# keyboard_matrix_full.net
KiCad netlist of a schematic drawn in Altium Designer
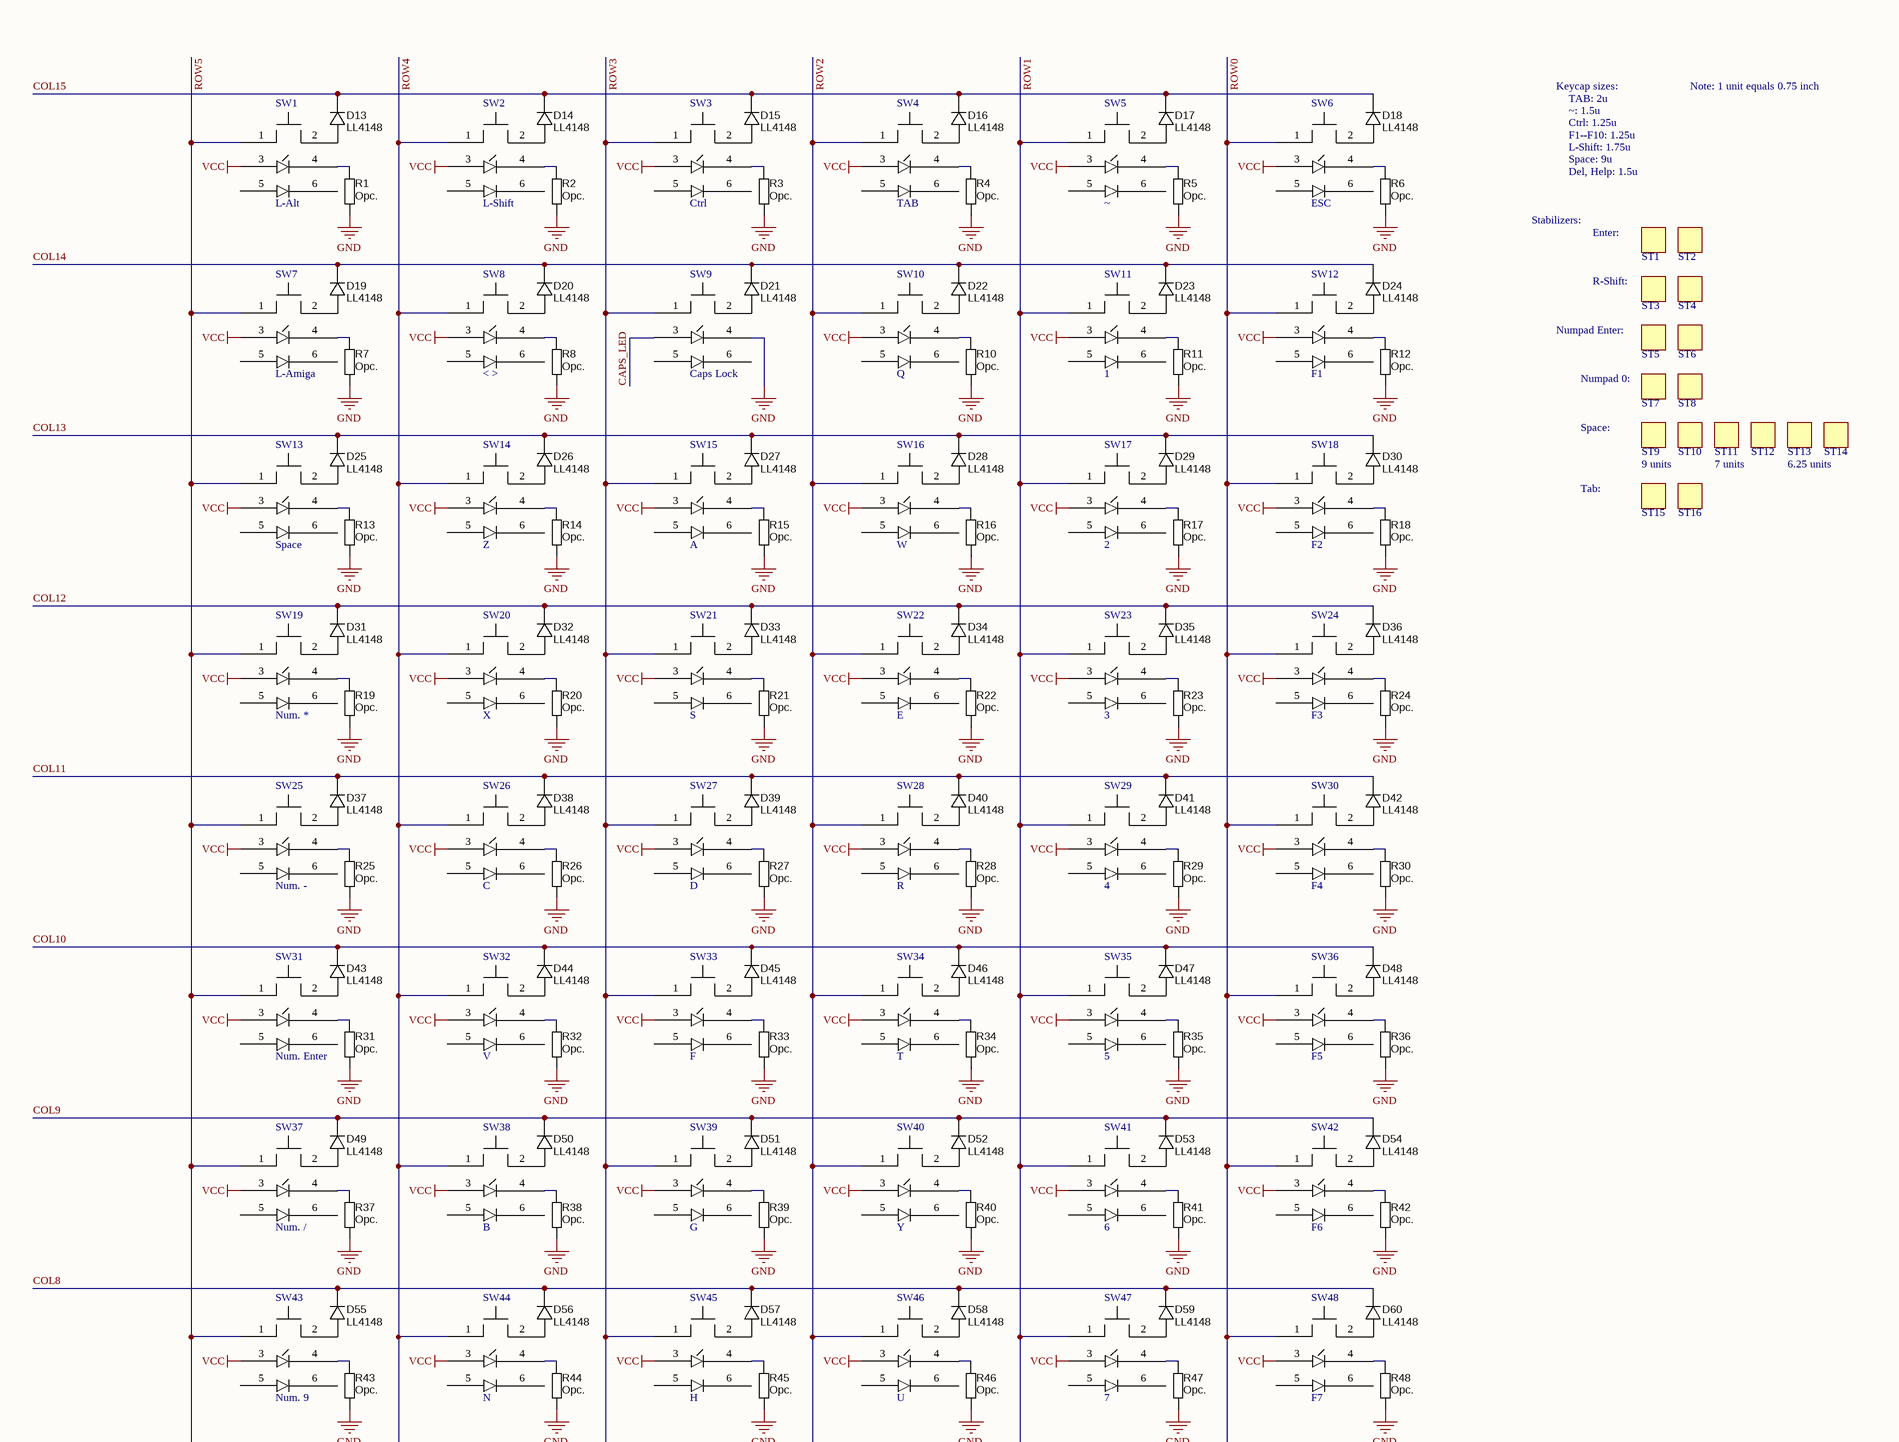
[diagram p0: keyboard_matrix_full.SchDoc, top]
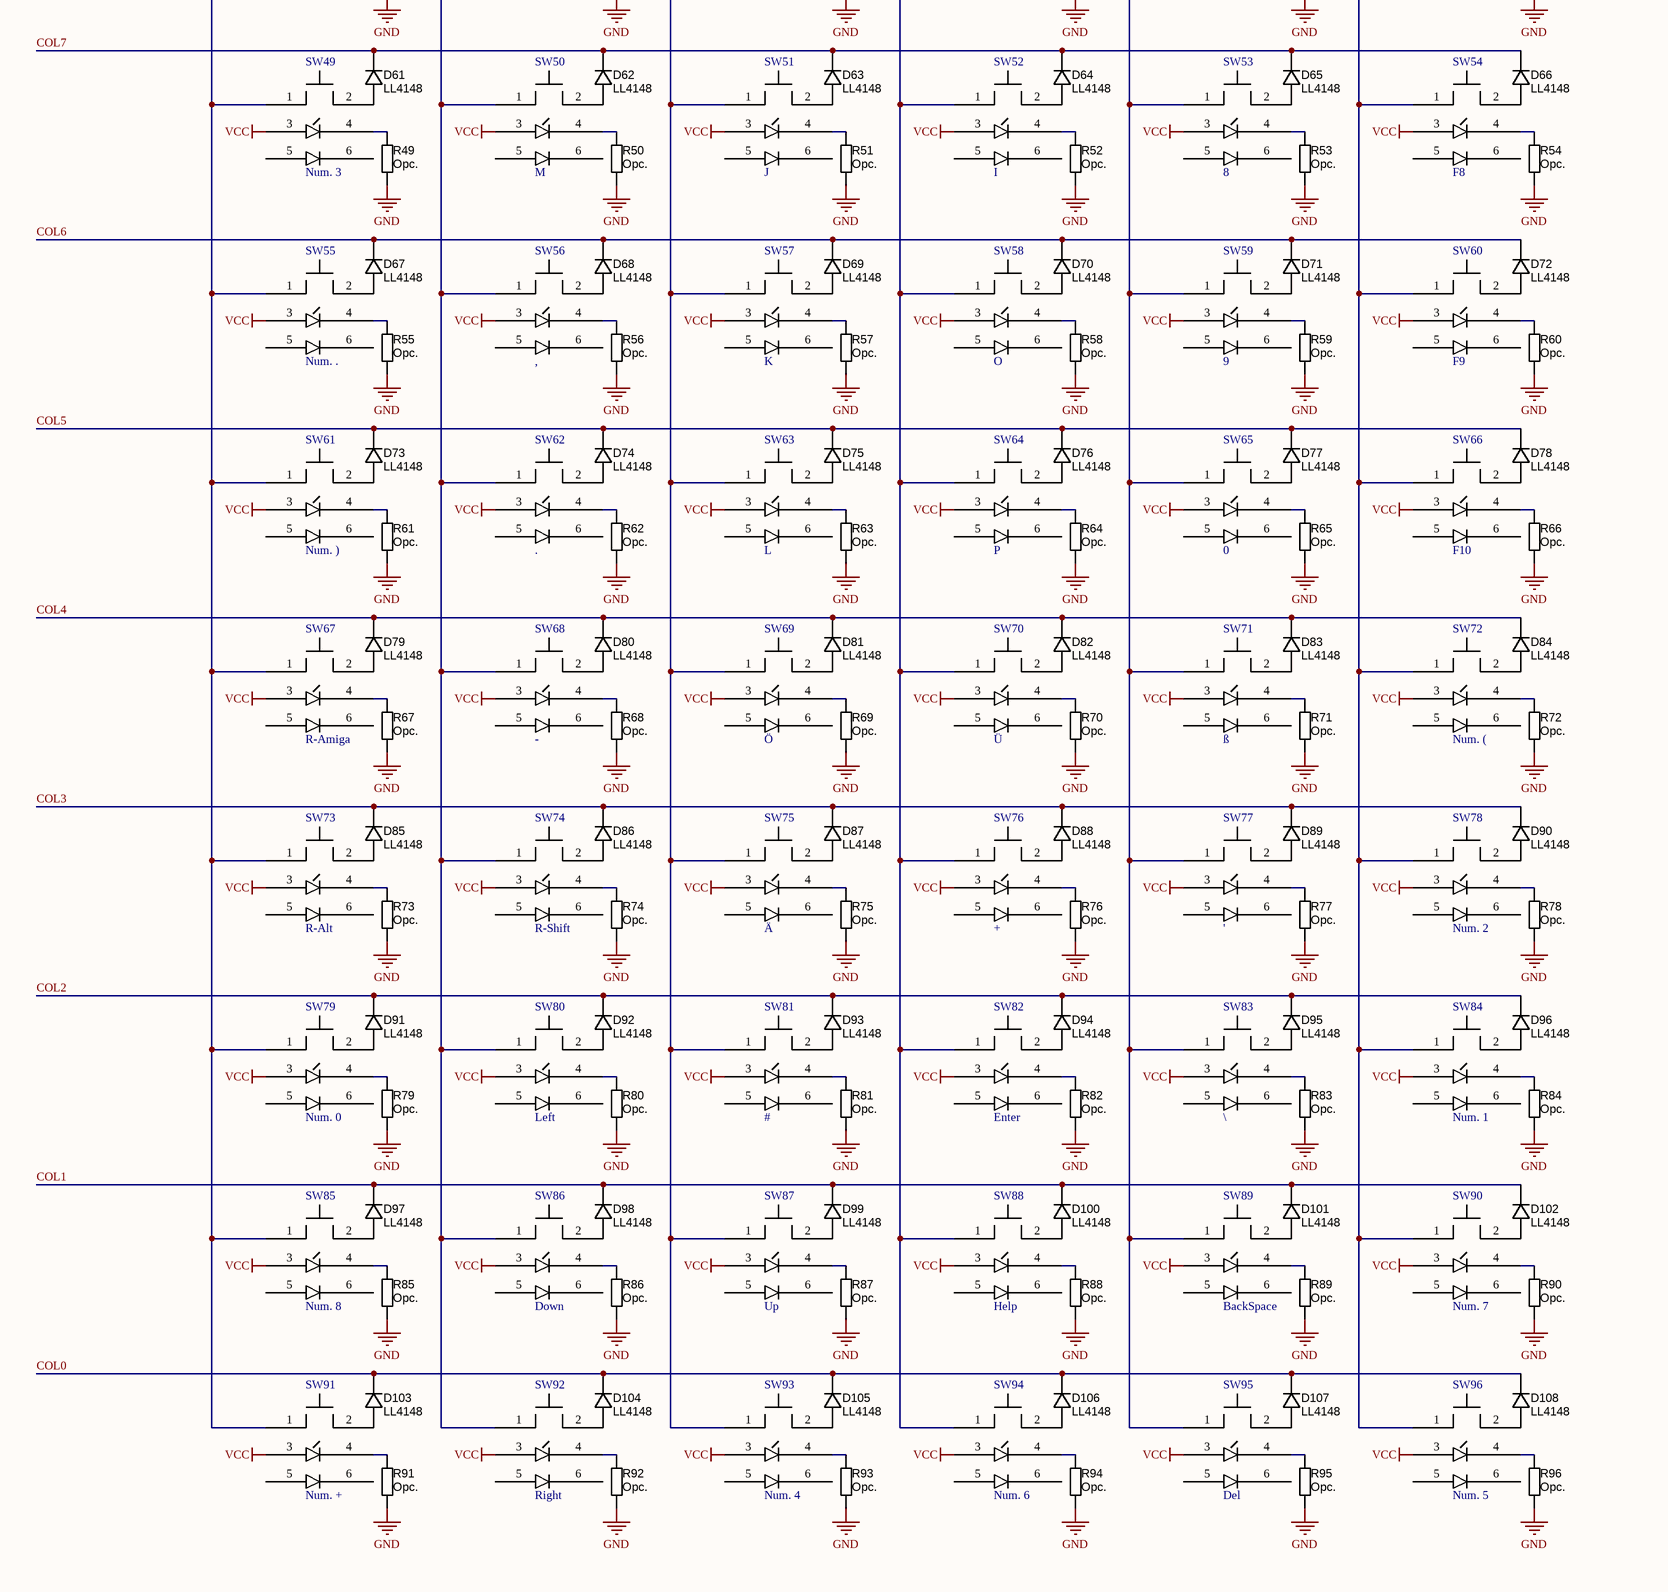
[diagram p1: keyboard_matrix_full.SchDoc, bottom]

(export (version "E")
  (design (tool "Eeschema 10.0.6"))
  (components
    (comp (ref "D13")
      (value "Mini MELF")
      (footprint "SOD80, LL-34")
      (description "Diode SMD 100V 150mA 500mW SOD80")
      (fields (field (name "MANUFACTURER PART NUMBER 1") "LL4148"))
      (libsource (lib "PBL - Diodes") (part "DIODE_100V_500mW_MELF"))
    )
    (comp (ref "D14")
      (value "Mini MELF")
      (footprint "SOD80, LL-34")
      (description "Diode SMD 100V 150mA 500mW SOD80")
      (fields (field (name "MANUFACTURER PART NUMBER 1") "LL4148"))
      (libsource (lib "PBL - Diodes") (part "DIODE_100V_500mW_MELF"))
    )
    (comp (ref "D15")
      (value "Mini MELF")
      (footprint "SOD80, LL-34")
      (description "Diode SMD 100V 150mA 500mW SOD80")
      (fields (field (name "MANUFACTURER PART NUMBER 1") "LL4148"))
      (libsource (lib "PBL - Diodes") (part "DIODE_100V_500mW_MELF"))
    )
    (comp (ref "D16")
      (value "Mini MELF")
      (footprint "SOD80, LL-34")
      (description "Diode SMD 100V 150mA 500mW SOD80")
      (fields (field (name "MANUFACTURER PART NUMBER 1") "LL4148"))
      (libsource (lib "PBL - Diodes") (part "DIODE_100V_500mW_MELF"))
    )
    (comp (ref "D17")
      (value "Mini MELF")
      (footprint "SOD80, LL-34")
      (description "Diode SMD 100V 150mA 500mW SOD80")
      (fields (field (name "MANUFACTURER PART NUMBER 1") "LL4148"))
      (libsource (lib "PBL - Diodes") (part "DIODE_100V_500mW_MELF"))
    )
    (comp (ref "D18")
      (value "Mini MELF")
      (footprint "SOD80, LL-34")
      (description "Diode SMD 100V 150mA 500mW SOD80")
      (fields (field (name "MANUFACTURER PART NUMBER 1") "LL4148"))
      (libsource (lib "PBL - Diodes") (part "DIODE_100V_500mW_MELF"))
    )
    (comp (ref "D19")
      (value "Mini MELF")
      (footprint "SOD80, LL-34")
      (description "Diode SMD 100V 150mA 500mW SOD80")
      (fields (field (name "MANUFACTURER PART NUMBER 1") "LL4148"))
      (libsource (lib "PBL - Diodes") (part "DIODE_100V_500mW_MELF"))
    )
    (comp (ref "D20")
      (value "Mini MELF")
      (footprint "SOD80, LL-34")
      (description "Diode SMD 100V 150mA 500mW SOD80")
      (fields (field (name "MANUFACTURER PART NUMBER 1") "LL4148"))
      (libsource (lib "PBL - Diodes") (part "DIODE_100V_500mW_MELF"))
    )
    (comp (ref "D21")
      (value "Mini MELF")
      (footprint "SOD80, LL-34")
      (description "Diode SMD 100V 150mA 500mW SOD80")
      (fields (field (name "MANUFACTURER PART NUMBER 1") "LL4148"))
      (libsource (lib "PBL - Diodes") (part "DIODE_100V_500mW_MELF"))
    )
    (comp (ref "D22")
      (value "Mini MELF")
      (footprint "SOD80, LL-34")
      (description "Diode SMD 100V 150mA 500mW SOD80")
      (fields (field (name "MANUFACTURER PART NUMBER 1") "LL4148"))
      (libsource (lib "PBL - Diodes") (part "DIODE_100V_500mW_MELF"))
    )
    (comp (ref "D23")
      (value "Mini MELF")
      (footprint "SOD80, LL-34")
      (description "Diode SMD 100V 150mA 500mW SOD80")
      (fields (field (name "MANUFACTURER PART NUMBER 1") "LL4148"))
      (libsource (lib "PBL - Diodes") (part "DIODE_100V_500mW_MELF"))
    )
    (comp (ref "D24")
      (value "Mini MELF")
      (footprint "SOD80, LL-34")
      (description "Diode SMD 100V 150mA 500mW SOD80")
      (fields (field (name "MANUFACTURER PART NUMBER 1") "LL4148"))
      (libsource (lib "PBL - Diodes") (part "DIODE_100V_500mW_MELF"))
    )
    (comp (ref "D25")
      (value "Mini MELF")
      (footprint "SOD80, LL-34")
      (description "Diode SMD 100V 150mA 500mW SOD80")
      (fields (field (name "MANUFACTURER PART NUMBER 1") "LL4148"))
      (libsource (lib "PBL - Diodes") (part "DIODE_100V_500mW_MELF"))
    )
    (comp (ref "D26")
      (value "Mini MELF")
      (footprint "SOD80, LL-34")
      (description "Diode SMD 100V 150mA 500mW SOD80")
      (fields (field (name "MANUFACTURER PART NUMBER 1") "LL4148"))
      (libsource (lib "PBL - Diodes") (part "DIODE_100V_500mW_MELF"))
    )
    (comp (ref "D27")
      (value "Mini MELF")
      (footprint "SOD80, LL-34")
      (description "Diode SMD 100V 150mA 500mW SOD80")
      (fields (field (name "MANUFACTURER PART NUMBER 1") "LL4148"))
      (libsource (lib "PBL - Diodes") (part "DIODE_100V_500mW_MELF"))
    )
    (comp (ref "D28")
      (value "Mini MELF")
      (footprint "SOD80, LL-34")
      (description "Diode SMD 100V 150mA 500mW SOD80")
      (fields (field (name "MANUFACTURER PART NUMBER 1") "LL4148"))
      (libsource (lib "PBL - Diodes") (part "DIODE_100V_500mW_MELF"))
    )
    (comp (ref "D29")
      (value "Mini MELF")
      (footprint "SOD80, LL-34")
      (description "Diode SMD 100V 150mA 500mW SOD80")
      (fields (field (name "MANUFACTURER PART NUMBER 1") "LL4148"))
      (libsource (lib "PBL - Diodes") (part "DIODE_100V_500mW_MELF"))
    )
    (comp (ref "D30")
      (value "Mini MELF")
      (footprint "SOD80, LL-34")
      (description "Diode SMD 100V 150mA 500mW SOD80")
      (fields (field (name "MANUFACTURER PART NUMBER 1") "LL4148"))
      (libsource (lib "PBL - Diodes") (part "DIODE_100V_500mW_MELF"))
    )
    (comp (ref "D31")
      (value "Mini MELF")
      (footprint "SOD80, LL-34")
      (description "Diode SMD 100V 150mA 500mW SOD80")
      (fields (field (name "MANUFACTURER PART NUMBER 1") "LL4148"))
      (libsource (lib "PBL - Diodes") (part "DIODE_100V_500mW_MELF"))
    )
    (comp (ref "D32")
      (value "Mini MELF")
      (footprint "SOD80, LL-34")
      (description "Diode SMD 100V 150mA 500mW SOD80")
      (fields (field (name "MANUFACTURER PART NUMBER 1") "LL4148"))
      (libsource (lib "PBL - Diodes") (part "DIODE_100V_500mW_MELF"))
    )
    (comp (ref "D33")
      (value "Mini MELF")
      (footprint "SOD80, LL-34")
      (description "Diode SMD 100V 150mA 500mW SOD80")
      (fields (field (name "MANUFACTURER PART NUMBER 1") "LL4148"))
      (libsource (lib "PBL - Diodes") (part "DIODE_100V_500mW_MELF"))
    )
    (comp (ref "D34")
      (value "Mini MELF")
      (footprint "SOD80, LL-34")
      (description "Diode SMD 100V 150mA 500mW SOD80")
      (fields (field (name "MANUFACTURER PART NUMBER 1") "LL4148"))
      (libsource (lib "PBL - Diodes") (part "DIODE_100V_500mW_MELF"))
    )
    (comp (ref "D35")
      (value "Mini MELF")
      (footprint "SOD80, LL-34")
      (description "Diode SMD 100V 150mA 500mW SOD80")
      (fields (field (name "MANUFACTURER PART NUMBER 1") "LL4148"))
      (libsource (lib "PBL - Diodes") (part "DIODE_100V_500mW_MELF"))
    )
    (comp (ref "D36")
      (value "Mini MELF")
      (footprint "SOD80, LL-34")
      (description "Diode SMD 100V 150mA 500mW SOD80")
      (fields (field (name "MANUFACTURER PART NUMBER 1") "LL4148"))
      (libsource (lib "PBL - Diodes") (part "DIODE_100V_500mW_MELF"))
    )
    (comp (ref "D37")
      (value "Mini MELF")
      (footprint "SOD80, LL-34")
      (description "Diode SMD 100V 150mA 500mW SOD80")
      (fields (field (name "MANUFACTURER PART NUMBER 1") "LL4148"))
      (libsource (lib "PBL - Diodes") (part "DIODE_100V_500mW_MELF"))
    )
    (comp (ref "D38")
      (value "Mini MELF")
      (footprint "SOD80, LL-34")
      (description "Diode SMD 100V 150mA 500mW SOD80")
      (fields (field (name "MANUFACTURER PART NUMBER 1") "LL4148"))
      (libsource (lib "PBL - Diodes") (part "DIODE_100V_500mW_MELF"))
    )
    (comp (ref "D39")
      (value "Mini MELF")
      (footprint "SOD80, LL-34")
      (description "Diode SMD 100V 150mA 500mW SOD80")
      (fields (field (name "MANUFACTURER PART NUMBER 1") "LL4148"))
      (libsource (lib "PBL - Diodes") (part "DIODE_100V_500mW_MELF"))
    )
    (comp (ref "D40")
      (value "Mini MELF")
      (footprint "SOD80, LL-34")
      (description "Diode SMD 100V 150mA 500mW SOD80")
      (fields (field (name "MANUFACTURER PART NUMBER 1") "LL4148"))
      (libsource (lib "PBL - Diodes") (part "DIODE_100V_500mW_MELF"))
    )
    (comp (ref "D41")
      (value "Mini MELF")
      (footprint "SOD80, LL-34")
      (description "Diode SMD 100V 150mA 500mW SOD80")
      (fields (field (name "MANUFACTURER PART NUMBER 1") "LL4148"))
      (libsource (lib "PBL - Diodes") (part "DIODE_100V_500mW_MELF"))
    )
    (comp (ref "D42")
      (value "Mini MELF")
      (footprint "SOD80, LL-34")
      (description "Diode SMD 100V 150mA 500mW SOD80")
      (fields (field (name "MANUFACTURER PART NUMBER 1") "LL4148"))
      (libsource (lib "PBL - Diodes") (part "DIODE_100V_500mW_MELF"))
    )
    (comp (ref "D43")
      (value "Mini MELF")
      (footprint "SOD80, LL-34")
      (description "Diode SMD 100V 150mA 500mW SOD80")
      (fields (field (name "MANUFACTURER PART NUMBER 1") "LL4148"))
      (libsource (lib "PBL - Diodes") (part "DIODE_100V_500mW_MELF"))
    )
    (comp (ref "D44")
      (value "Mini MELF")
      (footprint "SOD80, LL-34")
      (description "Diode SMD 100V 150mA 500mW SOD80")
      (fields (field (name "MANUFACTURER PART NUMBER 1") "LL4148"))
      (libsource (lib "PBL - Diodes") (part "DIODE_100V_500mW_MELF"))
    )
    (comp (ref "D45")
      (value "Mini MELF")
      (footprint "SOD80, LL-34")
      (description "Diode SMD 100V 150mA 500mW SOD80")
      (fields (field (name "MANUFACTURER PART NUMBER 1") "LL4148"))
      (libsource (lib "PBL - Diodes") (part "DIODE_100V_500mW_MELF"))
    )
    (comp (ref "D46")
      (value "Mini MELF")
      (footprint "SOD80, LL-34")
      (description "Diode SMD 100V 150mA 500mW SOD80")
      (fields (field (name "MANUFACTURER PART NUMBER 1") "LL4148"))
      (libsource (lib "PBL - Diodes") (part "DIODE_100V_500mW_MELF"))
    )
    (comp (ref "D47")
      (value "Mini MELF")
      (footprint "SOD80, LL-34")
      (description "Diode SMD 100V 150mA 500mW SOD80")
      (fields (field (name "MANUFACTURER PART NUMBER 1") "LL4148"))
      (libsource (lib "PBL - Diodes") (part "DIODE_100V_500mW_MELF"))
    )
    (comp (ref "D48")
      (value "Mini MELF")
      (footprint "SOD80, LL-34")
      (description "Diode SMD 100V 150mA 500mW SOD80")
      (fields (field (name "MANUFACTURER PART NUMBER 1") "LL4148"))
      (libsource (lib "PBL - Diodes") (part "DIODE_100V_500mW_MELF"))
    )
    (comp (ref "D49")
      (value "Mini MELF")
      (footprint "SOD80, LL-34")
      (description "Diode SMD 100V 150mA 500mW SOD80")
      (fields (field (name "MANUFACTURER PART NUMBER 1") "LL4148"))
      (libsource (lib "PBL - Diodes") (part "DIODE_100V_500mW_MELF"))
    )
    (comp (ref "D50")
      (value "Mini MELF")
      (footprint "SOD80, LL-34")
      (description "Diode SMD 100V 150mA 500mW SOD80")
      (fields (field (name "MANUFACTURER PART NUMBER 1") "LL4148"))
      (libsource (lib "PBL - Diodes") (part "DIODE_100V_500mW_MELF"))
    )
    (comp (ref "D51")
      (value "Mini MELF")
      (footprint "SOD80, LL-34")
      (description "Diode SMD 100V 150mA 500mW SOD80")
      (fields (field (name "MANUFACTURER PART NUMBER 1") "LL4148"))
      (libsource (lib "PBL - Diodes") (part "DIODE_100V_500mW_MELF"))
    )
    (comp (ref "D52")
      (value "Mini MELF")
      (footprint "SOD80, LL-34")
      (description "Diode SMD 100V 150mA 500mW SOD80")
      (fields (field (name "MANUFACTURER PART NUMBER 1") "LL4148"))
      (libsource (lib "PBL - Diodes") (part "DIODE_100V_500mW_MELF"))
    )
    (comp (ref "D53")
      (value "Mini MELF")
      (footprint "SOD80, LL-34")
      (description "Diode SMD 100V 150mA 500mW SOD80")
      (fields (field (name "MANUFACTURER PART NUMBER 1") "LL4148"))
      (libsource (lib "PBL - Diodes") (part "DIODE_100V_500mW_MELF"))
    )
    (comp (ref "D54")
      (value "Mini MELF")
      (footprint "SOD80, LL-34")
      (description "Diode SMD 100V 150mA 500mW SOD80")
      (fields (field (name "MANUFACTURER PART NUMBER 1") "LL4148"))
      (libsource (lib "PBL - Diodes") (part "DIODE_100V_500mW_MELF"))
    )
    (comp (ref "D55")
      (value "Mini MELF")
      (footprint "SOD80, LL-34")
      (description "Diode SMD 100V 150mA 500mW SOD80")
      (fields (field (name "MANUFACTURER PART NUMBER 1") "LL4148"))
      (libsource (lib "PBL - Diodes") (part "DIODE_100V_500mW_MELF"))
    )
    (comp (ref "D56")
      (value "Mini MELF")
      (footprint "SOD80, LL-34")
      (description "Diode SMD 100V 150mA 500mW SOD80")
      (fields (field (name "MANUFACTURER PART NUMBER 1") "LL4148"))
      (libsource (lib "PBL - Diodes") (part "DIODE_100V_500mW_MELF"))
    )
    (comp (ref "D57")
      (value "Mini MELF")
      (footprint "SOD80, LL-34")
      (description "Diode SMD 100V 150mA 500mW SOD80")
      (fields (field (name "MANUFACTURER PART NUMBER 1") "LL4148"))
      (libsource (lib "PBL - Diodes") (part "DIODE_100V_500mW_MELF"))
    )
    (comp (ref "D58")
      (value "Mini MELF")
      (footprint "SOD80, LL-34")
      (description "Diode SMD 100V 150mA 500mW SOD80")
      (fields (field (name "MANUFACTURER PART NUMBER 1") "LL4148"))
      (libsource (lib "PBL - Diodes") (part "DIODE_100V_500mW_MELF"))
    )
    (comp (ref "D59")
      (value "Mini MELF")
      (footprint "SOD80, LL-34")
      (description "Diode SMD 100V 150mA 500mW SOD80")
      (fields (field (name "MANUFACTURER PART NUMBER 1") "LL4148"))
      (libsource (lib "PBL - Diodes") (part "DIODE_100V_500mW_MELF"))
    )
    (comp (ref "D60")
      (value "Mini MELF")
      (footprint "SOD80, LL-34")
      (description "Diode SMD 100V 150mA 500mW SOD80")
      (fields (field (name "MANUFACTURER PART NUMBER 1") "LL4148"))
      (libsource (lib "PBL - Diodes") (part "DIODE_100V_500mW_MELF"))
    )
    (comp (ref "D61")
      (value "Mini MELF")
      (footprint "SOD80, LL-34")
      (description "Diode SMD 100V 150mA 500mW SOD80")
      (fields (field (name "MANUFACTURER PART NUMBER 1") "LL4148"))
      (libsource (lib "PBL - Diodes") (part "DIODE_100V_500mW_MELF"))
    )
    (comp (ref "D62")
      (value "Mini MELF")
      (footprint "SOD80, LL-34")
      (description "Diode SMD 100V 150mA 500mW SOD80")
      (fields (field (name "MANUFACTURER PART NUMBER 1") "LL4148"))
      (libsource (lib "PBL - Diodes") (part "DIODE_100V_500mW_MELF"))
    )
    (comp (ref "D63")
      (value "Mini MELF")
      (footprint "SOD80, LL-34")
      (description "Diode SMD 100V 150mA 500mW SOD80")
      (fields (field (name "MANUFACTURER PART NUMBER 1") "LL4148"))
      (libsource (lib "PBL - Diodes") (part "DIODE_100V_500mW_MELF"))
    )
    (comp (ref "D64")
      (value "Mini MELF")
      (footprint "SOD80, LL-34")
      (description "Diode SMD 100V 150mA 500mW SOD80")
      (fields (field (name "MANUFACTURER PART NUMBER 1") "LL4148"))
      (libsource (lib "PBL - Diodes") (part "DIODE_100V_500mW_MELF"))
    )
    (comp (ref "D65")
      (value "Mini MELF")
      (footprint "SOD80, LL-34")
      (description "Diode SMD 100V 150mA 500mW SOD80")
      (fields (field (name "MANUFACTURER PART NUMBER 1") "LL4148"))
      (libsource (lib "PBL - Diodes") (part "DIODE_100V_500mW_MELF"))
    )
    (comp (ref "D66")
      (value "Mini MELF")
      (footprint "SOD80, LL-34")
      (description "Diode SMD 100V 150mA 500mW SOD80")
      (fields (field (name "MANUFACTURER PART NUMBER 1") "LL4148"))
      (libsource (lib "PBL - Diodes") (part "DIODE_100V_500mW_MELF"))
    )
    (comp (ref "D67")
      (value "Mini MELF")
      (footprint "SOD80, LL-34")
      (description "Diode SMD 100V 150mA 500mW SOD80")
      (fields (field (name "MANUFACTURER PART NUMBER 1") "LL4148"))
      (libsource (lib "PBL - Diodes") (part "DIODE_100V_500mW_MELF"))
    )
    (comp (ref "D68")
      (value "Mini MELF")
      (footprint "SOD80, LL-34")
      (description "Diode SMD 100V 150mA 500mW SOD80")
      (fields (field (name "MANUFACTURER PART NUMBER 1") "LL4148"))
      (libsource (lib "PBL - Diodes") (part "DIODE_100V_500mW_MELF"))
    )
    (comp (ref "D69")
      (value "Mini MELF")
      (footprint "SOD80, LL-34")
      (description "Diode SMD 100V 150mA 500mW SOD80")
      (fields (field (name "MANUFACTURER PART NUMBER 1") "LL4148"))
      (libsource (lib "PBL - Diodes") (part "DIODE_100V_500mW_MELF"))
    )
    (comp (ref "D70")
      (value "Mini MELF")
      (footprint "SOD80, LL-34")
      (description "Diode SMD 100V 150mA 500mW SOD80")
      (fields (field (name "MANUFACTURER PART NUMBER 1") "LL4148"))
      (libsource (lib "PBL - Diodes") (part "DIODE_100V_500mW_MELF"))
    )
    (comp (ref "D71")
      (value "Mini MELF")
      (footprint "SOD80, LL-34")
      (description "Diode SMD 100V 150mA 500mW SOD80")
      (fields (field (name "MANUFACTURER PART NUMBER 1") "LL4148"))
      (libsource (lib "PBL - Diodes") (part "DIODE_100V_500mW_MELF"))
    )
    (comp (ref "D72")
      (value "Mini MELF")
      (footprint "SOD80, LL-34")
      (description "Diode SMD 100V 150mA 500mW SOD80")
      (fields (field (name "MANUFACTURER PART NUMBER 1") "LL4148"))
      (libsource (lib "PBL - Diodes") (part "DIODE_100V_500mW_MELF"))
    )
    (comp (ref "D73")
      (value "Mini MELF")
      (footprint "SOD80, LL-34")
      (description "Diode SMD 100V 150mA 500mW SOD80")
      (fields (field (name "MANUFACTURER PART NUMBER 1") "LL4148"))
      (libsource (lib "PBL - Diodes") (part "DIODE_100V_500mW_MELF"))
    )
    (comp (ref "D74")
      (value "Mini MELF")
      (footprint "SOD80, LL-34")
      (description "Diode SMD 100V 150mA 500mW SOD80")
      (fields (field (name "MANUFACTURER PART NUMBER 1") "LL4148"))
      (libsource (lib "PBL - Diodes") (part "DIODE_100V_500mW_MELF"))
    )
    (comp (ref "D75")
      (value "Mini MELF")
      (footprint "SOD80, LL-34")
      (description "Diode SMD 100V 150mA 500mW SOD80")
      (fields (field (name "MANUFACTURER PART NUMBER 1") "LL4148"))
      (libsource (lib "PBL - Diodes") (part "DIODE_100V_500mW_MELF"))
    )
    (comp (ref "D76")
      (value "Mini MELF")
      (footprint "SOD80, LL-34")
      (description "Diode SMD 100V 150mA 500mW SOD80")
      (fields (field (name "MANUFACTURER PART NUMBER 1") "LL4148"))
      (libsource (lib "PBL - Diodes") (part "DIODE_100V_500mW_MELF"))
    )
    (comp (ref "D77")
      (value "Mini MELF")
      (footprint "SOD80, LL-34")
      (description "Diode SMD 100V 150mA 500mW SOD80")
      (fields (field (name "MANUFACTURER PART NUMBER 1") "LL4148"))
      (libsource (lib "PBL - Diodes") (part "DIODE_100V_500mW_MELF"))
    )
    (comp (ref "D78")
      (value "Mini MELF")
      (footprint "SOD80, LL-34")
      (description "Diode SMD 100V 150mA 500mW SOD80")
      (fields (field (name "MANUFACTURER PART NUMBER 1") "LL4148"))
      (libsource (lib "PBL - Diodes") (part "DIODE_100V_500mW_MELF"))
    )
    (comp (ref "D79")
      (value "Mini MELF")
      (footprint "SOD80, LL-34")
      (description "Diode SMD 100V 150mA 500mW SOD80")
      (fields (field (name "MANUFACTURER PART NUMBER 1") "LL4148"))
      (libsource (lib "PBL - Diodes") (part "DIODE_100V_500mW_MELF"))
    )
    (comp (ref "D80")
      (value "Mini MELF")
      (footprint "SOD80, LL-34")
      (description "Diode SMD 100V 150mA 500mW SOD80")
      (fields (field (name "MANUFACTURER PART NUMBER 1") "LL4148"))
      (libsource (lib "PBL - Diodes") (part "DIODE_100V_500mW_MELF"))
    )
    (comp (ref "D81")
      (value "Mini MELF")
      (footprint "SOD80, LL-34")
      (description "Diode SMD 100V 150mA 500mW SOD80")
      (fields (field (name "MANUFACTURER PART NUMBER 1") "LL4148"))
      (libsource (lib "PBL - Diodes") (part "DIODE_100V_500mW_MELF"))
    )
    (comp (ref "D82")
      (value "Mini MELF")
      (footprint "SOD80, LL-34")
      (description "Diode SMD 100V 150mA 500mW SOD80")
      (fields (field (name "MANUFACTURER PART NUMBER 1") "LL4148"))
      (libsource (lib "PBL - Diodes") (part "DIODE_100V_500mW_MELF"))
    )
    (comp (ref "D83")
      (value "Mini MELF")
      (footprint "SOD80, LL-34")
      (description "Diode SMD 100V 150mA 500mW SOD80")
      (fields (field (name "MANUFACTURER PART NUMBER 1") "LL4148"))
      (libsource (lib "PBL - Diodes") (part "DIODE_100V_500mW_MELF"))
    )
    (comp (ref "D84")
      (value "Mini MELF")
      (footprint "SOD80, LL-34")
      (description "Diode SMD 100V 150mA 500mW SOD80")
      (fields (field (name "MANUFACTURER PART NUMBER 1") "LL4148"))
      (libsource (lib "PBL - Diodes") (part "DIODE_100V_500mW_MELF"))
    )
    (comp (ref "D85")
      (value "Mini MELF")
      (footprint "SOD80, LL-34")
      (description "Diode SMD 100V 150mA 500mW SOD80")
      (fields (field (name "MANUFACTURER PART NUMBER 1") "LL4148"))
      (libsource (lib "PBL - Diodes") (part "DIODE_100V_500mW_MELF"))
    )
    (comp (ref "D86")
      (value "Mini MELF")
      (footprint "SOD80, LL-34")
      (description "Diode SMD 100V 150mA 500mW SOD80")
      (fields (field (name "MANUFACTURER PART NUMBER 1") "LL4148"))
      (libsource (lib "PBL - Diodes") (part "DIODE_100V_500mW_MELF"))
    )
    (comp (ref "D87")
      (value "Mini MELF")
      (footprint "SOD80, LL-34")
      (description "Diode SMD 100V 150mA 500mW SOD80")
      (fields (field (name "MANUFACTURER PART NUMBER 1") "LL4148"))
      (libsource (lib "PBL - Diodes") (part "DIODE_100V_500mW_MELF"))
    )
    (comp (ref "D88")
      (value "Mini MELF")
      (footprint "SOD80, LL-34")
      (description "Diode SMD 100V 150mA 500mW SOD80")
      (fields (field (name "MANUFACTURER PART NUMBER 1") "LL4148"))
      (libsource (lib "PBL - Diodes") (part "DIODE_100V_500mW_MELF"))
    )
    (comp (ref "D89")
      (value "Mini MELF")
      (footprint "SOD80, LL-34")
      (description "Diode SMD 100V 150mA 500mW SOD80")
      (fields (field (name "MANUFACTURER PART NUMBER 1") "LL4148"))
      (libsource (lib "PBL - Diodes") (part "DIODE_100V_500mW_MELF"))
    )
    (comp (ref "D90")
      (value "Mini MELF")
      (footprint "SOD80, LL-34")
      (description "Diode SMD 100V 150mA 500mW SOD80")
      (fields (field (name "MANUFACTURER PART NUMBER 1") "LL4148"))
      (libsource (lib "PBL - Diodes") (part "DIODE_100V_500mW_MELF"))
    )
    (comp (ref "D91")
      (value "Mini MELF")
      (footprint "SOD80, LL-34")
      (description "Diode SMD 100V 150mA 500mW SOD80")
      (fields (field (name "MANUFACTURER PART NUMBER 1") "LL4148"))
      (libsource (lib "PBL - Diodes") (part "DIODE_100V_500mW_MELF"))
    )
    (comp (ref "D92")
      (value "Mini MELF")
      (footprint "SOD80, LL-34")
      (description "Diode SMD 100V 150mA 500mW SOD80")
      (fields (field (name "MANUFACTURER PART NUMBER 1") "LL4148"))
      (libsource (lib "PBL - Diodes") (part "DIODE_100V_500mW_MELF"))
    )
    (comp (ref "D93")
      (value "Mini MELF")
      (footprint "SOD80, LL-34")
      (description "Diode SMD 100V 150mA 500mW SOD80")
      (fields (field (name "MANUFACTURER PART NUMBER 1") "LL4148"))
      (libsource (lib "PBL - Diodes") (part "DIODE_100V_500mW_MELF"))
    )
    (comp (ref "D94")
      (value "Mini MELF")
      (footprint "SOD80, LL-34")
      (description "Diode SMD 100V 150mA 500mW SOD80")
      (fields (field (name "MANUFACTURER PART NUMBER 1") "LL4148"))
      (libsource (lib "PBL - Diodes") (part "DIODE_100V_500mW_MELF"))
    )
    (comp (ref "D95")
      (value "Mini MELF")
      (footprint "SOD80, LL-34")
      (description "Diode SMD 100V 150mA 500mW SOD80")
      (fields (field (name "MANUFACTURER PART NUMBER 1") "LL4148"))
      (libsource (lib "PBL - Diodes") (part "DIODE_100V_500mW_MELF"))
    )
    (comp (ref "D96")
      (value "Mini MELF")
      (footprint "SOD80, LL-34")
      (description "Diode SMD 100V 150mA 500mW SOD80")
      (fields (field (name "MANUFACTURER PART NUMBER 1") "LL4148"))
      (libsource (lib "PBL - Diodes") (part "DIODE_100V_500mW_MELF"))
    )
    (comp (ref "D97")
      (value "Mini MELF")
      (footprint "SOD80, LL-34")
      (description "Diode SMD 100V 150mA 500mW SOD80")
      (fields (field (name "MANUFACTURER PART NUMBER 1") "LL4148"))
      (libsource (lib "PBL - Diodes") (part "DIODE_100V_500mW_MELF"))
    )
    (comp (ref "D98")
      (value "Mini MELF")
      (footprint "SOD80, LL-34")
      (description "Diode SMD 100V 150mA 500mW SOD80")
      (fields (field (name "MANUFACTURER PART NUMBER 1") "LL4148"))
      (libsource (lib "PBL - Diodes") (part "DIODE_100V_500mW_MELF"))
    )
    (comp (ref "D99")
      (value "Mini MELF")
      (footprint "SOD80, LL-34")
      (description "Diode SMD 100V 150mA 500mW SOD80")
      (fields (field (name "MANUFACTURER PART NUMBER 1") "LL4148"))
      (libsource (lib "PBL - Diodes") (part "DIODE_100V_500mW_MELF"))
    )
    (comp (ref "D100")
      (value "Mini MELF")
      (footprint "SOD80, LL-34")
      (description "Diode SMD 100V 150mA 500mW SOD80")
      (fields (field (name "MANUFACTURER PART NUMBER 1") "LL4148"))
      (libsource (lib "PBL - Diodes") (part "DIODE_100V_500mW_MELF"))
    )
    (comp (ref "D101")
      (value "Mini MELF")
      (footprint "SOD80, LL-34")
      (description "Diode SMD 100V 150mA 500mW SOD80")
      (fields (field (name "MANUFACTURER PART NUMBER 1") "LL4148"))
      (libsource (lib "PBL - Diodes") (part "DIODE_100V_500mW_MELF"))
    )
    (comp (ref "D102")
      (value "Mini MELF")
      (footprint "SOD80, LL-34")
      (description "Diode SMD 100V 150mA 500mW SOD80")
      (fields (field (name "MANUFACTURER PART NUMBER 1") "LL4148"))
      (libsource (lib "PBL - Diodes") (part "DIODE_100V_500mW_MELF"))
    )
    (comp (ref "D103")
      (value "Mini MELF")
      (footprint "SOD80, LL-34")
      (description "Diode SMD 100V 150mA 500mW SOD80")
      (fields (field (name "MANUFACTURER PART NUMBER 1") "LL4148"))
      (libsource (lib "PBL - Diodes") (part "DIODE_100V_500mW_MELF"))
    )
    (comp (ref "D104")
      (value "Mini MELF")
      (footprint "SOD80, LL-34")
      (description "Diode SMD 100V 150mA 500mW SOD80")
      (fields (field (name "MANUFACTURER PART NUMBER 1") "LL4148"))
      (libsource (lib "PBL - Diodes") (part "DIODE_100V_500mW_MELF"))
    )
    (comp (ref "D105")
      (value "Mini MELF")
      (footprint "SOD80, LL-34")
      (description "Diode SMD 100V 150mA 500mW SOD80")
      (fields (field (name "MANUFACTURER PART NUMBER 1") "LL4148"))
      (libsource (lib "PBL - Diodes") (part "DIODE_100V_500mW_MELF"))
    )
    (comp (ref "D106")
      (value "Mini MELF")
      (footprint "SOD80, LL-34")
      (description "Diode SMD 100V 150mA 500mW SOD80")
      (fields (field (name "MANUFACTURER PART NUMBER 1") "LL4148"))
      (libsource (lib "PBL - Diodes") (part "DIODE_100V_500mW_MELF"))
    )
    (comp (ref "D107")
      (value "Mini MELF")
      (footprint "SOD80, LL-34")
      (description "Diode SMD 100V 150mA 500mW SOD80")
      (fields (field (name "MANUFACTURER PART NUMBER 1") "LL4148"))
      (libsource (lib "PBL - Diodes") (part "DIODE_100V_500mW_MELF"))
    )
    (comp (ref "D108")
      (value "Mini MELF")
      (footprint "SOD80, LL-34")
      (description "Diode SMD 100V 150mA 500mW SOD80")
      (fields (field (name "MANUFACTURER PART NUMBER 1") "LL4148"))
      (libsource (lib "PBL - Diodes") (part "DIODE_100V_500mW_MELF"))
    )
    (comp (ref "R1")
      (value "Opc.")
      (footprint "RESC2012N_ZERO")
      (description "Resistor SMD chip 0.0 Ohm 0.125W 0805")
      (fields (field (name "Comment") "0805"))
      (libsource (lib "ZX_Spectrum_library") (part "RES_0R_0805"))
    )
    (comp (ref "R2")
      (value "Opc.")
      (footprint "RESC2012N_ZERO")
      (description "Resistor SMD chip 0.0 Ohm 0.125W 0805")
      (fields (field (name "Comment") "0805"))
      (libsource (lib "ZX_Spectrum_library") (part "RES_0R_0805"))
    )
    (comp (ref "R3")
      (value "Opc.")
      (footprint "RESC2012N_ZERO")
      (description "Resistor SMD chip 0.0 Ohm 0.125W 0805")
      (fields (field (name "Comment") "0805"))
      (libsource (lib "ZX_Spectrum_library") (part "RES_0R_0805"))
    )
    (comp (ref "R4")
      (value "Opc.")
      (footprint "RESC2012N_ZERO")
      (description "Resistor SMD chip 0.0 Ohm 0.125W 0805")
      (fields (field (name "Comment") "0805"))
      (libsource (lib "ZX_Spectrum_library") (part "RES_0R_0805"))
    )
    (comp (ref "R5")
      (value "Opc.")
      (footprint "RESC2012N_ZERO")
      (description "Resistor SMD chip 0.0 Ohm 0.125W 0805")
      (fields (field (name "Comment") "0805"))
      (libsource (lib "ZX_Spectrum_library") (part "RES_0R_0805"))
    )
    (comp (ref "R6")
      (value "Opc.")
      (footprint "RESC2012N_ZERO")
      (description "Resistor SMD chip 0.0 Ohm 0.125W 0805")
      (fields (field (name "Comment") "0805"))
      (libsource (lib "ZX_Spectrum_library") (part "RES_0R_0805"))
    )
    (comp (ref "R7")
      (value "Opc.")
      (footprint "RESC2012N_ZERO")
      (description "Resistor SMD chip 0.0 Ohm 0.125W 0805")
      (fields (field (name "Comment") "0805"))
      (libsource (lib "ZX_Spectrum_library") (part "RES_0R_0805"))
    )
    (comp (ref "R8")
      (value "Opc.")
      (footprint "RESC2012N_ZERO")
      (description "Resistor SMD chip 0.0 Ohm 0.125W 0805")
      (fields (field (name "Comment") "0805"))
      (libsource (lib "ZX_Spectrum_library") (part "RES_0R_0805"))
    )
    (comp (ref "R10")
      (value "Opc.")
      (footprint "RESC2012N_ZERO")
      (description "Resistor SMD chip 0.0 Ohm 0.125W 0805")
      (fields (field (name "Comment") "0805"))
      (libsource (lib "ZX_Spectrum_library") (part "RES_0R_0805"))
    )
    (comp (ref "R11")
      (value "Opc.")
      (footprint "RESC2012N_ZERO")
      (description "Resistor SMD chip 0.0 Ohm 0.125W 0805")
      (fields (field (name "Comment") "0805"))
      (libsource (lib "ZX_Spectrum_library") (part "RES_0R_0805"))
    )
    (comp (ref "R12")
      (value "Opc.")
      (footprint "RESC2012N_ZERO")
      (description "Resistor SMD chip 0.0 Ohm 0.125W 0805")
      (fields (field (name "Comment") "0805"))
      (libsource (lib "ZX_Spectrum_library") (part "RES_0R_0805"))
    )
    (comp (ref "R13")
      (value "Opc.")
      (footprint "RESC2012N_ZERO")
      (description "Resistor SMD chip 0.0 Ohm 0.125W 0805")
      (fields (field (name "Comment") "0805"))
      (libsource (lib "ZX_Spectrum_library") (part "RES_0R_0805"))
    )
    (comp (ref "R14")
      (value "Opc.")
      (footprint "RESC2012N_ZERO")
      (description "Resistor SMD chip 0.0 Ohm 0.125W 0805")
      (fields (field (name "Comment") "0805"))
      (libsource (lib "ZX_Spectrum_library") (part "RES_0R_0805"))
    )
    (comp (ref "R15")
      (value "Opc.")
      (footprint "RESC2012N_ZERO")
      (description "Resistor SMD chip 0.0 Ohm 0.125W 0805")
      (fields (field (name "Comment") "0805"))
      (libsource (lib "ZX_Spectrum_library") (part "RES_0R_0805"))
    )
    (comp (ref "R16")
      (value "Opc.")
      (footprint "RESC2012N_ZERO")
      (description "Resistor SMD chip 0.0 Ohm 0.125W 0805")
      (fields (field (name "Comment") "0805"))
      (libsource (lib "ZX_Spectrum_library") (part "RES_0R_0805"))
    )
    (comp (ref "R17")
      (value "Opc.")
      (footprint "RESC2012N_ZERO")
      (description "Resistor SMD chip 0.0 Ohm 0.125W 0805")
      (fields (field (name "Comment") "0805"))
      (libsource (lib "ZX_Spectrum_library") (part "RES_0R_0805"))
    )
    (comp (ref "R18")
      (value "Opc.")
      (footprint "RESC2012N_ZERO")
      (description "Resistor SMD chip 0.0 Ohm 0.125W 0805")
      (fields (field (name "Comment") "0805"))
      (libsource (lib "ZX_Spectrum_library") (part "RES_0R_0805"))
    )
    (comp (ref "R19")
      (value "Opc.")
      (footprint "RESC2012N_ZERO")
      (description "Resistor SMD chip 0.0 Ohm 0.125W 0805")
      (fields (field (name "Comment") "0805"))
      (libsource (lib "ZX_Spectrum_library") (part "RES_0R_0805"))
    )
    (comp (ref "R20")
      (value "Opc.")
      (footprint "RESC2012N_ZERO")
      (description "Resistor SMD chip 0.0 Ohm 0.125W 0805")
      (fields (field (name "Comment") "0805"))
      (libsource (lib "ZX_Spectrum_library") (part "RES_0R_0805"))
    )
    (comp (ref "R21")
      (value "Opc.")
      (footprint "RESC2012N_ZERO")
      (description "Resistor SMD chip 0.0 Ohm 0.125W 0805")
      (fields (field (name "Comment") "0805"))
      (libsource (lib "ZX_Spectrum_library") (part "RES_0R_0805"))
    )
    (comp (ref "R22")
      (value "Opc.")
      (footprint "RESC2012N_ZERO")
      (description "Resistor SMD chip 0.0 Ohm 0.125W 0805")
      (fields (field (name "Comment") "0805"))
      (libsource (lib "ZX_Spectrum_library") (part "RES_0R_0805"))
    )
    (comp (ref "R23")
      (value "Opc.")
      (footprint "RESC2012N_ZERO")
      (description "Resistor SMD chip 0.0 Ohm 0.125W 0805")
      (fields (field (name "Comment") "0805"))
      (libsource (lib "ZX_Spectrum_library") (part "RES_0R_0805"))
    )
    (comp (ref "R24")
      (value "Opc.")
      (footprint "RESC2012N_ZERO")
      (description "Resistor SMD chip 0.0 Ohm 0.125W 0805")
      (fields (field (name "Comment") "0805"))
      (libsource (lib "ZX_Spectrum_library") (part "RES_0R_0805"))
    )
    (comp (ref "R25")
      (value "Opc.")
      (footprint "RESC2012N_ZERO")
      (description "Resistor SMD chip 0.0 Ohm 0.125W 0805")
      (fields (field (name "Comment") "0805"))
      (libsource (lib "ZX_Spectrum_library") (part "RES_0R_0805"))
    )
    (comp (ref "R26")
      (value "Opc.")
      (footprint "RESC2012N_ZERO")
      (description "Resistor SMD chip 0.0 Ohm 0.125W 0805")
      (fields (field (name "Comment") "0805"))
      (libsource (lib "ZX_Spectrum_library") (part "RES_0R_0805"))
    )
    (comp (ref "R27")
      (value "Opc.")
      (footprint "RESC2012N_ZERO")
      (description "Resistor SMD chip 0.0 Ohm 0.125W 0805")
      (fields (field (name "Comment") "0805"))
      (libsource (lib "ZX_Spectrum_library") (part "RES_0R_0805"))
    )
    (comp (ref "R28")
      (value "Opc.")
      (footprint "RESC2012N_ZERO")
      (description "Resistor SMD chip 0.0 Ohm 0.125W 0805")
      (fields (field (name "Comment") "0805"))
      (libsource (lib "ZX_Spectrum_library") (part "RES_0R_0805"))
    )
    (comp (ref "R29")
      (value "Opc.")
      (footprint "RESC2012N_ZERO")
      (description "Resistor SMD chip 0.0 Ohm 0.125W 0805")
      (fields (field (name "Comment") "0805"))
      (libsource (lib "ZX_Spectrum_library") (part "RES_0R_0805"))
    )
    (comp (ref "R30")
      (value "Opc.")
      (footprint "RESC2012N_ZERO")
      (description "Resistor SMD chip 0.0 Ohm 0.125W 0805")
      (fields (field (name "Comment") "0805"))
      (libsource (lib "ZX_Spectrum_library") (part "RES_0R_0805"))
    )
    (comp (ref "R31")
      (value "Opc.")
      (footprint "RESC2012N_ZERO")
      (description "Resistor SMD chip 0.0 Ohm 0.125W 0805")
      (fields (field (name "Comment") "0805"))
      (libsource (lib "ZX_Spectrum_library") (part "RES_0R_0805"))
    )
    (comp (ref "R32")
      (value "Opc.")
      (footprint "RESC2012N_ZERO")
      (description "Resistor SMD chip 0.0 Ohm 0.125W 0805")
      (fields (field (name "Comment") "0805"))
      (libsource (lib "ZX_Spectrum_library") (part "RES_0R_0805"))
    )
    (comp (ref "R33")
      (value "Opc.")
      (footprint "RESC2012N_ZERO")
      (description "Resistor SMD chip 0.0 Ohm 0.125W 0805")
      (fields (field (name "Comment") "0805"))
      (libsource (lib "ZX_Spectrum_library") (part "RES_0R_0805"))
    )
    (comp (ref "R34")
      (value "Opc.")
      (footprint "RESC2012N_ZERO")
      (description "Resistor SMD chip 0.0 Ohm 0.125W 0805")
      (fields (field (name "Comment") "0805"))
      (libsource (lib "ZX_Spectrum_library") (part "RES_0R_0805"))
    )
    (comp (ref "R35")
      (value "Opc.")
      (footprint "RESC2012N_ZERO")
      (description "Resistor SMD chip 0.0 Ohm 0.125W 0805")
      (fields (field (name "Comment") "0805"))
      (libsource (lib "ZX_Spectrum_library") (part "RES_0R_0805"))
    )
    (comp (ref "R36")
      (value "Opc.")
      (footprint "RESC2012N_ZERO")
      (description "Resistor SMD chip 0.0 Ohm 0.125W 0805")
      (fields (field (name "Comment") "0805"))
      (libsource (lib "ZX_Spectrum_library") (part "RES_0R_0805"))
    )
    (comp (ref "R37")
      (value "Opc.")
      (footprint "RESC2012N_ZERO")
      (description "Resistor SMD chip 0.0 Ohm 0.125W 0805")
      (fields (field (name "Comment") "0805"))
      (libsource (lib "ZX_Spectrum_library") (part "RES_0R_0805"))
    )
    (comp (ref "R38")
      (value "Opc.")
      (footprint "RESC2012N_ZERO")
      (description "Resistor SMD chip 0.0 Ohm 0.125W 0805")
      (fields (field (name "Comment") "0805"))
      (libsource (lib "ZX_Spectrum_library") (part "RES_0R_0805"))
    )
    (comp (ref "R39")
      (value "Opc.")
      (footprint "RESC2012N_ZERO")
      (description "Resistor SMD chip 0.0 Ohm 0.125W 0805")
      (fields (field (name "Comment") "0805"))
      (libsource (lib "ZX_Spectrum_library") (part "RES_0R_0805"))
    )
    (comp (ref "R40")
      (value "Opc.")
      (footprint "RESC2012N_ZERO")
      (description "Resistor SMD chip 0.0 Ohm 0.125W 0805")
      (fields (field (name "Comment") "0805"))
      (libsource (lib "ZX_Spectrum_library") (part "RES_0R_0805"))
    )
    (comp (ref "R41")
      (value "Opc.")
      (footprint "RESC2012N_ZERO")
      (description "Resistor SMD chip 0.0 Ohm 0.125W 0805")
      (fields (field (name "Comment") "0805"))
      (libsource (lib "ZX_Spectrum_library") (part "RES_0R_0805"))
    )
    (comp (ref "R42")
      (value "Opc.")
      (footprint "RESC2012N_ZERO")
      (description "Resistor SMD chip 0.0 Ohm 0.125W 0805")
      (fields (field (name "Comment") "0805"))
      (libsource (lib "ZX_Spectrum_library") (part "RES_0R_0805"))
    )
    (comp (ref "R43")
      (value "Opc.")
      (footprint "RESC2012N_ZERO")
      (description "Resistor SMD chip 0.0 Ohm 0.125W 0805")
      (fields (field (name "Comment") "0805"))
      (libsource (lib "ZX_Spectrum_library") (part "RES_0R_0805"))
    )
    (comp (ref "R44")
      (value "Opc.")
      (footprint "RESC2012N_ZERO")
      (description "Resistor SMD chip 0.0 Ohm 0.125W 0805")
      (fields (field (name "Comment") "0805"))
      (libsource (lib "ZX_Spectrum_library") (part "RES_0R_0805"))
    )
    (comp (ref "R45")
      (value "Opc.")
      (footprint "RESC2012N_ZERO")
      (description "Resistor SMD chip 0.0 Ohm 0.125W 0805")
      (fields (field (name "Comment") "0805"))
      (libsource (lib "ZX_Spectrum_library") (part "RES_0R_0805"))
    )
    (comp (ref "R46")
      (value "Opc.")
      (footprint "RESC2012N_ZERO")
      (description "Resistor SMD chip 0.0 Ohm 0.125W 0805")
      (fields (field (name "Comment") "0805"))
      (libsource (lib "ZX_Spectrum_library") (part "RES_0R_0805"))
    )
    (comp (ref "R47")
      (value "Opc.")
      (footprint "RESC2012N_ZERO")
      (description "Resistor SMD chip 0.0 Ohm 0.125W 0805")
      (fields (field (name "Comment") "0805"))
      (libsource (lib "ZX_Spectrum_library") (part "RES_0R_0805"))
    )
    (comp (ref "R48")
      (value "Opc.")
      (footprint "RESC2012N_ZERO")
      (description "Resistor SMD chip 0.0 Ohm 0.125W 0805")
      (fields (field (name "Comment") "0805"))
      (libsource (lib "ZX_Spectrum_library") (part "RES_0R_0805"))
    )
    (comp (ref "R49")
      (value "Opc.")
      (footprint "RESC2012N_ZERO")
      (description "Resistor SMD chip 0.0 Ohm 0.125W 0805")
      (fields (field (name "Comment") "0805"))
      (libsource (lib "ZX_Spectrum_library") (part "RES_0R_0805"))
    )
    (comp (ref "R50")
      (value "Opc.")
      (footprint "RESC2012N_ZERO")
      (description "Resistor SMD chip 0.0 Ohm 0.125W 0805")
      (fields (field (name "Comment") "0805"))
      (libsource (lib "ZX_Spectrum_library") (part "RES_0R_0805"))
    )
    (comp (ref "R51")
      (value "Opc.")
      (footprint "RESC2012N_ZERO")
      (description "Resistor SMD chip 0.0 Ohm 0.125W 0805")
      (fields (field (name "Comment") "0805"))
      (libsource (lib "ZX_Spectrum_library") (part "RES_0R_0805"))
    )
    (comp (ref "R52")
      (value "Opc.")
      (footprint "RESC2012N_ZERO")
      (description "Resistor SMD chip 0.0 Ohm 0.125W 0805")
      (fields (field (name "Comment") "0805"))
      (libsource (lib "ZX_Spectrum_library") (part "RES_0R_0805"))
    )
    (comp (ref "R53")
      (value "Opc.")
      (footprint "RESC2012N_ZERO")
      (description "Resistor SMD chip 0.0 Ohm 0.125W 0805")
      (fields (field (name "Comment") "0805"))
      (libsource (lib "ZX_Spectrum_library") (part "RES_0R_0805"))
    )
    (comp (ref "R54")
      (value "Opc.")
      (footprint "RESC2012N_ZERO")
      (description "Resistor SMD chip 0.0 Ohm 0.125W 0805")
      (fields (field (name "Comment") "0805"))
      (libsource (lib "ZX_Spectrum_library") (part "RES_0R_0805"))
    )
    (comp (ref "R55")
      (value "Opc.")
      (footprint "RESC2012N_ZERO")
      (description "Resistor SMD chip 0.0 Ohm 0.125W 0805")
      (fields (field (name "Comment") "0805"))
      (libsource (lib "ZX_Spectrum_library") (part "RES_0R_0805"))
    )
    (comp (ref "R56")
      (value "Opc.")
      (footprint "RESC2012N_ZERO")
      (description "Resistor SMD chip 0.0 Ohm 0.125W 0805")
      (fields (field (name "Comment") "0805"))
      (libsource (lib "ZX_Spectrum_library") (part "RES_0R_0805"))
    )
    (comp (ref "R57")
      (value "Opc.")
      (footprint "RESC2012N_ZERO")
      (description "Resistor SMD chip 0.0 Ohm 0.125W 0805")
      (fields (field (name "Comment") "0805"))
      (libsource (lib "ZX_Spectrum_library") (part "RES_0R_0805"))
    )
    (comp (ref "R58")
      (value "Opc.")
      (footprint "RESC2012N_ZERO")
      (description "Resistor SMD chip 0.0 Ohm 0.125W 0805")
      (fields (field (name "Comment") "0805"))
      (libsource (lib "ZX_Spectrum_library") (part "RES_0R_0805"))
    )
    (comp (ref "R59")
      (value "Opc.")
      (footprint "RESC2012N_ZERO")
      (description "Resistor SMD chip 0.0 Ohm 0.125W 0805")
      (fields (field (name "Comment") "0805"))
      (libsource (lib "ZX_Spectrum_library") (part "RES_0R_0805"))
    )
    (comp (ref "R60")
      (value "Opc.")
      (footprint "RESC2012N_ZERO")
      (description "Resistor SMD chip 0.0 Ohm 0.125W 0805")
      (fields (field (name "Comment") "0805"))
      (libsource (lib "ZX_Spectrum_library") (part "RES_0R_0805"))
    )
    (comp (ref "R61")
      (value "Opc.")
      (footprint "RESC2012N_ZERO")
      (description "Resistor SMD chip 0.0 Ohm 0.125W 0805")
      (fields (field (name "Comment") "0805"))
      (libsource (lib "ZX_Spectrum_library") (part "RES_0R_0805"))
    )
    (comp (ref "R62")
      (value "Opc.")
      (footprint "RESC2012N_ZERO")
      (description "Resistor SMD chip 0.0 Ohm 0.125W 0805")
      (fields (field (name "Comment") "0805"))
      (libsource (lib "ZX_Spectrum_library") (part "RES_0R_0805"))
    )
    (comp (ref "R63")
      (value "Opc.")
      (footprint "RESC2012N_ZERO")
      (description "Resistor SMD chip 0.0 Ohm 0.125W 0805")
      (fields (field (name "Comment") "0805"))
      (libsource (lib "ZX_Spectrum_library") (part "RES_0R_0805"))
    )
    (comp (ref "R64")
      (value "Opc.")
      (footprint "RESC2012N_ZERO")
      (description "Resistor SMD chip 0.0 Ohm 0.125W 0805")
      (fields (field (name "Comment") "0805"))
      (libsource (lib "ZX_Spectrum_library") (part "RES_0R_0805"))
    )
    (comp (ref "R65")
      (value "Opc.")
      (footprint "RESC2012N_ZERO")
      (description "Resistor SMD chip 0.0 Ohm 0.125W 0805")
      (fields (field (name "Comment") "0805"))
      (libsource (lib "ZX_Spectrum_library") (part "RES_0R_0805"))
    )
    (comp (ref "R66")
      (value "Opc.")
      (footprint "RESC2012N_ZERO")
      (description "Resistor SMD chip 0.0 Ohm 0.125W 0805")
      (fields (field (name "Comment") "0805"))
      (libsource (lib "ZX_Spectrum_library") (part "RES_0R_0805"))
    )
    (comp (ref "R67")
      (value "Opc.")
      (footprint "RESC2012N_ZERO")
      (description "Resistor SMD chip 0.0 Ohm 0.125W 0805")
      (fields (field (name "Comment") "0805"))
      (libsource (lib "ZX_Spectrum_library") (part "RES_0R_0805"))
    )
    (comp (ref "R68")
      (value "Opc.")
      (footprint "RESC2012N_ZERO")
      (description "Resistor SMD chip 0.0 Ohm 0.125W 0805")
      (fields (field (name "Comment") "0805"))
      (libsource (lib "ZX_Spectrum_library") (part "RES_0R_0805"))
    )
    (comp (ref "R69")
      (value "Opc.")
      (footprint "RESC2012N_ZERO")
      (description "Resistor SMD chip 0.0 Ohm 0.125W 0805")
      (fields (field (name "Comment") "0805"))
      (libsource (lib "ZX_Spectrum_library") (part "RES_0R_0805"))
    )
    (comp (ref "R70")
      (value "Opc.")
      (footprint "RESC2012N_ZERO")
      (description "Resistor SMD chip 0.0 Ohm 0.125W 0805")
      (fields (field (name "Comment") "0805"))
      (libsource (lib "ZX_Spectrum_library") (part "RES_0R_0805"))
    )
    (comp (ref "R71")
      (value "Opc.")
      (footprint "RESC2012N_ZERO")
      (description "Resistor SMD chip 0.0 Ohm 0.125W 0805")
      (fields (field (name "Comment") "0805"))
      (libsource (lib "ZX_Spectrum_library") (part "RES_0R_0805"))
    )
    (comp (ref "R72")
      (value "Opc.")
      (footprint "RESC2012N_ZERO")
      (description "Resistor SMD chip 0.0 Ohm 0.125W 0805")
      (fields (field (name "Comment") "0805"))
      (libsource (lib "ZX_Spectrum_library") (part "RES_0R_0805"))
    )
    (comp (ref "R73")
      (value "Opc.")
      (footprint "RESC2012N_ZERO")
      (description "Resistor SMD chip 0.0 Ohm 0.125W 0805")
      (fields (field (name "Comment") "0805"))
      (libsource (lib "ZX_Spectrum_library") (part "RES_0R_0805"))
    )
    (comp (ref "R74")
      (value "Opc.")
      (footprint "RESC2012N_ZERO")
      (description "Resistor SMD chip 0.0 Ohm 0.125W 0805")
      (fields (field (name "Comment") "0805"))
      (libsource (lib "ZX_Spectrum_library") (part "RES_0R_0805"))
    )
    (comp (ref "R75")
      (value "Opc.")
      (footprint "RESC2012N_ZERO")
      (description "Resistor SMD chip 0.0 Ohm 0.125W 0805")
      (fields (field (name "Comment") "0805"))
      (libsource (lib "ZX_Spectrum_library") (part "RES_0R_0805"))
    )
    (comp (ref "R76")
      (value "Opc.")
      (footprint "RESC2012N_ZERO")
      (description "Resistor SMD chip 0.0 Ohm 0.125W 0805")
      (fields (field (name "Comment") "0805"))
      (libsource (lib "ZX_Spectrum_library") (part "RES_0R_0805"))
    )
    (comp (ref "R77")
      (value "Opc.")
      (footprint "RESC2012N_ZERO")
      (description "Resistor SMD chip 0.0 Ohm 0.125W 0805")
      (fields (field (name "Comment") "0805"))
      (libsource (lib "ZX_Spectrum_library") (part "RES_0R_0805"))
    )
    (comp (ref "R78")
      (value "Opc.")
      (footprint "RESC2012N_ZERO")
      (description "Resistor SMD chip 0.0 Ohm 0.125W 0805")
      (fields (field (name "Comment") "0805"))
      (libsource (lib "ZX_Spectrum_library") (part "RES_0R_0805"))
    )
    (comp (ref "R79")
      (value "Opc.")
      (footprint "RESC2012N_ZERO")
      (description "Resistor SMD chip 0.0 Ohm 0.125W 0805")
      (fields (field (name "Comment") "0805"))
      (libsource (lib "ZX_Spectrum_library") (part "RES_0R_0805"))
    )
    (comp (ref "R80")
      (value "Opc.")
      (footprint "RESC2012N_ZERO")
      (description "Resistor SMD chip 0.0 Ohm 0.125W 0805")
      (fields (field (name "Comment") "0805"))
      (libsource (lib "ZX_Spectrum_library") (part "RES_0R_0805"))
    )
    (comp (ref "R81")
      (value "Opc.")
      (footprint "RESC2012N_ZERO")
      (description "Resistor SMD chip 0.0 Ohm 0.125W 0805")
      (fields (field (name "Comment") "0805"))
      (libsource (lib "ZX_Spectrum_library") (part "RES_0R_0805"))
    )
    (comp (ref "R82")
      (value "Opc.")
      (footprint "RESC2012N_ZERO")
      (description "Resistor SMD chip 0.0 Ohm 0.125W 0805")
      (fields (field (name "Comment") "0805"))
      (libsource (lib "ZX_Spectrum_library") (part "RES_0R_0805"))
    )
    (comp (ref "R83")
      (value "Opc.")
      (footprint "RESC2012N_ZERO")
      (description "Resistor SMD chip 0.0 Ohm 0.125W 0805")
      (fields (field (name "Comment") "0805"))
      (libsource (lib "ZX_Spectrum_library") (part "RES_0R_0805"))
    )
    (comp (ref "R84")
      (value "Opc.")
      (footprint "RESC2012N_ZERO")
      (description "Resistor SMD chip 0.0 Ohm 0.125W 0805")
      (fields (field (name "Comment") "0805"))
      (libsource (lib "ZX_Spectrum_library") (part "RES_0R_0805"))
    )
    (comp (ref "R85")
      (value "Opc.")
      (footprint "RESC2012N_ZERO")
      (description "Resistor SMD chip 0.0 Ohm 0.125W 0805")
      (fields (field (name "Comment") "0805"))
      (libsource (lib "ZX_Spectrum_library") (part "RES_0R_0805"))
    )
    (comp (ref "R86")
      (value "Opc.")
      (footprint "RESC2012N_ZERO")
      (description "Resistor SMD chip 0.0 Ohm 0.125W 0805")
      (fields (field (name "Comment") "0805"))
      (libsource (lib "ZX_Spectrum_library") (part "RES_0R_0805"))
    )
    (comp (ref "R87")
      (value "Opc.")
      (footprint "RESC2012N_ZERO")
      (description "Resistor SMD chip 0.0 Ohm 0.125W 0805")
      (fields (field (name "Comment") "0805"))
      (libsource (lib "ZX_Spectrum_library") (part "RES_0R_0805"))
    )
    (comp (ref "R88")
      (value "Opc.")
      (footprint "RESC2012N_ZERO")
      (description "Resistor SMD chip 0.0 Ohm 0.125W 0805")
      (fields (field (name "Comment") "0805"))
      (libsource (lib "ZX_Spectrum_library") (part "RES_0R_0805"))
    )
    (comp (ref "R89")
      (value "Opc.")
      (footprint "RESC2012N_ZERO")
      (description "Resistor SMD chip 0.0 Ohm 0.125W 0805")
      (fields (field (name "Comment") "0805"))
      (libsource (lib "ZX_Spectrum_library") (part "RES_0R_0805"))
    )
    (comp (ref "R90")
      (value "Opc.")
      (footprint "RESC2012N_ZERO")
      (description "Resistor SMD chip 0.0 Ohm 0.125W 0805")
      (fields (field (name "Comment") "0805"))
      (libsource (lib "ZX_Spectrum_library") (part "RES_0R_0805"))
    )
    (comp (ref "R91")
      (value "Opc.")
      (footprint "RESC2012N_ZERO")
      (description "Resistor SMD chip 0.0 Ohm 0.125W 0805")
      (fields (field (name "Comment") "0805"))
      (libsource (lib "ZX_Spectrum_library") (part "RES_0R_0805"))
    )
    (comp (ref "R92")
      (value "Opc.")
      (footprint "RESC2012N_ZERO")
      (description "Resistor SMD chip 0.0 Ohm 0.125W 0805")
      (fields (field (name "Comment") "0805"))
      (libsource (lib "ZX_Spectrum_library") (part "RES_0R_0805"))
    )
    (comp (ref "R93")
      (value "Opc.")
      (footprint "RESC2012N_ZERO")
      (description "Resistor SMD chip 0.0 Ohm 0.125W 0805")
      (fields (field (name "Comment") "0805"))
      (libsource (lib "ZX_Spectrum_library") (part "RES_0R_0805"))
    )
    (comp (ref "R94")
      (value "Opc.")
      (footprint "RESC2012N_ZERO")
      (description "Resistor SMD chip 0.0 Ohm 0.125W 0805")
      (fields (field (name "Comment") "0805"))
      (libsource (lib "ZX_Spectrum_library") (part "RES_0R_0805"))
    )
    (comp (ref "R95")
      (value "Opc.")
      (footprint "RESC2012N_ZERO")
      (description "Resistor SMD chip 0.0 Ohm 0.125W 0805")
      (fields (field (name "Comment") "0805"))
      (libsource (lib "ZX_Spectrum_library") (part "RES_0R_0805"))
    )
    (comp (ref "R96")
      (value "Opc.")
      (footprint "RESC2012N_ZERO")
      (description "Resistor SMD chip 0.0 Ohm 0.125W 0805")
      (fields (field (name "Comment") "0805"))
      (libsource (lib "ZX_Spectrum_library") (part "RES_0R_0805"))
    )
    (comp (ref "ST1")
      (value "Cherry MX Stabilizer")
      (footprint "CHERRYMX_STAB")
      (description "Stabilizer for Cherry MX compatible switches")
      (libsource (lib "ZX_Spectrum_library") (part "Cherry MX Stabilizer"))
    )
    (comp (ref "ST2")
      (value "Cherry MX Stabilizer")
      (footprint "CHERRYMX_STAB")
      (description "Stabilizer for Cherry MX compatible switches")
      (libsource (lib "ZX_Spectrum_library") (part "Cherry MX Stabilizer"))
    )
    (comp (ref "ST3")
      (value "Cherry MX Stabilizer")
      (footprint "CHERRYMX_STAB")
      (description "Stabilizer for Cherry MX compatible switches")
      (libsource (lib "ZX_Spectrum_library") (part "Cherry MX Stabilizer"))
    )
    (comp (ref "ST4")
      (value "Cherry MX Stabilizer")
      (footprint "CHERRYMX_STAB")
      (description "Stabilizer for Cherry MX compatible switches")
      (libsource (lib "ZX_Spectrum_library") (part "Cherry MX Stabilizer"))
    )
    (comp (ref "ST5")
      (value "Cherry MX Stabilizer")
      (footprint "CHERRYMX_STAB")
      (description "Stabilizer for Cherry MX compatible switches")
      (libsource (lib "ZX_Spectrum_library") (part "Cherry MX Stabilizer"))
    )
    (comp (ref "ST6")
      (value "Cherry MX Stabilizer")
      (footprint "CHERRYMX_STAB")
      (description "Stabilizer for Cherry MX compatible switches")
      (libsource (lib "ZX_Spectrum_library") (part "Cherry MX Stabilizer"))
    )
    (comp (ref "ST7")
      (value "Cherry MX Stabilizer")
      (footprint "CHERRYMX_STAB")
      (description "Stabilizer for Cherry MX compatible switches")
      (libsource (lib "ZX_Spectrum_library") (part "Cherry MX Stabilizer"))
    )
    (comp (ref "ST8")
      (value "Cherry MX Stabilizer")
      (footprint "CHERRYMX_STAB")
      (description "Stabilizer for Cherry MX compatible switches")
      (libsource (lib "ZX_Spectrum_library") (part "Cherry MX Stabilizer"))
    )
    (comp (ref "ST9")
      (value "Cherry MX Stabilizer")
      (footprint "CHERRYMX_STAB")
      (description "Stabilizer for Cherry MX compatible switches")
      (libsource (lib "ZX_Spectrum_library") (part "Cherry MX Stabilizer"))
    )
    (comp (ref "ST10")
      (value "Cherry MX Stabilizer")
      (footprint "CHERRYMX_STAB")
      (description "Stabilizer for Cherry MX compatible switches")
      (libsource (lib "ZX_Spectrum_library") (part "Cherry MX Stabilizer"))
    )
    (comp (ref "ST11")
      (value "Cherry MX Stabilizer")
      (footprint "CHERRYMX_STAB")
      (description "Stabilizer for Cherry MX compatible switches")
      (libsource (lib "ZX_Spectrum_library") (part "Cherry MX Stabilizer"))
    )
    (comp (ref "ST12")
      (value "Cherry MX Stabilizer")
      (footprint "CHERRYMX_STAB")
      (description "Stabilizer for Cherry MX compatible switches")
      (libsource (lib "ZX_Spectrum_library") (part "Cherry MX Stabilizer"))
    )
    (comp (ref "ST13")
      (value "Cherry MX Stabilizer")
      (footprint "CHERRYMX_STAB")
      (description "Stabilizer for Cherry MX compatible switches")
      (libsource (lib "ZX_Spectrum_library") (part "Cherry MX Stabilizer"))
    )
    (comp (ref "ST14")
      (value "Cherry MX Stabilizer")
      (footprint "CHERRYMX_STAB")
      (description "Stabilizer for Cherry MX compatible switches")
      (libsource (lib "ZX_Spectrum_library") (part "Cherry MX Stabilizer"))
    )
    (comp (ref "ST15")
      (value "Cherry MX Stabilizer")
      (footprint "CHERRYMX_STAB")
      (description "Stabilizer for Cherry MX compatible switches")
      (libsource (lib "ZX_Spectrum_library") (part "Cherry MX Stabilizer"))
    )
    (comp (ref "ST16")
      (value "Cherry MX Stabilizer")
      (footprint "CHERRYMX_STAB")
      (description "Stabilizer for Cherry MX compatible switches")
      (libsource (lib "ZX_Spectrum_library") (part "Cherry MX Stabilizer"))
    )
    (comp (ref "SW1")
      (value "L-Alt")
      (footprint "CHERRYMX_5PIN")
      (description "Cherry MX keyboard switch")
      (libsource (lib "ZX_Spectrum_library") (part "Cherry MX"))
    )
    (comp (ref "SW2")
      (value "L-Shift")
      (footprint "CHERRYMX_5PIN")
      (description "Cherry MX keyboard switch")
      (libsource (lib "ZX_Spectrum_library") (part "Cherry MX"))
    )
    (comp (ref "SW3")
      (value "Ctrl")
      (footprint "CHERRYMX_5PIN")
      (description "Cherry MX keyboard switch")
      (libsource (lib "ZX_Spectrum_library") (part "Cherry MX"))
    )
    (comp (ref "SW4")
      (value "TAB")
      (footprint "CHERRYMX_5PIN")
      (description "Cherry MX keyboard switch")
      (libsource (lib "ZX_Spectrum_library") (part "Cherry MX"))
    )
    (comp (ref "SW5")
      (value "~")
      (footprint "CHERRYMX_5PIN")
      (description "Cherry MX keyboard switch")
      (libsource (lib "ZX_Spectrum_library") (part "Cherry MX"))
    )
    (comp (ref "SW6")
      (value "ESC")
      (footprint "CHERRYMX_5PIN")
      (description "Cherry MX keyboard switch")
      (libsource (lib "ZX_Spectrum_library") (part "Cherry MX"))
    )
    (comp (ref "SW7")
      (value "L-Amiga")
      (footprint "CHERRYMX_5PIN")
      (description "Cherry MX keyboard switch")
      (libsource (lib "ZX_Spectrum_library") (part "Cherry MX"))
    )
    (comp (ref "SW8")
      (value "< >")
      (footprint "CHERRYMX_5PIN")
      (description "Cherry MX keyboard switch")
      (libsource (lib "ZX_Spectrum_library") (part "Cherry MX"))
    )
    (comp (ref "SW9")
      (value "Caps Lock")
      (footprint "CHERRYMX_5PIN")
      (description "Cherry MX keyboard switch")
      (libsource (lib "ZX_Spectrum_library") (part "Cherry MX"))
    )
    (comp (ref "SW10")
      (value "Q")
      (footprint "CHERRYMX_5PIN")
      (description "Cherry MX keyboard switch")
      (libsource (lib "ZX_Spectrum_library") (part "Cherry MX"))
    )
    (comp (ref "SW11")
      (value "1")
      (footprint "CHERRYMX_5PIN")
      (description "Cherry MX keyboard switch")
      (libsource (lib "ZX_Spectrum_library") (part "Cherry MX"))
    )
    (comp (ref "SW12")
      (value "F1")
      (footprint "CHERRYMX_5PIN")
      (description "Cherry MX keyboard switch")
      (libsource (lib "ZX_Spectrum_library") (part "Cherry MX"))
    )
    (comp (ref "SW13")
      (value "Space")
      (footprint "CHERRYMX_5PIN")
      (description "Cherry MX keyboard switch")
      (libsource (lib "ZX_Spectrum_library") (part "Cherry MX"))
    )
    (comp (ref "SW14")
      (value "Z")
      (footprint "CHERRYMX_5PIN")
      (description "Cherry MX keyboard switch")
      (libsource (lib "ZX_Spectrum_library") (part "Cherry MX"))
    )
    (comp (ref "SW15")
      (value "A")
      (footprint "CHERRYMX_5PIN")
      (description "Cherry MX keyboard switch")
      (libsource (lib "ZX_Spectrum_library") (part "Cherry MX"))
    )
    (comp (ref "SW16")
      (value "W")
      (footprint "CHERRYMX_5PIN")
      (description "Cherry MX keyboard switch")
      (libsource (lib "ZX_Spectrum_library") (part "Cherry MX"))
    )
    (comp (ref "SW17")
      (value "2")
      (footprint "CHERRYMX_5PIN")
      (description "Cherry MX keyboard switch")
      (libsource (lib "ZX_Spectrum_library") (part "Cherry MX"))
    )
    (comp (ref "SW18")
      (value "F2")
      (footprint "CHERRYMX_5PIN")
      (description "Cherry MX keyboard switch")
      (libsource (lib "ZX_Spectrum_library") (part "Cherry MX"))
    )
    (comp (ref "SW19")
      (value "Num. *")
      (footprint "CHERRYMX_5PIN")
      (description "Cherry MX keyboard switch")
      (libsource (lib "ZX_Spectrum_library") (part "Cherry MX"))
    )
    (comp (ref "SW20")
      (value "X")
      (footprint "CHERRYMX_5PIN")
      (description "Cherry MX keyboard switch")
      (libsource (lib "ZX_Spectrum_library") (part "Cherry MX"))
    )
    (comp (ref "SW21")
      (value "S")
      (footprint "CHERRYMX_5PIN")
      (description "Cherry MX keyboard switch")
      (libsource (lib "ZX_Spectrum_library") (part "Cherry MX"))
    )
    (comp (ref "SW22")
      (value "E")
      (footprint "CHERRYMX_5PIN")
      (description "Cherry MX keyboard switch")
      (libsource (lib "ZX_Spectrum_library") (part "Cherry MX"))
    )
    (comp (ref "SW23")
      (value "3")
      (footprint "CHERRYMX_5PIN")
      (description "Cherry MX keyboard switch")
      (libsource (lib "ZX_Spectrum_library") (part "Cherry MX"))
    )
    (comp (ref "SW24")
      (value "F3")
      (footprint "CHERRYMX_5PIN")
      (description "Cherry MX keyboard switch")
      (libsource (lib "ZX_Spectrum_library") (part "Cherry MX"))
    )
    (comp (ref "SW25")
      (value "Num. -")
      (footprint "CHERRYMX_5PIN")
      (description "Cherry MX keyboard switch")
      (libsource (lib "ZX_Spectrum_library") (part "Cherry MX"))
    )
    (comp (ref "SW26")
      (value "C")
      (footprint "CHERRYMX_5PIN")
      (description "Cherry MX keyboard switch")
      (libsource (lib "ZX_Spectrum_library") (part "Cherry MX"))
    )
    (comp (ref "SW27")
      (value "D")
      (footprint "CHERRYMX_5PIN")
      (description "Cherry MX keyboard switch")
      (libsource (lib "ZX_Spectrum_library") (part "Cherry MX"))
    )
    (comp (ref "SW28")
      (value "R")
      (footprint "CHERRYMX_5PIN")
      (description "Cherry MX keyboard switch")
      (libsource (lib "ZX_Spectrum_library") (part "Cherry MX"))
    )
    (comp (ref "SW29")
      (value "4")
      (footprint "CHERRYMX_5PIN")
      (description "Cherry MX keyboard switch")
      (libsource (lib "ZX_Spectrum_library") (part "Cherry MX"))
    )
    (comp (ref "SW30")
      (value "F4")
      (footprint "CHERRYMX_5PIN")
      (description "Cherry MX keyboard switch")
      (libsource (lib "ZX_Spectrum_library") (part "Cherry MX"))
    )
    (comp (ref "SW31")
      (value "Num. Enter")
      (footprint "CHERRYMX_5PIN")
      (description "Cherry MX keyboard switch")
      (libsource (lib "ZX_Spectrum_library") (part "Cherry MX"))
    )
    (comp (ref "SW32")
      (value "V")
      (footprint "CHERRYMX_5PIN")
      (description "Cherry MX keyboard switch")
      (libsource (lib "ZX_Spectrum_library") (part "Cherry MX"))
    )
    (comp (ref "SW33")
      (value "F")
      (footprint "CHERRYMX_5PIN")
      (description "Cherry MX keyboard switch")
      (libsource (lib "ZX_Spectrum_library") (part "Cherry MX"))
    )
    (comp (ref "SW34")
      (value "T")
      (footprint "CHERRYMX_5PIN")
      (description "Cherry MX keyboard switch")
      (libsource (lib "ZX_Spectrum_library") (part "Cherry MX"))
    )
    (comp (ref "SW35")
      (value "5")
      (footprint "CHERRYMX_5PIN")
      (description "Cherry MX keyboard switch")
      (libsource (lib "ZX_Spectrum_library") (part "Cherry MX"))
    )
    (comp (ref "SW36")
      (value "F5")
      (footprint "CHERRYMX_5PIN")
      (description "Cherry MX keyboard switch")
      (libsource (lib "ZX_Spectrum_library") (part "Cherry MX"))
    )
    (comp (ref "SW37")
      (value "Num. /")
      (footprint "CHERRYMX_5PIN")
      (description "Cherry MX keyboard switch")
      (libsource (lib "ZX_Spectrum_library") (part "Cherry MX"))
    )
    (comp (ref "SW38")
      (value "B")
      (footprint "CHERRYMX_5PIN")
      (description "Cherry MX keyboard switch")
      (libsource (lib "ZX_Spectrum_library") (part "Cherry MX"))
    )
    (comp (ref "SW39")
      (value "G")
      (footprint "CHERRYMX_5PIN")
      (description "Cherry MX keyboard switch")
      (libsource (lib "ZX_Spectrum_library") (part "Cherry MX"))
    )
    (comp (ref "SW40")
      (value "Y")
      (footprint "CHERRYMX_5PIN")
      (description "Cherry MX keyboard switch")
      (libsource (lib "ZX_Spectrum_library") (part "Cherry MX"))
    )
    (comp (ref "SW41")
      (value "6")
      (footprint "CHERRYMX_5PIN")
      (description "Cherry MX keyboard switch")
      (libsource (lib "ZX_Spectrum_library") (part "Cherry MX"))
    )
    (comp (ref "SW42")
      (value "F6")
      (footprint "CHERRYMX_5PIN")
      (description "Cherry MX keyboard switch")
      (libsource (lib "ZX_Spectrum_library") (part "Cherry MX"))
    )
    (comp (ref "SW43")
      (value "Num. 9")
      (footprint "CHERRYMX_5PIN")
      (description "Cherry MX keyboard switch")
      (libsource (lib "ZX_Spectrum_library") (part "Cherry MX"))
    )
    (comp (ref "SW44")
      (value "N")
      (footprint "CHERRYMX_5PIN")
      (description "Cherry MX keyboard switch")
      (libsource (lib "ZX_Spectrum_library") (part "Cherry MX"))
    )
    (comp (ref "SW45")
      (value "H")
      (footprint "CHERRYMX_5PIN")
      (description "Cherry MX keyboard switch")
      (libsource (lib "ZX_Spectrum_library") (part "Cherry MX"))
    )
    (comp (ref "SW46")
      (value "U")
      (footprint "CHERRYMX_5PIN")
      (description "Cherry MX keyboard switch")
      (libsource (lib "ZX_Spectrum_library") (part "Cherry MX"))
    )
    (comp (ref "SW47")
      (value "7")
      (footprint "CHERRYMX_5PIN")
      (description "Cherry MX keyboard switch")
      (libsource (lib "ZX_Spectrum_library") (part "Cherry MX"))
    )
    (comp (ref "SW48")
      (value "F7")
      (footprint "CHERRYMX_5PIN")
      (description "Cherry MX keyboard switch")
      (libsource (lib "ZX_Spectrum_library") (part "Cherry MX"))
    )
    (comp (ref "SW49")
      (value "Num. 3")
      (footprint "CHERRYMX_5PIN")
      (description "Cherry MX keyboard switch")
      (libsource (lib "ZX_Spectrum_library") (part "Cherry MX"))
    )
    (comp (ref "SW50")
      (value "M")
      (footprint "CHERRYMX_5PIN")
      (description "Cherry MX keyboard switch")
      (libsource (lib "ZX_Spectrum_library") (part "Cherry MX"))
    )
    (comp (ref "SW51")
      (value "J")
      (footprint "CHERRYMX_5PIN")
      (description "Cherry MX keyboard switch")
      (libsource (lib "ZX_Spectrum_library") (part "Cherry MX"))
    )
    (comp (ref "SW52")
      (value "I")
      (footprint "CHERRYMX_5PIN")
      (description "Cherry MX keyboard switch")
      (libsource (lib "ZX_Spectrum_library") (part "Cherry MX"))
    )
    (comp (ref "SW53")
      (value "8")
      (footprint "CHERRYMX_5PIN")
      (description "Cherry MX keyboard switch")
      (libsource (lib "ZX_Spectrum_library") (part "Cherry MX"))
    )
    (comp (ref "SW54")
      (value "F8")
      (footprint "CHERRYMX_5PIN")
      (description "Cherry MX keyboard switch")
      (libsource (lib "ZX_Spectrum_library") (part "Cherry MX"))
    )
    (comp (ref "SW55")
      (value "Num. .")
      (footprint "CHERRYMX_5PIN")
      (description "Cherry MX keyboard switch")
      (libsource (lib "ZX_Spectrum_library") (part "Cherry MX"))
    )
    (comp (ref "SW56")
      (value ",")
      (footprint "CHERRYMX_5PIN")
      (description "Cherry MX keyboard switch")
      (libsource (lib "ZX_Spectrum_library") (part "Cherry MX"))
    )
    (comp (ref "SW57")
      (value "K")
      (footprint "CHERRYMX_5PIN")
      (description "Cherry MX keyboard switch")
      (libsource (lib "ZX_Spectrum_library") (part "Cherry MX"))
    )
    (comp (ref "SW58")
      (value "O")
      (footprint "CHERRYMX_5PIN")
      (description "Cherry MX keyboard switch")
      (libsource (lib "ZX_Spectrum_library") (part "Cherry MX"))
    )
    (comp (ref "SW59")
      (value "9")
      (footprint "CHERRYMX_5PIN")
      (description "Cherry MX keyboard switch")
      (libsource (lib "ZX_Spectrum_library") (part "Cherry MX"))
    )
    (comp (ref "SW60")
      (value "F9")
      (footprint "CHERRYMX_5PIN")
      (description "Cherry MX keyboard switch")
      (libsource (lib "ZX_Spectrum_library") (part "Cherry MX"))
    )
    (comp (ref "SW61")
      (value "Num. )")
      (footprint "CHERRYMX_5PIN")
      (description "Cherry MX keyboard switch")
      (libsource (lib "ZX_Spectrum_library") (part "Cherry MX"))
    )
    (comp (ref "SW62")
      (value ".")
      (footprint "CHERRYMX_5PIN")
      (description "Cherry MX keyboard switch")
      (libsource (lib "ZX_Spectrum_library") (part "Cherry MX"))
    )
    (comp (ref "SW63")
      (value "L")
      (footprint "CHERRYMX_5PIN")
      (description "Cherry MX keyboard switch")
      (libsource (lib "ZX_Spectrum_library") (part "Cherry MX"))
    )
    (comp (ref "SW64")
      (value "P")
      (footprint "CHERRYMX_5PIN")
      (description "Cherry MX keyboard switch")
      (libsource (lib "ZX_Spectrum_library") (part "Cherry MX"))
    )
    (comp (ref "SW65")
      (value "0")
      (footprint "CHERRYMX_5PIN")
      (description "Cherry MX keyboard switch")
      (libsource (lib "ZX_Spectrum_library") (part "Cherry MX"))
    )
    (comp (ref "SW66")
      (value "F10")
      (footprint "CHERRYMX_5PIN")
      (description "Cherry MX keyboard switch")
      (libsource (lib "ZX_Spectrum_library") (part "Cherry MX"))
    )
    (comp (ref "SW67")
      (value "R-Amiga")
      (footprint "CHERRYMX_5PIN")
      (description "Cherry MX keyboard switch")
      (libsource (lib "ZX_Spectrum_library") (part "Cherry MX"))
    )
    (comp (ref "SW68")
      (value "-")
      (footprint "CHERRYMX_5PIN")
      (description "Cherry MX keyboard switch")
      (libsource (lib "ZX_Spectrum_library") (part "Cherry MX"))
    )
    (comp (ref "SW69")
      (value "Ö")
      (footprint "CHERRYMX_5PIN")
      (description "Cherry MX keyboard switch")
      (libsource (lib "ZX_Spectrum_library") (part "Cherry MX"))
    )
    (comp (ref "SW70")
      (value "Ü")
      (footprint "CHERRYMX_5PIN")
      (description "Cherry MX keyboard switch")
      (libsource (lib "ZX_Spectrum_library") (part "Cherry MX"))
    )
    (comp (ref "SW71")
      (value "ß")
      (footprint "CHERRYMX_5PIN")
      (description "Cherry MX keyboard switch")
      (libsource (lib "ZX_Spectrum_library") (part "Cherry MX"))
    )
    (comp (ref "SW72")
      (value "Num. (")
      (footprint "CHERRYMX_5PIN")
      (description "Cherry MX keyboard switch")
      (libsource (lib "ZX_Spectrum_library") (part "Cherry MX"))
    )
    (comp (ref "SW73")
      (value "R-Alt")
      (footprint "CHERRYMX_5PIN")
      (description "Cherry MX keyboard switch")
      (libsource (lib "ZX_Spectrum_library") (part "Cherry MX"))
    )
    (comp (ref "SW74")
      (value "R-Shift")
      (footprint "CHERRYMX_5PIN")
      (description "Cherry MX keyboard switch")
      (libsource (lib "ZX_Spectrum_library") (part "Cherry MX"))
    )
    (comp (ref "SW75")
      (value "Ä")
      (footprint "CHERRYMX_5PIN")
      (description "Cherry MX keyboard switch")
      (libsource (lib "ZX_Spectrum_library") (part "Cherry MX"))
    )
    (comp (ref "SW76")
      (value "+")
      (footprint "CHERRYMX_5PIN")
      (description "Cherry MX keyboard switch")
      (libsource (lib "ZX_Spectrum_library") (part "Cherry MX"))
    )
    (comp (ref "SW77")
      (value "'")
      (footprint "CHERRYMX_5PIN")
      (description "Cherry MX keyboard switch")
      (libsource (lib "ZX_Spectrum_library") (part "Cherry MX"))
    )
    (comp (ref "SW78")
      (value "Num. 2")
      (footprint "CHERRYMX_5PIN")
      (description "Cherry MX keyboard switch")
      (libsource (lib "ZX_Spectrum_library") (part "Cherry MX"))
    )
    (comp (ref "SW79")
      (value "Num. 0")
      (footprint "CHERRYMX_5PIN")
      (description "Cherry MX keyboard switch")
      (libsource (lib "ZX_Spectrum_library") (part "Cherry MX"))
    )
    (comp (ref "SW80")
      (value "Left")
      (footprint "CHERRYMX_5PIN")
      (description "Cherry MX keyboard switch")
      (libsource (lib "ZX_Spectrum_library") (part "Cherry MX"))
    )
    (comp (ref "SW81")
      (value "#")
      (footprint "CHERRYMX_5PIN")
      (description "Cherry MX keyboard switch")
      (libsource (lib "ZX_Spectrum_library") (part "Cherry MX"))
    )
    (comp (ref "SW82")
      (value "Enter")
      (footprint "CHERRYMX_5PIN")
      (description "Cherry MX keyboard switch")
      (libsource (lib "ZX_Spectrum_library") (part "Cherry MX"))
    )
    (comp (ref "SW83")
      (value "\\")
      (footprint "CHERRYMX_5PIN")
      (description "Cherry MX keyboard switch")
      (libsource (lib "ZX_Spectrum_library") (part "Cherry MX"))
    )
    (comp (ref "SW84")
      (value "Num. 1")
      (footprint "CHERRYMX_5PIN")
      (description "Cherry MX keyboard switch")
      (libsource (lib "ZX_Spectrum_library") (part "Cherry MX"))
    )
    (comp (ref "SW85")
      (value "Num. 8")
      (footprint "CHERRYMX_5PIN")
      (description "Cherry MX keyboard switch")
      (libsource (lib "ZX_Spectrum_library") (part "Cherry MX"))
    )
    (comp (ref "SW86")
      (value "Down")
      (footprint "CHERRYMX_5PIN")
      (description "Cherry MX keyboard switch")
      (libsource (lib "ZX_Spectrum_library") (part "Cherry MX"))
    )
    (comp (ref "SW87")
      (value "Up")
      (footprint "CHERRYMX_5PIN")
      (description "Cherry MX keyboard switch")
      (libsource (lib "ZX_Spectrum_library") (part "Cherry MX"))
    )
    (comp (ref "SW88")
      (value "Help")
      (footprint "CHERRYMX_5PIN")
      (description "Cherry MX keyboard switch")
      (libsource (lib "ZX_Spectrum_library") (part "Cherry MX"))
    )
    (comp (ref "SW89")
      (value "BackSpace")
      (footprint "CHERRYMX_5PIN")
      (description "Cherry MX keyboard switch")
      (libsource (lib "ZX_Spectrum_library") (part "Cherry MX"))
    )
    (comp (ref "SW90")
      (value "Num. 7")
      (footprint "CHERRYMX_5PIN")
      (description "Cherry MX keyboard switch")
      (libsource (lib "ZX_Spectrum_library") (part "Cherry MX"))
    )
    (comp (ref "SW91")
      (value "Num. +")
      (footprint "CHERRYMX_5PIN")
      (description "Cherry MX keyboard switch")
      (libsource (lib "ZX_Spectrum_library") (part "Cherry MX"))
    )
    (comp (ref "SW92")
      (value "Right")
      (footprint "CHERRYMX_5PIN")
      (description "Cherry MX keyboard switch")
      (libsource (lib "ZX_Spectrum_library") (part "Cherry MX"))
    )
    (comp (ref "SW93")
      (value "Num. 4")
      (footprint "CHERRYMX_5PIN")
      (description "Cherry MX keyboard switch")
      (libsource (lib "ZX_Spectrum_library") (part "Cherry MX"))
    )
    (comp (ref "SW94")
      (value "Num. 6")
      (footprint "CHERRYMX_5PIN")
      (description "Cherry MX keyboard switch")
      (libsource (lib "ZX_Spectrum_library") (part "Cherry MX"))
    )
    (comp (ref "SW95")
      (value "Del")
      (footprint "CHERRYMX_5PIN")
      (description "Cherry MX keyboard switch")
      (libsource (lib "ZX_Spectrum_library") (part "Cherry MX"))
    )
    (comp (ref "SW96")
      (value "Num. 5")
      (footprint "CHERRYMX_5PIN")
      (description "Cherry MX keyboard switch")
      (libsource (lib "ZX_Spectrum_library") (part "Cherry MX"))
    )
  )
  (nets
    (net (code "1") (name "/CAPS_LED") (class "Default") (node (ref "SW9") (pin "3") (pintype "passive")))
    (net (code "2") (name "/COL0") (class "Default")
      (node (ref "D103") (pin "K") (pinfunction "K_K") (pintype "passive"))
      (node (ref "D104") (pin "K") (pinfunction "K_K") (pintype "passive"))
      (node (ref "D105") (pin "K") (pinfunction "K_K") (pintype "passive"))
      (node (ref "D106") (pin "K") (pinfunction "K_K") (pintype "passive"))
      (node (ref "D107") (pin "K") (pinfunction "K_K") (pintype "passive"))
      (node (ref "D108") (pin "K") (pinfunction "K_K") (pintype "passive"))
    )
    (net (code "3") (name "/COL1") (class "Default")
      (node (ref "D100") (pin "K") (pinfunction "K_K") (pintype "passive"))
      (node (ref "D101") (pin "K") (pinfunction "K_K") (pintype "passive"))
      (node (ref "D102") (pin "K") (pinfunction "K_K") (pintype "passive"))
      (node (ref "D97") (pin "K") (pinfunction "K_K") (pintype "passive"))
      (node (ref "D98") (pin "K") (pinfunction "K_K") (pintype "passive"))
      (node (ref "D99") (pin "K") (pinfunction "K_K") (pintype "passive"))
    )
    (net (code "4") (name "/COL2") (class "Default")
      (node (ref "D91") (pin "K") (pinfunction "K_K") (pintype "passive"))
      (node (ref "D92") (pin "K") (pinfunction "K_K") (pintype "passive"))
      (node (ref "D93") (pin "K") (pinfunction "K_K") (pintype "passive"))
      (node (ref "D94") (pin "K") (pinfunction "K_K") (pintype "passive"))
      (node (ref "D95") (pin "K") (pinfunction "K_K") (pintype "passive"))
      (node (ref "D96") (pin "K") (pinfunction "K_K") (pintype "passive"))
    )
    (net (code "5") (name "/COL3") (class "Default")
      (node (ref "D85") (pin "K") (pinfunction "K_K") (pintype "passive"))
      (node (ref "D86") (pin "K") (pinfunction "K_K") (pintype "passive"))
      (node (ref "D87") (pin "K") (pinfunction "K_K") (pintype "passive"))
      (node (ref "D88") (pin "K") (pinfunction "K_K") (pintype "passive"))
      (node (ref "D89") (pin "K") (pinfunction "K_K") (pintype "passive"))
      (node (ref "D90") (pin "K") (pinfunction "K_K") (pintype "passive"))
    )
    (net (code "6") (name "/COL4") (class "Default")
      (node (ref "D79") (pin "K") (pinfunction "K_K") (pintype "passive"))
      (node (ref "D80") (pin "K") (pinfunction "K_K") (pintype "passive"))
      (node (ref "D81") (pin "K") (pinfunction "K_K") (pintype "passive"))
      (node (ref "D82") (pin "K") (pinfunction "K_K") (pintype "passive"))
      (node (ref "D83") (pin "K") (pinfunction "K_K") (pintype "passive"))
      (node (ref "D84") (pin "K") (pinfunction "K_K") (pintype "passive"))
    )
    (net (code "7") (name "/COL5") (class "Default")
      (node (ref "D73") (pin "K") (pinfunction "K_K") (pintype "passive"))
      (node (ref "D74") (pin "K") (pinfunction "K_K") (pintype "passive"))
      (node (ref "D75") (pin "K") (pinfunction "K_K") (pintype "passive"))
      (node (ref "D76") (pin "K") (pinfunction "K_K") (pintype "passive"))
      (node (ref "D77") (pin "K") (pinfunction "K_K") (pintype "passive"))
      (node (ref "D78") (pin "K") (pinfunction "K_K") (pintype "passive"))
    )
    (net (code "8") (name "/COL6") (class "Default")
      (node (ref "D67") (pin "K") (pinfunction "K_K") (pintype "passive"))
      (node (ref "D68") (pin "K") (pinfunction "K_K") (pintype "passive"))
      (node (ref "D69") (pin "K") (pinfunction "K_K") (pintype "passive"))
      (node (ref "D70") (pin "K") (pinfunction "K_K") (pintype "passive"))
      (node (ref "D71") (pin "K") (pinfunction "K_K") (pintype "passive"))
      (node (ref "D72") (pin "K") (pinfunction "K_K") (pintype "passive"))
    )
    (net (code "9") (name "/COL7") (class "Default")
      (node (ref "D61") (pin "K") (pinfunction "K_K") (pintype "passive"))
      (node (ref "D62") (pin "K") (pinfunction "K_K") (pintype "passive"))
      (node (ref "D63") (pin "K") (pinfunction "K_K") (pintype "passive"))
      (node (ref "D64") (pin "K") (pinfunction "K_K") (pintype "passive"))
      (node (ref "D65") (pin "K") (pinfunction "K_K") (pintype "passive"))
      (node (ref "D66") (pin "K") (pinfunction "K_K") (pintype "passive"))
    )
    (net (code "10") (name "/COL8") (class "Default")
      (node (ref "D55") (pin "K") (pinfunction "K_K") (pintype "passive"))
      (node (ref "D56") (pin "K") (pinfunction "K_K") (pintype "passive"))
      (node (ref "D57") (pin "K") (pinfunction "K_K") (pintype "passive"))
      (node (ref "D58") (pin "K") (pinfunction "K_K") (pintype "passive"))
      (node (ref "D59") (pin "K") (pinfunction "K_K") (pintype "passive"))
      (node (ref "D60") (pin "K") (pinfunction "K_K") (pintype "passive"))
    )
    (net (code "11") (name "/COL9") (class "Default")
      (node (ref "D49") (pin "K") (pinfunction "K_K") (pintype "passive"))
      (node (ref "D50") (pin "K") (pinfunction "K_K") (pintype "passive"))
      (node (ref "D51") (pin "K") (pinfunction "K_K") (pintype "passive"))
      (node (ref "D52") (pin "K") (pinfunction "K_K") (pintype "passive"))
      (node (ref "D53") (pin "K") (pinfunction "K_K") (pintype "passive"))
      (node (ref "D54") (pin "K") (pinfunction "K_K") (pintype "passive"))
    )
    (net (code "12") (name "/COL10") (class "Default")
      (node (ref "D43") (pin "K") (pinfunction "K_K") (pintype "passive"))
      (node (ref "D44") (pin "K") (pinfunction "K_K") (pintype "passive"))
      (node (ref "D45") (pin "K") (pinfunction "K_K") (pintype "passive"))
      (node (ref "D46") (pin "K") (pinfunction "K_K") (pintype "passive"))
      (node (ref "D47") (pin "K") (pinfunction "K_K") (pintype "passive"))
      (node (ref "D48") (pin "K") (pinfunction "K_K") (pintype "passive"))
    )
    (net (code "13") (name "/COL11") (class "Default")
      (node (ref "D37") (pin "K") (pinfunction "K_K") (pintype "passive"))
      (node (ref "D38") (pin "K") (pinfunction "K_K") (pintype "passive"))
      (node (ref "D39") (pin "K") (pinfunction "K_K") (pintype "passive"))
      (node (ref "D40") (pin "K") (pinfunction "K_K") (pintype "passive"))
      (node (ref "D41") (pin "K") (pinfunction "K_K") (pintype "passive"))
      (node (ref "D42") (pin "K") (pinfunction "K_K") (pintype "passive"))
    )
    (net (code "14") (name "/COL12") (class "Default")
      (node (ref "D31") (pin "K") (pinfunction "K_K") (pintype "passive"))
      (node (ref "D32") (pin "K") (pinfunction "K_K") (pintype "passive"))
      (node (ref "D33") (pin "K") (pinfunction "K_K") (pintype "passive"))
      (node (ref "D34") (pin "K") (pinfunction "K_K") (pintype "passive"))
      (node (ref "D35") (pin "K") (pinfunction "K_K") (pintype "passive"))
      (node (ref "D36") (pin "K") (pinfunction "K_K") (pintype "passive"))
    )
    (net (code "15") (name "/COL13") (class "Default")
      (node (ref "D25") (pin "K") (pinfunction "K_K") (pintype "passive"))
      (node (ref "D26") (pin "K") (pinfunction "K_K") (pintype "passive"))
      (node (ref "D27") (pin "K") (pinfunction "K_K") (pintype "passive"))
      (node (ref "D28") (pin "K") (pinfunction "K_K") (pintype "passive"))
      (node (ref "D29") (pin "K") (pinfunction "K_K") (pintype "passive"))
      (node (ref "D30") (pin "K") (pinfunction "K_K") (pintype "passive"))
    )
    (net (code "16") (name "/COL14") (class "Default")
      (node (ref "D19") (pin "K") (pinfunction "K_K") (pintype "passive"))
      (node (ref "D20") (pin "K") (pinfunction "K_K") (pintype "passive"))
      (node (ref "D21") (pin "K") (pinfunction "K_K") (pintype "passive"))
      (node (ref "D22") (pin "K") (pinfunction "K_K") (pintype "passive"))
      (node (ref "D23") (pin "K") (pinfunction "K_K") (pintype "passive"))
      (node (ref "D24") (pin "K") (pinfunction "K_K") (pintype "passive"))
    )
    (net (code "17") (name "/COL15") (class "Default")
      (node (ref "D13") (pin "K") (pinfunction "K_K") (pintype "passive"))
      (node (ref "D14") (pin "K") (pinfunction "K_K") (pintype "passive"))
      (node (ref "D15") (pin "K") (pinfunction "K_K") (pintype "passive"))
      (node (ref "D16") (pin "K") (pinfunction "K_K") (pintype "passive"))
      (node (ref "D17") (pin "K") (pinfunction "K_K") (pintype "passive"))
      (node (ref "D18") (pin "K") (pinfunction "K_K") (pintype "passive"))
    )
    (net (code "18") (name "/ROW0") (class "Default")
      (node (ref "SW12") (pin "1") (pintype "passive"))
      (node (ref "SW18") (pin "1") (pintype "passive"))
      (node (ref "SW24") (pin "1") (pintype "passive"))
      (node (ref "SW30") (pin "1") (pintype "passive"))
      (node (ref "SW36") (pin "1") (pintype "passive"))
      (node (ref "SW42") (pin "1") (pintype "passive"))
      (node (ref "SW48") (pin "1") (pintype "passive"))
      (node (ref "SW54") (pin "1") (pintype "passive"))
      (node (ref "SW6") (pin "1") (pintype "passive"))
      (node (ref "SW60") (pin "1") (pintype "passive"))
      (node (ref "SW66") (pin "1") (pintype "passive"))
      (node (ref "SW72") (pin "1") (pintype "passive"))
      (node (ref "SW78") (pin "1") (pintype "passive"))
      (node (ref "SW84") (pin "1") (pintype "passive"))
      (node (ref "SW90") (pin "1") (pintype "passive"))
      (node (ref "SW96") (pin "1") (pintype "passive"))
    )
    (net (code "19") (name "/ROW1") (class "Default")
      (node (ref "SW11") (pin "1") (pintype "passive"))
      (node (ref "SW17") (pin "1") (pintype "passive"))
      (node (ref "SW23") (pin "1") (pintype "passive"))
      (node (ref "SW29") (pin "1") (pintype "passive"))
      (node (ref "SW35") (pin "1") (pintype "passive"))
      (node (ref "SW41") (pin "1") (pintype "passive"))
      (node (ref "SW47") (pin "1") (pintype "passive"))
      (node (ref "SW5") (pin "1") (pintype "passive"))
      (node (ref "SW53") (pin "1") (pintype "passive"))
      (node (ref "SW59") (pin "1") (pintype "passive"))
      (node (ref "SW65") (pin "1") (pintype "passive"))
      (node (ref "SW71") (pin "1") (pintype "passive"))
      (node (ref "SW77") (pin "1") (pintype "passive"))
      (node (ref "SW83") (pin "1") (pintype "passive"))
      (node (ref "SW89") (pin "1") (pintype "passive"))
      (node (ref "SW95") (pin "1") (pintype "passive"))
    )
    (net (code "20") (name "/ROW2") (class "Default")
      (node (ref "SW10") (pin "1") (pintype "passive"))
      (node (ref "SW16") (pin "1") (pintype "passive"))
      (node (ref "SW22") (pin "1") (pintype "passive"))
      (node (ref "SW28") (pin "1") (pintype "passive"))
      (node (ref "SW34") (pin "1") (pintype "passive"))
      (node (ref "SW4") (pin "1") (pintype "passive"))
      (node (ref "SW40") (pin "1") (pintype "passive"))
      (node (ref "SW46") (pin "1") (pintype "passive"))
      (node (ref "SW52") (pin "1") (pintype "passive"))
      (node (ref "SW58") (pin "1") (pintype "passive"))
      (node (ref "SW64") (pin "1") (pintype "passive"))
      (node (ref "SW70") (pin "1") (pintype "passive"))
      (node (ref "SW76") (pin "1") (pintype "passive"))
      (node (ref "SW82") (pin "1") (pintype "passive"))
      (node (ref "SW88") (pin "1") (pintype "passive"))
      (node (ref "SW94") (pin "1") (pintype "passive"))
    )
    (net (code "21") (name "/ROW3") (class "Default")
      (node (ref "SW15") (pin "1") (pintype "passive"))
      (node (ref "SW21") (pin "1") (pintype "passive"))
      (node (ref "SW27") (pin "1") (pintype "passive"))
      (node (ref "SW3") (pin "1") (pintype "passive"))
      (node (ref "SW33") (pin "1") (pintype "passive"))
      (node (ref "SW39") (pin "1") (pintype "passive"))
      (node (ref "SW45") (pin "1") (pintype "passive"))
      (node (ref "SW51") (pin "1") (pintype "passive"))
      (node (ref "SW57") (pin "1") (pintype "passive"))
      (node (ref "SW63") (pin "1") (pintype "passive"))
      (node (ref "SW69") (pin "1") (pintype "passive"))
      (node (ref "SW75") (pin "1") (pintype "passive"))
      (node (ref "SW81") (pin "1") (pintype "passive"))
      (node (ref "SW87") (pin "1") (pintype "passive"))
      (node (ref "SW9") (pin "1") (pintype "passive"))
      (node (ref "SW93") (pin "1") (pintype "passive"))
    )
    (net (code "22") (name "/ROW4") (class "Default")
      (node (ref "SW14") (pin "1") (pintype "passive"))
      (node (ref "SW2") (pin "1") (pintype "passive"))
      (node (ref "SW20") (pin "1") (pintype "passive"))
      (node (ref "SW26") (pin "1") (pintype "passive"))
      (node (ref "SW32") (pin "1") (pintype "passive"))
      (node (ref "SW38") (pin "1") (pintype "passive"))
      (node (ref "SW44") (pin "1") (pintype "passive"))
      (node (ref "SW50") (pin "1") (pintype "passive"))
      (node (ref "SW56") (pin "1") (pintype "passive"))
      (node (ref "SW62") (pin "1") (pintype "passive"))
      (node (ref "SW68") (pin "1") (pintype "passive"))
      (node (ref "SW74") (pin "1") (pintype "passive"))
      (node (ref "SW8") (pin "1") (pintype "passive"))
      (node (ref "SW80") (pin "1") (pintype "passive"))
      (node (ref "SW86") (pin "1") (pintype "passive"))
      (node (ref "SW92") (pin "1") (pintype "passive"))
    )
    (net (code "23") (name "/ROW5") (class "Default")
      (node (ref "SW1") (pin "1") (pintype "passive"))
      (node (ref "SW13") (pin "1") (pintype "passive"))
      (node (ref "SW19") (pin "1") (pintype "passive"))
      (node (ref "SW25") (pin "1") (pintype "passive"))
      (node (ref "SW31") (pin "1") (pintype "passive"))
      (node (ref "SW37") (pin "1") (pintype "passive"))
      (node (ref "SW43") (pin "1") (pintype "passive"))
      (node (ref "SW49") (pin "1") (pintype "passive"))
      (node (ref "SW55") (pin "1") (pintype "passive"))
      (node (ref "SW61") (pin "1") (pintype "passive"))
      (node (ref "SW67") (pin "1") (pintype "passive"))
      (node (ref "SW7") (pin "1") (pintype "passive"))
      (node (ref "SW73") (pin "1") (pintype "passive"))
      (node (ref "SW79") (pin "1") (pintype "passive"))
      (node (ref "SW85") (pin "1") (pintype "passive"))
      (node (ref "SW91") (pin "1") (pintype "passive"))
    )
    (net (code "24") (name "GND") (class "Default")
      (node (ref "R1") (pin "2") (pinfunction "2_2") (pintype "passive"))
      (node (ref "R10") (pin "2") (pinfunction "2_2") (pintype "passive"))
      (node (ref "R11") (pin "2") (pinfunction "2_2") (pintype "passive"))
      (node (ref "R12") (pin "2") (pinfunction "2_2") (pintype "passive"))
      (node (ref "R13") (pin "2") (pinfunction "2_2") (pintype "passive"))
      (node (ref "R14") (pin "2") (pinfunction "2_2") (pintype "passive"))
      (node (ref "R15") (pin "2") (pinfunction "2_2") (pintype "passive"))
      (node (ref "R16") (pin "2") (pinfunction "2_2") (pintype "passive"))
      (node (ref "R17") (pin "2") (pinfunction "2_2") (pintype "passive"))
      (node (ref "R18") (pin "2") (pinfunction "2_2") (pintype "passive"))
      (node (ref "R19") (pin "2") (pinfunction "2_2") (pintype "passive"))
      (node (ref "R2") (pin "2") (pinfunction "2_2") (pintype "passive"))
      (node (ref "R20") (pin "2") (pinfunction "2_2") (pintype "passive"))
      (node (ref "R21") (pin "2") (pinfunction "2_2") (pintype "passive"))
      (node (ref "R22") (pin "2") (pinfunction "2_2") (pintype "passive"))
      (node (ref "R23") (pin "2") (pinfunction "2_2") (pintype "passive"))
      (node (ref "R24") (pin "2") (pinfunction "2_2") (pintype "passive"))
      (node (ref "R25") (pin "2") (pinfunction "2_2") (pintype "passive"))
      (node (ref "R26") (pin "2") (pinfunction "2_2") (pintype "passive"))
      (node (ref "R27") (pin "2") (pinfunction "2_2") (pintype "passive"))
      (node (ref "R28") (pin "2") (pinfunction "2_2") (pintype "passive"))
      (node (ref "R29") (pin "2") (pinfunction "2_2") (pintype "passive"))
      (node (ref "R3") (pin "2") (pinfunction "2_2") (pintype "passive"))
      (node (ref "R30") (pin "2") (pinfunction "2_2") (pintype "passive"))
      (node (ref "R31") (pin "2") (pinfunction "2_2") (pintype "passive"))
      (node (ref "R32") (pin "2") (pinfunction "2_2") (pintype "passive"))
      (node (ref "R33") (pin "2") (pinfunction "2_2") (pintype "passive"))
      (node (ref "R34") (pin "2") (pinfunction "2_2") (pintype "passive"))
      (node (ref "R35") (pin "2") (pinfunction "2_2") (pintype "passive"))
      (node (ref "R36") (pin "2") (pinfunction "2_2") (pintype "passive"))
      (node (ref "R37") (pin "2") (pinfunction "2_2") (pintype "passive"))
      (node (ref "R38") (pin "2") (pinfunction "2_2") (pintype "passive"))
      (node (ref "R39") (pin "2") (pinfunction "2_2") (pintype "passive"))
      (node (ref "R4") (pin "2") (pinfunction "2_2") (pintype "passive"))
      (node (ref "R40") (pin "2") (pinfunction "2_2") (pintype "passive"))
      (node (ref "R41") (pin "2") (pinfunction "2_2") (pintype "passive"))
      (node (ref "R42") (pin "2") (pinfunction "2_2") (pintype "passive"))
      (node (ref "R43") (pin "2") (pinfunction "2_2") (pintype "passive"))
      (node (ref "R44") (pin "2") (pinfunction "2_2") (pintype "passive"))
      (node (ref "R45") (pin "2") (pinfunction "2_2") (pintype "passive"))
      (node (ref "R46") (pin "2") (pinfunction "2_2") (pintype "passive"))
      (node (ref "R47") (pin "2") (pinfunction "2_2") (pintype "passive"))
      (node (ref "R48") (pin "2") (pinfunction "2_2") (pintype "passive"))
      (node (ref "R49") (pin "2") (pinfunction "2_2") (pintype "passive"))
      (node (ref "R5") (pin "2") (pinfunction "2_2") (pintype "passive"))
      (node (ref "R50") (pin "2") (pinfunction "2_2") (pintype "passive"))
      (node (ref "R51") (pin "2") (pinfunction "2_2") (pintype "passive"))
      (node (ref "R52") (pin "2") (pinfunction "2_2") (pintype "passive"))
      (node (ref "R53") (pin "2") (pinfunction "2_2") (pintype "passive"))
      (node (ref "R54") (pin "2") (pinfunction "2_2") (pintype "passive"))
      (node (ref "R55") (pin "2") (pinfunction "2_2") (pintype "passive"))
      (node (ref "R56") (pin "2") (pinfunction "2_2") (pintype "passive"))
      (node (ref "R57") (pin "2") (pinfunction "2_2") (pintype "passive"))
      (node (ref "R58") (pin "2") (pinfunction "2_2") (pintype "passive"))
      (node (ref "R59") (pin "2") (pinfunction "2_2") (pintype "passive"))
      (node (ref "R6") (pin "2") (pinfunction "2_2") (pintype "passive"))
      (node (ref "R60") (pin "2") (pinfunction "2_2") (pintype "passive"))
      (node (ref "R61") (pin "2") (pinfunction "2_2") (pintype "passive"))
      (node (ref "R62") (pin "2") (pinfunction "2_2") (pintype "passive"))
      (node (ref "R63") (pin "2") (pinfunction "2_2") (pintype "passive"))
      (node (ref "R64") (pin "2") (pinfunction "2_2") (pintype "passive"))
      (node (ref "R65") (pin "2") (pinfunction "2_2") (pintype "passive"))
      (node (ref "R66") (pin "2") (pinfunction "2_2") (pintype "passive"))
      (node (ref "R67") (pin "2") (pinfunction "2_2") (pintype "passive"))
      (node (ref "R68") (pin "2") (pinfunction "2_2") (pintype "passive"))
      (node (ref "R69") (pin "2") (pinfunction "2_2") (pintype "passive"))
      (node (ref "R7") (pin "2") (pinfunction "2_2") (pintype "passive"))
      (node (ref "R70") (pin "2") (pinfunction "2_2") (pintype "passive"))
      (node (ref "R71") (pin "2") (pinfunction "2_2") (pintype "passive"))
      (node (ref "R72") (pin "2") (pinfunction "2_2") (pintype "passive"))
      (node (ref "R73") (pin "2") (pinfunction "2_2") (pintype "passive"))
      (node (ref "R74") (pin "2") (pinfunction "2_2") (pintype "passive"))
      (node (ref "R75") (pin "2") (pinfunction "2_2") (pintype "passive"))
      (node (ref "R76") (pin "2") (pinfunction "2_2") (pintype "passive"))
      (node (ref "R77") (pin "2") (pinfunction "2_2") (pintype "passive"))
      (node (ref "R78") (pin "2") (pinfunction "2_2") (pintype "passive"))
      (node (ref "R79") (pin "2") (pinfunction "2_2") (pintype "passive"))
      (node (ref "R8") (pin "2") (pinfunction "2_2") (pintype "passive"))
      (node (ref "R80") (pin "2") (pinfunction "2_2") (pintype "passive"))
      (node (ref "R81") (pin "2") (pinfunction "2_2") (pintype "passive"))
      (node (ref "R82") (pin "2") (pinfunction "2_2") (pintype "passive"))
      (node (ref "R83") (pin "2") (pinfunction "2_2") (pintype "passive"))
      (node (ref "R84") (pin "2") (pinfunction "2_2") (pintype "passive"))
      (node (ref "R85") (pin "2") (pinfunction "2_2") (pintype "passive"))
      (node (ref "R86") (pin "2") (pinfunction "2_2") (pintype "passive"))
      (node (ref "R87") (pin "2") (pinfunction "2_2") (pintype "passive"))
      (node (ref "R88") (pin "2") (pinfunction "2_2") (pintype "passive"))
      (node (ref "R89") (pin "2") (pinfunction "2_2") (pintype "passive"))
      (node (ref "R90") (pin "2") (pinfunction "2_2") (pintype "passive"))
      (node (ref "R91") (pin "2") (pinfunction "2_2") (pintype "passive"))
      (node (ref "R92") (pin "2") (pinfunction "2_2") (pintype "passive"))
      (node (ref "R93") (pin "2") (pinfunction "2_2") (pintype "passive"))
      (node (ref "R94") (pin "2") (pinfunction "2_2") (pintype "passive"))
      (node (ref "R95") (pin "2") (pinfunction "2_2") (pintype "passive"))
      (node (ref "R96") (pin "2") (pinfunction "2_2") (pintype "passive"))
      (node (ref "SW9") (pin "4") (pintype "passive"))
    )
    (net (code "25") (name "Net-(D13-PadA)") (class "Default")
      (node (ref "D13") (pin "A") (pinfunction "A_A") (pintype "passive"))
      (node (ref "SW1") (pin "2") (pintype "passive"))
    )
    (net (code "26") (name "Net-(D14-PadA)") (class "Default")
      (node (ref "D14") (pin "A") (pinfunction "A_A") (pintype "passive"))
      (node (ref "SW2") (pin "2") (pintype "passive"))
    )
    (net (code "27") (name "Net-(D15-PadA)") (class "Default")
      (node (ref "D15") (pin "A") (pinfunction "A_A") (pintype "passive"))
      (node (ref "SW3") (pin "2") (pintype "passive"))
    )
    (net (code "28") (name "Net-(D16-PadA)") (class "Default")
      (node (ref "D16") (pin "A") (pinfunction "A_A") (pintype "passive"))
      (node (ref "SW4") (pin "2") (pintype "passive"))
    )
    (net (code "29") (name "Net-(D17-PadA)") (class "Default")
      (node (ref "D17") (pin "A") (pinfunction "A_A") (pintype "passive"))
      (node (ref "SW5") (pin "2") (pintype "passive"))
    )
    (net (code "30") (name "Net-(D18-PadA)") (class "Default")
      (node (ref "D18") (pin "A") (pinfunction "A_A") (pintype "passive"))
      (node (ref "SW6") (pin "2") (pintype "passive"))
    )
    (net (code "31") (name "Net-(D19-PadA)") (class "Default")
      (node (ref "D19") (pin "A") (pinfunction "A_A") (pintype "passive"))
      (node (ref "SW7") (pin "2") (pintype "passive"))
    )
    (net (code "32") (name "Net-(D20-PadA)") (class "Default")
      (node (ref "D20") (pin "A") (pinfunction "A_A") (pintype "passive"))
      (node (ref "SW8") (pin "2") (pintype "passive"))
    )
    (net (code "33") (name "Net-(D21-PadA)") (class "Default")
      (node (ref "D21") (pin "A") (pinfunction "A_A") (pintype "passive"))
      (node (ref "SW9") (pin "2") (pintype "passive"))
    )
    (net (code "34") (name "Net-(D22-PadA)") (class "Default")
      (node (ref "D22") (pin "A") (pinfunction "A_A") (pintype "passive"))
      (node (ref "SW10") (pin "2") (pintype "passive"))
    )
    (net (code "35") (name "Net-(D23-PadA)") (class "Default")
      (node (ref "D23") (pin "A") (pinfunction "A_A") (pintype "passive"))
      (node (ref "SW11") (pin "2") (pintype "passive"))
    )
    (net (code "36") (name "Net-(D24-PadA)") (class "Default")
      (node (ref "D24") (pin "A") (pinfunction "A_A") (pintype "passive"))
      (node (ref "SW12") (pin "2") (pintype "passive"))
    )
    (net (code "37") (name "Net-(D25-PadA)") (class "Default")
      (node (ref "D25") (pin "A") (pinfunction "A_A") (pintype "passive"))
      (node (ref "SW13") (pin "2") (pintype "passive"))
    )
    (net (code "38") (name "Net-(D26-PadA)") (class "Default")
      (node (ref "D26") (pin "A") (pinfunction "A_A") (pintype "passive"))
      (node (ref "SW14") (pin "2") (pintype "passive"))
    )
    (net (code "39") (name "Net-(D27-PadA)") (class "Default")
      (node (ref "D27") (pin "A") (pinfunction "A_A") (pintype "passive"))
      (node (ref "SW15") (pin "2") (pintype "passive"))
    )
    (net (code "40") (name "Net-(D28-PadA)") (class "Default")
      (node (ref "D28") (pin "A") (pinfunction "A_A") (pintype "passive"))
      (node (ref "SW16") (pin "2") (pintype "passive"))
    )
    (net (code "41") (name "Net-(D29-PadA)") (class "Default")
      (node (ref "D29") (pin "A") (pinfunction "A_A") (pintype "passive"))
      (node (ref "SW17") (pin "2") (pintype "passive"))
    )
    (net (code "42") (name "Net-(D30-PadA)") (class "Default")
      (node (ref "D30") (pin "A") (pinfunction "A_A") (pintype "passive"))
      (node (ref "SW18") (pin "2") (pintype "passive"))
    )
    (net (code "43") (name "Net-(D31-PadA)") (class "Default")
      (node (ref "D31") (pin "A") (pinfunction "A_A") (pintype "passive"))
      (node (ref "SW19") (pin "2") (pintype "passive"))
    )
    (net (code "44") (name "Net-(D32-PadA)") (class "Default")
      (node (ref "D32") (pin "A") (pinfunction "A_A") (pintype "passive"))
      (node (ref "SW20") (pin "2") (pintype "passive"))
    )
    (net (code "45") (name "Net-(D33-PadA)") (class "Default")
      (node (ref "D33") (pin "A") (pinfunction "A_A") (pintype "passive"))
      (node (ref "SW21") (pin "2") (pintype "passive"))
    )
    (net (code "46") (name "Net-(D34-PadA)") (class "Default")
      (node (ref "D34") (pin "A") (pinfunction "A_A") (pintype "passive"))
      (node (ref "SW22") (pin "2") (pintype "passive"))
    )
    (net (code "47") (name "Net-(D35-PadA)") (class "Default")
      (node (ref "D35") (pin "A") (pinfunction "A_A") (pintype "passive"))
      (node (ref "SW23") (pin "2") (pintype "passive"))
    )
    (net (code "48") (name "Net-(D36-PadA)") (class "Default")
      (node (ref "D36") (pin "A") (pinfunction "A_A") (pintype "passive"))
      (node (ref "SW24") (pin "2") (pintype "passive"))
    )
    (net (code "49") (name "Net-(D37-PadA)") (class "Default")
      (node (ref "D37") (pin "A") (pinfunction "A_A") (pintype "passive"))
      (node (ref "SW25") (pin "2") (pintype "passive"))
    )
    (net (code "50") (name "Net-(D38-PadA)") (class "Default")
      (node (ref "D38") (pin "A") (pinfunction "A_A") (pintype "passive"))
      (node (ref "SW26") (pin "2") (pintype "passive"))
    )
    (net (code "51") (name "Net-(D39-PadA)") (class "Default")
      (node (ref "D39") (pin "A") (pinfunction "A_A") (pintype "passive"))
      (node (ref "SW27") (pin "2") (pintype "passive"))
    )
    (net (code "52") (name "Net-(D40-PadA)") (class "Default")
      (node (ref "D40") (pin "A") (pinfunction "A_A") (pintype "passive"))
      (node (ref "SW28") (pin "2") (pintype "passive"))
    )
    (net (code "53") (name "Net-(D41-PadA)") (class "Default")
      (node (ref "D41") (pin "A") (pinfunction "A_A") (pintype "passive"))
      (node (ref "SW29") (pin "2") (pintype "passive"))
    )
    (net (code "54") (name "Net-(D42-PadA)") (class "Default")
      (node (ref "D42") (pin "A") (pinfunction "A_A") (pintype "passive"))
      (node (ref "SW30") (pin "2") (pintype "passive"))
    )
    (net (code "55") (name "Net-(D43-PadA)") (class "Default")
      (node (ref "D43") (pin "A") (pinfunction "A_A") (pintype "passive"))
      (node (ref "SW31") (pin "2") (pintype "passive"))
    )
    (net (code "56") (name "Net-(D44-PadA)") (class "Default")
      (node (ref "D44") (pin "A") (pinfunction "A_A") (pintype "passive"))
      (node (ref "SW32") (pin "2") (pintype "passive"))
    )
    (net (code "57") (name "Net-(D45-PadA)") (class "Default")
      (node (ref "D45") (pin "A") (pinfunction "A_A") (pintype "passive"))
      (node (ref "SW33") (pin "2") (pintype "passive"))
    )
    (net (code "58") (name "Net-(D46-PadA)") (class "Default")
      (node (ref "D46") (pin "A") (pinfunction "A_A") (pintype "passive"))
      (node (ref "SW34") (pin "2") (pintype "passive"))
    )
    (net (code "59") (name "Net-(D47-PadA)") (class "Default")
      (node (ref "D47") (pin "A") (pinfunction "A_A") (pintype "passive"))
      (node (ref "SW35") (pin "2") (pintype "passive"))
    )
    (net (code "60") (name "Net-(D48-PadA)") (class "Default")
      (node (ref "D48") (pin "A") (pinfunction "A_A") (pintype "passive"))
      (node (ref "SW36") (pin "2") (pintype "passive"))
    )
    (net (code "61") (name "Net-(D49-PadA)") (class "Default")
      (node (ref "D49") (pin "A") (pinfunction "A_A") (pintype "passive"))
      (node (ref "SW37") (pin "2") (pintype "passive"))
    )
    (net (code "62") (name "Net-(D50-PadA)") (class "Default")
      (node (ref "D50") (pin "A") (pinfunction "A_A") (pintype "passive"))
      (node (ref "SW38") (pin "2") (pintype "passive"))
    )
    (net (code "63") (name "Net-(D51-PadA)") (class "Default")
      (node (ref "D51") (pin "A") (pinfunction "A_A") (pintype "passive"))
      (node (ref "SW39") (pin "2") (pintype "passive"))
    )
    (net (code "64") (name "Net-(D52-PadA)") (class "Default")
      (node (ref "D52") (pin "A") (pinfunction "A_A") (pintype "passive"))
      (node (ref "SW40") (pin "2") (pintype "passive"))
    )
    (net (code "65") (name "Net-(D53-PadA)") (class "Default")
      (node (ref "D53") (pin "A") (pinfunction "A_A") (pintype "passive"))
      (node (ref "SW41") (pin "2") (pintype "passive"))
    )
    (net (code "66") (name "Net-(D54-PadA)") (class "Default")
      (node (ref "D54") (pin "A") (pinfunction "A_A") (pintype "passive"))
      (node (ref "SW42") (pin "2") (pintype "passive"))
    )
    (net (code "67") (name "Net-(D55-PadA)") (class "Default")
      (node (ref "D55") (pin "A") (pinfunction "A_A") (pintype "passive"))
      (node (ref "SW43") (pin "2") (pintype "passive"))
    )
    (net (code "68") (name "Net-(D56-PadA)") (class "Default")
      (node (ref "D56") (pin "A") (pinfunction "A_A") (pintype "passive"))
      (node (ref "SW44") (pin "2") (pintype "passive"))
    )
    (net (code "69") (name "Net-(D57-PadA)") (class "Default")
      (node (ref "D57") (pin "A") (pinfunction "A_A") (pintype "passive"))
      (node (ref "SW45") (pin "2") (pintype "passive"))
    )
    (net (code "70") (name "Net-(D58-PadA)") (class "Default")
      (node (ref "D58") (pin "A") (pinfunction "A_A") (pintype "passive"))
      (node (ref "SW46") (pin "2") (pintype "passive"))
    )
    (net (code "71") (name "Net-(D59-PadA)") (class "Default")
      (node (ref "D59") (pin "A") (pinfunction "A_A") (pintype "passive"))
      (node (ref "SW47") (pin "2") (pintype "passive"))
    )
    (net (code "72") (name "Net-(D60-PadA)") (class "Default")
      (node (ref "D60") (pin "A") (pinfunction "A_A") (pintype "passive"))
      (node (ref "SW48") (pin "2") (pintype "passive"))
    )
    (net (code "73") (name "Net-(D61-PadA)") (class "Default")
      (node (ref "D61") (pin "A") (pinfunction "A_A") (pintype "passive"))
      (node (ref "SW49") (pin "2") (pintype "passive"))
    )
    (net (code "74") (name "Net-(D62-PadA)") (class "Default")
      (node (ref "D62") (pin "A") (pinfunction "A_A") (pintype "passive"))
      (node (ref "SW50") (pin "2") (pintype "passive"))
    )
    (net (code "75") (name "Net-(D63-PadA)") (class "Default")
      (node (ref "D63") (pin "A") (pinfunction "A_A") (pintype "passive"))
      (node (ref "SW51") (pin "2") (pintype "passive"))
    )
    (net (code "76") (name "Net-(D64-PadA)") (class "Default")
      (node (ref "D64") (pin "A") (pinfunction "A_A") (pintype "passive"))
      (node (ref "SW52") (pin "2") (pintype "passive"))
    )
    (net (code "77") (name "Net-(D65-PadA)") (class "Default")
      (node (ref "D65") (pin "A") (pinfunction "A_A") (pintype "passive"))
      (node (ref "SW53") (pin "2") (pintype "passive"))
    )
    (net (code "78") (name "Net-(D66-PadA)") (class "Default")
      (node (ref "D66") (pin "A") (pinfunction "A_A") (pintype "passive"))
      (node (ref "SW54") (pin "2") (pintype "passive"))
    )
    (net (code "79") (name "Net-(D67-PadA)") (class "Default")
      (node (ref "D67") (pin "A") (pinfunction "A_A") (pintype "passive"))
      (node (ref "SW55") (pin "2") (pintype "passive"))
    )
    (net (code "80") (name "Net-(D68-PadA)") (class "Default")
      (node (ref "D68") (pin "A") (pinfunction "A_A") (pintype "passive"))
      (node (ref "SW56") (pin "2") (pintype "passive"))
    )
    (net (code "81") (name "Net-(D69-PadA)") (class "Default")
      (node (ref "D69") (pin "A") (pinfunction "A_A") (pintype "passive"))
      (node (ref "SW57") (pin "2") (pintype "passive"))
    )
    (net (code "82") (name "Net-(D70-PadA)") (class "Default")
      (node (ref "D70") (pin "A") (pinfunction "A_A") (pintype "passive"))
      (node (ref "SW58") (pin "2") (pintype "passive"))
    )
    (net (code "83") (name "Net-(D71-PadA)") (class "Default")
      (node (ref "D71") (pin "A") (pinfunction "A_A") (pintype "passive"))
      (node (ref "SW59") (pin "2") (pintype "passive"))
    )
    (net (code "84") (name "Net-(D72-PadA)") (class "Default")
      (node (ref "D72") (pin "A") (pinfunction "A_A") (pintype "passive"))
      (node (ref "SW60") (pin "2") (pintype "passive"))
    )
    (net (code "85") (name "Net-(D73-PadA)") (class "Default")
      (node (ref "D73") (pin "A") (pinfunction "A_A") (pintype "passive"))
      (node (ref "SW61") (pin "2") (pintype "passive"))
    )
    (net (code "86") (name "Net-(D74-PadA)") (class "Default")
      (node (ref "D74") (pin "A") (pinfunction "A_A") (pintype "passive"))
      (node (ref "SW62") (pin "2") (pintype "passive"))
    )
    (net (code "87") (name "Net-(D75-PadA)") (class "Default")
      (node (ref "D75") (pin "A") (pinfunction "A_A") (pintype "passive"))
      (node (ref "SW63") (pin "2") (pintype "passive"))
    )
    (net (code "88") (name "Net-(D76-PadA)") (class "Default")
      (node (ref "D76") (pin "A") (pinfunction "A_A") (pintype "passive"))
      (node (ref "SW64") (pin "2") (pintype "passive"))
    )
    (net (code "89") (name "Net-(D77-PadA)") (class "Default")
      (node (ref "D77") (pin "A") (pinfunction "A_A") (pintype "passive"))
      (node (ref "SW65") (pin "2") (pintype "passive"))
    )
    (net (code "90") (name "Net-(D78-PadA)") (class "Default")
      (node (ref "D78") (pin "A") (pinfunction "A_A") (pintype "passive"))
      (node (ref "SW66") (pin "2") (pintype "passive"))
    )
    (net (code "91") (name "Net-(D79-PadA)") (class "Default")
      (node (ref "D79") (pin "A") (pinfunction "A_A") (pintype "passive"))
      (node (ref "SW67") (pin "2") (pintype "passive"))
    )
    (net (code "92") (name "Net-(D80-PadA)") (class "Default")
      (node (ref "D80") (pin "A") (pinfunction "A_A") (pintype "passive"))
      (node (ref "SW68") (pin "2") (pintype "passive"))
    )
    (net (code "93") (name "Net-(D81-PadA)") (class "Default")
      (node (ref "D81") (pin "A") (pinfunction "A_A") (pintype "passive"))
      (node (ref "SW69") (pin "2") (pintype "passive"))
    )
    (net (code "94") (name "Net-(D82-PadA)") (class "Default")
      (node (ref "D82") (pin "A") (pinfunction "A_A") (pintype "passive"))
      (node (ref "SW70") (pin "2") (pintype "passive"))
    )
    (net (code "95") (name "Net-(D83-PadA)") (class "Default")
      (node (ref "D83") (pin "A") (pinfunction "A_A") (pintype "passive"))
      (node (ref "SW71") (pin "2") (pintype "passive"))
    )
    (net (code "96") (name "Net-(D84-PadA)") (class "Default")
      (node (ref "D84") (pin "A") (pinfunction "A_A") (pintype "passive"))
      (node (ref "SW72") (pin "2") (pintype "passive"))
    )
    (net (code "97") (name "Net-(D85-PadA)") (class "Default")
      (node (ref "D85") (pin "A") (pinfunction "A_A") (pintype "passive"))
      (node (ref "SW73") (pin "2") (pintype "passive"))
    )
    (net (code "98") (name "Net-(D86-PadA)") (class "Default")
      (node (ref "D86") (pin "A") (pinfunction "A_A") (pintype "passive"))
      (node (ref "SW74") (pin "2") (pintype "passive"))
    )
    (net (code "99") (name "Net-(D87-PadA)") (class "Default")
      (node (ref "D87") (pin "A") (pinfunction "A_A") (pintype "passive"))
      (node (ref "SW75") (pin "2") (pintype "passive"))
    )
    (net (code "100") (name "Net-(D88-PadA)") (class "Default")
      (node (ref "D88") (pin "A") (pinfunction "A_A") (pintype "passive"))
      (node (ref "SW76") (pin "2") (pintype "passive"))
    )
    (net (code "101") (name "Net-(D89-PadA)") (class "Default")
      (node (ref "D89") (pin "A") (pinfunction "A_A") (pintype "passive"))
      (node (ref "SW77") (pin "2") (pintype "passive"))
    )
    (net (code "102") (name "Net-(D90-PadA)") (class "Default")
      (node (ref "D90") (pin "A") (pinfunction "A_A") (pintype "passive"))
      (node (ref "SW78") (pin "2") (pintype "passive"))
    )
    (net (code "103") (name "Net-(D91-PadA)") (class "Default")
      (node (ref "D91") (pin "A") (pinfunction "A_A") (pintype "passive"))
      (node (ref "SW79") (pin "2") (pintype "passive"))
    )
    (net (code "104") (name "Net-(D92-PadA)") (class "Default")
      (node (ref "D92") (pin "A") (pinfunction "A_A") (pintype "passive"))
      (node (ref "SW80") (pin "2") (pintype "passive"))
    )
    (net (code "105") (name "Net-(D93-PadA)") (class "Default")
      (node (ref "D93") (pin "A") (pinfunction "A_A") (pintype "passive"))
      (node (ref "SW81") (pin "2") (pintype "passive"))
    )
    (net (code "106") (name "Net-(D94-PadA)") (class "Default")
      (node (ref "D94") (pin "A") (pinfunction "A_A") (pintype "passive"))
      (node (ref "SW82") (pin "2") (pintype "passive"))
    )
    (net (code "107") (name "Net-(D95-PadA)") (class "Default")
      (node (ref "D95") (pin "A") (pinfunction "A_A") (pintype "passive"))
      (node (ref "SW83") (pin "2") (pintype "passive"))
    )
    (net (code "108") (name "Net-(D96-PadA)") (class "Default")
      (node (ref "D96") (pin "A") (pinfunction "A_A") (pintype "passive"))
      (node (ref "SW84") (pin "2") (pintype "passive"))
    )
    (net (code "109") (name "Net-(D97-PadA)") (class "Default")
      (node (ref "D97") (pin "A") (pinfunction "A_A") (pintype "passive"))
      (node (ref "SW85") (pin "2") (pintype "passive"))
    )
    (net (code "110") (name "Net-(D98-PadA)") (class "Default")
      (node (ref "D98") (pin "A") (pinfunction "A_A") (pintype "passive"))
      (node (ref "SW86") (pin "2") (pintype "passive"))
    )
    (net (code "111") (name "Net-(D99-PadA)") (class "Default")
      (node (ref "D99") (pin "A") (pinfunction "A_A") (pintype "passive"))
      (node (ref "SW87") (pin "2") (pintype "passive"))
    )
    (net (code "112") (name "Net-(D100-PadA)") (class "Default")
      (node (ref "D100") (pin "A") (pinfunction "A_A") (pintype "passive"))
      (node (ref "SW88") (pin "2") (pintype "passive"))
    )
    (net (code "113") (name "Net-(D101-PadA)") (class "Default")
      (node (ref "D101") (pin "A") (pinfunction "A_A") (pintype "passive"))
      (node (ref "SW89") (pin "2") (pintype "passive"))
    )
    (net (code "114") (name "Net-(D102-PadA)") (class "Default")
      (node (ref "D102") (pin "A") (pinfunction "A_A") (pintype "passive"))
      (node (ref "SW90") (pin "2") (pintype "passive"))
    )
    (net (code "115") (name "Net-(D103-PadA)") (class "Default")
      (node (ref "D103") (pin "A") (pinfunction "A_A") (pintype "passive"))
      (node (ref "SW91") (pin "2") (pintype "passive"))
    )
    (net (code "116") (name "Net-(D104-PadA)") (class "Default")
      (node (ref "D104") (pin "A") (pinfunction "A_A") (pintype "passive"))
      (node (ref "SW92") (pin "2") (pintype "passive"))
    )
    (net (code "117") (name "Net-(D105-PadA)") (class "Default")
      (node (ref "D105") (pin "A") (pinfunction "A_A") (pintype "passive"))
      (node (ref "SW93") (pin "2") (pintype "passive"))
    )
    (net (code "118") (name "Net-(D106-PadA)") (class "Default")
      (node (ref "D106") (pin "A") (pinfunction "A_A") (pintype "passive"))
      (node (ref "SW94") (pin "2") (pintype "passive"))
    )
    (net (code "119") (name "Net-(D107-PadA)") (class "Default")
      (node (ref "D107") (pin "A") (pinfunction "A_A") (pintype "passive"))
      (node (ref "SW95") (pin "2") (pintype "passive"))
    )
    (net (code "120") (name "Net-(D108-PadA)") (class "Default")
      (node (ref "D108") (pin "A") (pinfunction "A_A") (pintype "passive"))
      (node (ref "SW96") (pin "2") (pintype "passive"))
    )
    (net (code "121") (name "Net-(R1-Pad1)") (class "Default")
      (node (ref "R1") (pin "1") (pinfunction "1_1") (pintype "passive"))
      (node (ref "SW1") (pin "4") (pintype "passive"))
    )
    (net (code "122") (name "Net-(R2-Pad1)") (class "Default")
      (node (ref "R2") (pin "1") (pinfunction "1_1") (pintype "passive"))
      (node (ref "SW2") (pin "4") (pintype "passive"))
    )
    (net (code "123") (name "Net-(R3-Pad1)") (class "Default")
      (node (ref "R3") (pin "1") (pinfunction "1_1") (pintype "passive"))
      (node (ref "SW3") (pin "4") (pintype "passive"))
    )
    (net (code "124") (name "Net-(R4-Pad1)") (class "Default")
      (node (ref "R4") (pin "1") (pinfunction "1_1") (pintype "passive"))
      (node (ref "SW4") (pin "4") (pintype "passive"))
    )
    (net (code "125") (name "Net-(R5-Pad1)") (class "Default")
      (node (ref "R5") (pin "1") (pinfunction "1_1") (pintype "passive"))
      (node (ref "SW5") (pin "4") (pintype "passive"))
    )
    (net (code "126") (name "Net-(R6-Pad1)") (class "Default")
      (node (ref "R6") (pin "1") (pinfunction "1_1") (pintype "passive"))
      (node (ref "SW6") (pin "4") (pintype "passive"))
    )
    (net (code "127") (name "Net-(R7-Pad1)") (class "Default")
      (node (ref "R7") (pin "1") (pinfunction "1_1") (pintype "passive"))
      (node (ref "SW7") (pin "4") (pintype "passive"))
    )
    (net (code "128") (name "Net-(R8-Pad1)") (class "Default")
      (node (ref "R8") (pin "1") (pinfunction "1_1") (pintype "passive"))
      (node (ref "SW8") (pin "4") (pintype "passive"))
    )
    (net (code "129") (name "Net-(R10-Pad1)") (class "Default")
      (node (ref "R10") (pin "1") (pinfunction "1_1") (pintype "passive"))
      (node (ref "SW10") (pin "4") (pintype "passive"))
    )
    (net (code "130") (name "Net-(R11-Pad1)") (class "Default")
      (node (ref "R11") (pin "1") (pinfunction "1_1") (pintype "passive"))
      (node (ref "SW11") (pin "4") (pintype "passive"))
    )
    (net (code "131") (name "Net-(R12-Pad1)") (class "Default")
      (node (ref "R12") (pin "1") (pinfunction "1_1") (pintype "passive"))
      (node (ref "SW12") (pin "4") (pintype "passive"))
    )
    (net (code "132") (name "Net-(R13-Pad1)") (class "Default")
      (node (ref "R13") (pin "1") (pinfunction "1_1") (pintype "passive"))
      (node (ref "SW13") (pin "4") (pintype "passive"))
    )
    (net (code "133") (name "Net-(R14-Pad1)") (class "Default")
      (node (ref "R14") (pin "1") (pinfunction "1_1") (pintype "passive"))
      (node (ref "SW14") (pin "4") (pintype "passive"))
    )
    (net (code "134") (name "Net-(R15-Pad1)") (class "Default")
      (node (ref "R15") (pin "1") (pinfunction "1_1") (pintype "passive"))
      (node (ref "SW15") (pin "4") (pintype "passive"))
    )
    (net (code "135") (name "Net-(R16-Pad1)") (class "Default")
      (node (ref "R16") (pin "1") (pinfunction "1_1") (pintype "passive"))
      (node (ref "SW16") (pin "4") (pintype "passive"))
    )
    (net (code "136") (name "Net-(R17-Pad1)") (class "Default")
      (node (ref "R17") (pin "1") (pinfunction "1_1") (pintype "passive"))
      (node (ref "SW17") (pin "4") (pintype "passive"))
    )
    (net (code "137") (name "Net-(R18-Pad1)") (class "Default")
      (node (ref "R18") (pin "1") (pinfunction "1_1") (pintype "passive"))
      (node (ref "SW18") (pin "4") (pintype "passive"))
    )
    (net (code "138") (name "Net-(R19-Pad1)") (class "Default")
      (node (ref "R19") (pin "1") (pinfunction "1_1") (pintype "passive"))
      (node (ref "SW19") (pin "4") (pintype "passive"))
    )
    (net (code "139") (name "Net-(R20-Pad1)") (class "Default")
      (node (ref "R20") (pin "1") (pinfunction "1_1") (pintype "passive"))
      (node (ref "SW20") (pin "4") (pintype "passive"))
    )
    (net (code "140") (name "Net-(R21-Pad1)") (class "Default")
      (node (ref "R21") (pin "1") (pinfunction "1_1") (pintype "passive"))
      (node (ref "SW21") (pin "4") (pintype "passive"))
    )
    (net (code "141") (name "Net-(R22-Pad1)") (class "Default")
      (node (ref "R22") (pin "1") (pinfunction "1_1") (pintype "passive"))
      (node (ref "SW22") (pin "4") (pintype "passive"))
    )
    (net (code "142") (name "Net-(R23-Pad1)") (class "Default")
      (node (ref "R23") (pin "1") (pinfunction "1_1") (pintype "passive"))
      (node (ref "SW23") (pin "4") (pintype "passive"))
    )
    (net (code "143") (name "Net-(R24-Pad1)") (class "Default")
      (node (ref "R24") (pin "1") (pinfunction "1_1") (pintype "passive"))
      (node (ref "SW24") (pin "4") (pintype "passive"))
    )
    (net (code "144") (name "Net-(R25-Pad1)") (class "Default")
      (node (ref "R25") (pin "1") (pinfunction "1_1") (pintype "passive"))
      (node (ref "SW25") (pin "4") (pintype "passive"))
    )
    (net (code "145") (name "Net-(R26-Pad1)") (class "Default")
      (node (ref "R26") (pin "1") (pinfunction "1_1") (pintype "passive"))
      (node (ref "SW26") (pin "4") (pintype "passive"))
    )
    (net (code "146") (name "Net-(R27-Pad1)") (class "Default")
      (node (ref "R27") (pin "1") (pinfunction "1_1") (pintype "passive"))
      (node (ref "SW27") (pin "4") (pintype "passive"))
    )
    (net (code "147") (name "Net-(R28-Pad1)") (class "Default")
      (node (ref "R28") (pin "1") (pinfunction "1_1") (pintype "passive"))
      (node (ref "SW28") (pin "4") (pintype "passive"))
    )
    (net (code "148") (name "Net-(R29-Pad1)") (class "Default")
      (node (ref "R29") (pin "1") (pinfunction "1_1") (pintype "passive"))
      (node (ref "SW29") (pin "4") (pintype "passive"))
    )
    (net (code "149") (name "Net-(R30-Pad1)") (class "Default")
      (node (ref "R30") (pin "1") (pinfunction "1_1") (pintype "passive"))
      (node (ref "SW30") (pin "4") (pintype "passive"))
    )
    (net (code "150") (name "Net-(R31-Pad1)") (class "Default")
      (node (ref "R31") (pin "1") (pinfunction "1_1") (pintype "passive"))
      (node (ref "SW31") (pin "4") (pintype "passive"))
    )
    (net (code "151") (name "Net-(R32-Pad1)") (class "Default")
      (node (ref "R32") (pin "1") (pinfunction "1_1") (pintype "passive"))
      (node (ref "SW32") (pin "4") (pintype "passive"))
    )
    (net (code "152") (name "Net-(R33-Pad1)") (class "Default")
      (node (ref "R33") (pin "1") (pinfunction "1_1") (pintype "passive"))
      (node (ref "SW33") (pin "4") (pintype "passive"))
    )
    (net (code "153") (name "Net-(R34-Pad1)") (class "Default")
      (node (ref "R34") (pin "1") (pinfunction "1_1") (pintype "passive"))
      (node (ref "SW34") (pin "4") (pintype "passive"))
    )
    (net (code "154") (name "Net-(R35-Pad1)") (class "Default")
      (node (ref "R35") (pin "1") (pinfunction "1_1") (pintype "passive"))
      (node (ref "SW35") (pin "4") (pintype "passive"))
    )
    (net (code "155") (name "Net-(R36-Pad1)") (class "Default")
      (node (ref "R36") (pin "1") (pinfunction "1_1") (pintype "passive"))
      (node (ref "SW36") (pin "4") (pintype "passive"))
    )
    (net (code "156") (name "Net-(R37-Pad1)") (class "Default")
      (node (ref "R37") (pin "1") (pinfunction "1_1") (pintype "passive"))
      (node (ref "SW37") (pin "4") (pintype "passive"))
    )
    (net (code "157") (name "Net-(R38-Pad1)") (class "Default")
      (node (ref "R38") (pin "1") (pinfunction "1_1") (pintype "passive"))
      (node (ref "SW38") (pin "4") (pintype "passive"))
    )
    (net (code "158") (name "Net-(R39-Pad1)") (class "Default")
      (node (ref "R39") (pin "1") (pinfunction "1_1") (pintype "passive"))
      (node (ref "SW39") (pin "4") (pintype "passive"))
    )
    (net (code "159") (name "Net-(R40-Pad1)") (class "Default")
      (node (ref "R40") (pin "1") (pinfunction "1_1") (pintype "passive"))
      (node (ref "SW40") (pin "4") (pintype "passive"))
    )
    (net (code "160") (name "Net-(R41-Pad1)") (class "Default")
      (node (ref "R41") (pin "1") (pinfunction "1_1") (pintype "passive"))
      (node (ref "SW41") (pin "4") (pintype "passive"))
    )
    (net (code "161") (name "Net-(R42-Pad1)") (class "Default")
      (node (ref "R42") (pin "1") (pinfunction "1_1") (pintype "passive"))
      (node (ref "SW42") (pin "4") (pintype "passive"))
    )
    (net (code "162") (name "Net-(R43-Pad1)") (class "Default")
      (node (ref "R43") (pin "1") (pinfunction "1_1") (pintype "passive"))
      (node (ref "SW43") (pin "4") (pintype "passive"))
    )
    (net (code "163") (name "Net-(R44-Pad1)") (class "Default")
      (node (ref "R44") (pin "1") (pinfunction "1_1") (pintype "passive"))
      (node (ref "SW44") (pin "4") (pintype "passive"))
    )
    (net (code "164") (name "Net-(R45-Pad1)") (class "Default")
      (node (ref "R45") (pin "1") (pinfunction "1_1") (pintype "passive"))
      (node (ref "SW45") (pin "4") (pintype "passive"))
    )
    (net (code "165") (name "Net-(R46-Pad1)") (class "Default")
      (node (ref "R46") (pin "1") (pinfunction "1_1") (pintype "passive"))
      (node (ref "SW46") (pin "4") (pintype "passive"))
    )
    (net (code "166") (name "Net-(R47-Pad1)") (class "Default")
      (node (ref "R47") (pin "1") (pinfunction "1_1") (pintype "passive"))
      (node (ref "SW47") (pin "4") (pintype "passive"))
    )
    (net (code "167") (name "Net-(R48-Pad1)") (class "Default")
      (node (ref "R48") (pin "1") (pinfunction "1_1") (pintype "passive"))
      (node (ref "SW48") (pin "4") (pintype "passive"))
    )
    (net (code "168") (name "Net-(R49-Pad1)") (class "Default")
      (node (ref "R49") (pin "1") (pinfunction "1_1") (pintype "passive"))
      (node (ref "SW49") (pin "4") (pintype "passive"))
    )
    (net (code "169") (name "Net-(R50-Pad1)") (class "Default")
      (node (ref "R50") (pin "1") (pinfunction "1_1") (pintype "passive"))
      (node (ref "SW50") (pin "4") (pintype "passive"))
    )
    (net (code "170") (name "Net-(R51-Pad1)") (class "Default")
      (node (ref "R51") (pin "1") (pinfunction "1_1") (pintype "passive"))
      (node (ref "SW51") (pin "4") (pintype "passive"))
    )
    (net (code "171") (name "Net-(R52-Pad1)") (class "Default")
      (node (ref "R52") (pin "1") (pinfunction "1_1") (pintype "passive"))
      (node (ref "SW52") (pin "4") (pintype "passive"))
    )
    (net (code "172") (name "Net-(R53-Pad1)") (class "Default")
      (node (ref "R53") (pin "1") (pinfunction "1_1") (pintype "passive"))
      (node (ref "SW53") (pin "4") (pintype "passive"))
    )
    (net (code "173") (name "Net-(R54-Pad1)") (class "Default")
      (node (ref "R54") (pin "1") (pinfunction "1_1") (pintype "passive"))
      (node (ref "SW54") (pin "4") (pintype "passive"))
    )
    (net (code "174") (name "Net-(R55-Pad1)") (class "Default")
      (node (ref "R55") (pin "1") (pinfunction "1_1") (pintype "passive"))
      (node (ref "SW55") (pin "4") (pintype "passive"))
    )
    (net (code "175") (name "Net-(R56-Pad1)") (class "Default")
      (node (ref "R56") (pin "1") (pinfunction "1_1") (pintype "passive"))
      (node (ref "SW56") (pin "4") (pintype "passive"))
    )
    (net (code "176") (name "Net-(R57-Pad1)") (class "Default")
      (node (ref "R57") (pin "1") (pinfunction "1_1") (pintype "passive"))
      (node (ref "SW57") (pin "4") (pintype "passive"))
    )
    (net (code "177") (name "Net-(R58-Pad1)") (class "Default")
      (node (ref "R58") (pin "1") (pinfunction "1_1") (pintype "passive"))
      (node (ref "SW58") (pin "4") (pintype "passive"))
    )
    (net (code "178") (name "Net-(R59-Pad1)") (class "Default")
      (node (ref "R59") (pin "1") (pinfunction "1_1") (pintype "passive"))
      (node (ref "SW59") (pin "4") (pintype "passive"))
    )
    (net (code "179") (name "Net-(R60-Pad1)") (class "Default")
      (node (ref "R60") (pin "1") (pinfunction "1_1") (pintype "passive"))
      (node (ref "SW60") (pin "4") (pintype "passive"))
    )
    (net (code "180") (name "Net-(R61-Pad1)") (class "Default")
      (node (ref "R61") (pin "1") (pinfunction "1_1") (pintype "passive"))
      (node (ref "SW61") (pin "4") (pintype "passive"))
    )
    (net (code "181") (name "Net-(R62-Pad1)") (class "Default")
      (node (ref "R62") (pin "1") (pinfunction "1_1") (pintype "passive"))
      (node (ref "SW62") (pin "4") (pintype "passive"))
    )
    (net (code "182") (name "Net-(R63-Pad1)") (class "Default")
      (node (ref "R63") (pin "1") (pinfunction "1_1") (pintype "passive"))
      (node (ref "SW63") (pin "4") (pintype "passive"))
    )
    (net (code "183") (name "Net-(R64-Pad1)") (class "Default")
      (node (ref "R64") (pin "1") (pinfunction "1_1") (pintype "passive"))
      (node (ref "SW64") (pin "4") (pintype "passive"))
    )
    (net (code "184") (name "Net-(R65-Pad1)") (class "Default")
      (node (ref "R65") (pin "1") (pinfunction "1_1") (pintype "passive"))
      (node (ref "SW65") (pin "4") (pintype "passive"))
    )
    (net (code "185") (name "Net-(R66-Pad1)") (class "Default")
      (node (ref "R66") (pin "1") (pinfunction "1_1") (pintype "passive"))
      (node (ref "SW66") (pin "4") (pintype "passive"))
    )
    (net (code "186") (name "Net-(R67-Pad1)") (class "Default")
      (node (ref "R67") (pin "1") (pinfunction "1_1") (pintype "passive"))
      (node (ref "SW67") (pin "4") (pintype "passive"))
    )
    (net (code "187") (name "Net-(R68-Pad1)") (class "Default")
      (node (ref "R68") (pin "1") (pinfunction "1_1") (pintype "passive"))
      (node (ref "SW68") (pin "4") (pintype "passive"))
    )
    (net (code "188") (name "Net-(R69-Pad1)") (class "Default")
      (node (ref "R69") (pin "1") (pinfunction "1_1") (pintype "passive"))
      (node (ref "SW69") (pin "4") (pintype "passive"))
    )
    (net (code "189") (name "Net-(R70-Pad1)") (class "Default")
      (node (ref "R70") (pin "1") (pinfunction "1_1") (pintype "passive"))
      (node (ref "SW70") (pin "4") (pintype "passive"))
    )
    (net (code "190") (name "Net-(R71-Pad1)") (class "Default")
      (node (ref "R71") (pin "1") (pinfunction "1_1") (pintype "passive"))
      (node (ref "SW71") (pin "4") (pintype "passive"))
    )
    (net (code "191") (name "Net-(R72-Pad1)") (class "Default")
      (node (ref "R72") (pin "1") (pinfunction "1_1") (pintype "passive"))
      (node (ref "SW72") (pin "4") (pintype "passive"))
    )
    (net (code "192") (name "Net-(R73-Pad1)") (class "Default")
      (node (ref "R73") (pin "1") (pinfunction "1_1") (pintype "passive"))
      (node (ref "SW73") (pin "4") (pintype "passive"))
    )
    (net (code "193") (name "Net-(R74-Pad1)") (class "Default")
      (node (ref "R74") (pin "1") (pinfunction "1_1") (pintype "passive"))
      (node (ref "SW74") (pin "4") (pintype "passive"))
    )
    (net (code "194") (name "Net-(R75-Pad1)") (class "Default")
      (node (ref "R75") (pin "1") (pinfunction "1_1") (pintype "passive"))
      (node (ref "SW75") (pin "4") (pintype "passive"))
    )
    (net (code "195") (name "Net-(R76-Pad1)") (class "Default")
      (node (ref "R76") (pin "1") (pinfunction "1_1") (pintype "passive"))
      (node (ref "SW76") (pin "4") (pintype "passive"))
    )
    (net (code "196") (name "Net-(R77-Pad1)") (class "Default")
      (node (ref "R77") (pin "1") (pinfunction "1_1") (pintype "passive"))
      (node (ref "SW77") (pin "4") (pintype "passive"))
    )
    (net (code "197") (name "Net-(R78-Pad1)") (class "Default")
      (node (ref "R78") (pin "1") (pinfunction "1_1") (pintype "passive"))
      (node (ref "SW78") (pin "4") (pintype "passive"))
    )
    (net (code "198") (name "Net-(R79-Pad1)") (class "Default")
      (node (ref "R79") (pin "1") (pinfunction "1_1") (pintype "passive"))
      (node (ref "SW79") (pin "4") (pintype "passive"))
    )
    (net (code "199") (name "Net-(R80-Pad1)") (class "Default")
      (node (ref "R80") (pin "1") (pinfunction "1_1") (pintype "passive"))
      (node (ref "SW80") (pin "4") (pintype "passive"))
    )
    (net (code "200") (name "Net-(R81-Pad1)") (class "Default")
      (node (ref "R81") (pin "1") (pinfunction "1_1") (pintype "passive"))
      (node (ref "SW81") (pin "4") (pintype "passive"))
    )
    (net (code "201") (name "Net-(R82-Pad1)") (class "Default")
      (node (ref "R82") (pin "1") (pinfunction "1_1") (pintype "passive"))
      (node (ref "SW82") (pin "4") (pintype "passive"))
    )
    (net (code "202") (name "Net-(R83-Pad1)") (class "Default")
      (node (ref "R83") (pin "1") (pinfunction "1_1") (pintype "passive"))
      (node (ref "SW83") (pin "4") (pintype "passive"))
    )
    (net (code "203") (name "Net-(R84-Pad1)") (class "Default")
      (node (ref "R84") (pin "1") (pinfunction "1_1") (pintype "passive"))
      (node (ref "SW84") (pin "4") (pintype "passive"))
    )
    (net (code "204") (name "Net-(R85-Pad1)") (class "Default")
      (node (ref "R85") (pin "1") (pinfunction "1_1") (pintype "passive"))
      (node (ref "SW85") (pin "4") (pintype "passive"))
    )
    (net (code "205") (name "Net-(R86-Pad1)") (class "Default")
      (node (ref "R86") (pin "1") (pinfunction "1_1") (pintype "passive"))
      (node (ref "SW86") (pin "4") (pintype "passive"))
    )
    (net (code "206") (name "Net-(R87-Pad1)") (class "Default")
      (node (ref "R87") (pin "1") (pinfunction "1_1") (pintype "passive"))
      (node (ref "SW87") (pin "4") (pintype "passive"))
    )
    (net (code "207") (name "Net-(R88-Pad1)") (class "Default")
      (node (ref "R88") (pin "1") (pinfunction "1_1") (pintype "passive"))
      (node (ref "SW88") (pin "4") (pintype "passive"))
    )
    (net (code "208") (name "Net-(R89-Pad1)") (class "Default")
      (node (ref "R89") (pin "1") (pinfunction "1_1") (pintype "passive"))
      (node (ref "SW89") (pin "4") (pintype "passive"))
    )
    (net (code "209") (name "Net-(R90-Pad1)") (class "Default")
      (node (ref "R90") (pin "1") (pinfunction "1_1") (pintype "passive"))
      (node (ref "SW90") (pin "4") (pintype "passive"))
    )
    (net (code "210") (name "Net-(R91-Pad1)") (class "Default")
      (node (ref "R91") (pin "1") (pinfunction "1_1") (pintype "passive"))
      (node (ref "SW91") (pin "4") (pintype "passive"))
    )
    (net (code "211") (name "Net-(R92-Pad1)") (class "Default")
      (node (ref "R92") (pin "1") (pinfunction "1_1") (pintype "passive"))
      (node (ref "SW92") (pin "4") (pintype "passive"))
    )
    (net (code "212") (name "Net-(R93-Pad1)") (class "Default")
      (node (ref "R93") (pin "1") (pinfunction "1_1") (pintype "passive"))
      (node (ref "SW93") (pin "4") (pintype "passive"))
    )
    (net (code "213") (name "Net-(R94-Pad1)") (class "Default")
      (node (ref "R94") (pin "1") (pinfunction "1_1") (pintype "passive"))
      (node (ref "SW94") (pin "4") (pintype "passive"))
    )
    (net (code "214") (name "Net-(R95-Pad1)") (class "Default")
      (node (ref "R95") (pin "1") (pinfunction "1_1") (pintype "passive"))
      (node (ref "SW95") (pin "4") (pintype "passive"))
    )
    (net (code "215") (name "Net-(R96-Pad1)") (class "Default")
      (node (ref "R96") (pin "1") (pinfunction "1_1") (pintype "passive"))
      (node (ref "SW96") (pin "4") (pintype "passive"))
    )
    (net (code "216") (name "VCC") (class "Default")
      (node (ref "SW1") (pin "3") (pintype "passive"))
      (node (ref "SW10") (pin "3") (pintype "passive"))
      (node (ref "SW11") (pin "3") (pintype "passive"))
      (node (ref "SW12") (pin "3") (pintype "passive"))
      (node (ref "SW13") (pin "3") (pintype "passive"))
      (node (ref "SW14") (pin "3") (pintype "passive"))
      (node (ref "SW15") (pin "3") (pintype "passive"))
      (node (ref "SW16") (pin "3") (pintype "passive"))
      (node (ref "SW17") (pin "3") (pintype "passive"))
      (node (ref "SW18") (pin "3") (pintype "passive"))
      (node (ref "SW19") (pin "3") (pintype "passive"))
      (node (ref "SW2") (pin "3") (pintype "passive"))
      (node (ref "SW20") (pin "3") (pintype "passive"))
      (node (ref "SW21") (pin "3") (pintype "passive"))
      (node (ref "SW22") (pin "3") (pintype "passive"))
      (node (ref "SW23") (pin "3") (pintype "passive"))
      (node (ref "SW24") (pin "3") (pintype "passive"))
      (node (ref "SW25") (pin "3") (pintype "passive"))
      (node (ref "SW26") (pin "3") (pintype "passive"))
      (node (ref "SW27") (pin "3") (pintype "passive"))
      (node (ref "SW28") (pin "3") (pintype "passive"))
      (node (ref "SW29") (pin "3") (pintype "passive"))
      (node (ref "SW3") (pin "3") (pintype "passive"))
      (node (ref "SW30") (pin "3") (pintype "passive"))
      (node (ref "SW31") (pin "3") (pintype "passive"))
      (node (ref "SW32") (pin "3") (pintype "passive"))
      (node (ref "SW33") (pin "3") (pintype "passive"))
      (node (ref "SW34") (pin "3") (pintype "passive"))
      (node (ref "SW35") (pin "3") (pintype "passive"))
      (node (ref "SW36") (pin "3") (pintype "passive"))
      (node (ref "SW37") (pin "3") (pintype "passive"))
      (node (ref "SW38") (pin "3") (pintype "passive"))
      (node (ref "SW39") (pin "3") (pintype "passive"))
      (node (ref "SW4") (pin "3") (pintype "passive"))
      (node (ref "SW40") (pin "3") (pintype "passive"))
      (node (ref "SW41") (pin "3") (pintype "passive"))
      (node (ref "SW42") (pin "3") (pintype "passive"))
      (node (ref "SW43") (pin "3") (pintype "passive"))
      (node (ref "SW44") (pin "3") (pintype "passive"))
      (node (ref "SW45") (pin "3") (pintype "passive"))
      (node (ref "SW46") (pin "3") (pintype "passive"))
      (node (ref "SW47") (pin "3") (pintype "passive"))
      (node (ref "SW48") (pin "3") (pintype "passive"))
      (node (ref "SW49") (pin "3") (pintype "passive"))
      (node (ref "SW5") (pin "3") (pintype "passive"))
      (node (ref "SW50") (pin "3") (pintype "passive"))
      (node (ref "SW51") (pin "3") (pintype "passive"))
      (node (ref "SW52") (pin "3") (pintype "passive"))
      (node (ref "SW53") (pin "3") (pintype "passive"))
      (node (ref "SW54") (pin "3") (pintype "passive"))
      (node (ref "SW55") (pin "3") (pintype "passive"))
      (node (ref "SW56") (pin "3") (pintype "passive"))
      (node (ref "SW57") (pin "3") (pintype "passive"))
      (node (ref "SW58") (pin "3") (pintype "passive"))
      (node (ref "SW59") (pin "3") (pintype "passive"))
      (node (ref "SW6") (pin "3") (pintype "passive"))
      (node (ref "SW60") (pin "3") (pintype "passive"))
      (node (ref "SW61") (pin "3") (pintype "passive"))
      (node (ref "SW62") (pin "3") (pintype "passive"))
      (node (ref "SW63") (pin "3") (pintype "passive"))
      (node (ref "SW64") (pin "3") (pintype "passive"))
      (node (ref "SW65") (pin "3") (pintype "passive"))
      (node (ref "SW66") (pin "3") (pintype "passive"))
      (node (ref "SW67") (pin "3") (pintype "passive"))
      (node (ref "SW68") (pin "3") (pintype "passive"))
      (node (ref "SW69") (pin "3") (pintype "passive"))
      (node (ref "SW7") (pin "3") (pintype "passive"))
      (node (ref "SW70") (pin "3") (pintype "passive"))
      (node (ref "SW71") (pin "3") (pintype "passive"))
      (node (ref "SW72") (pin "3") (pintype "passive"))
      (node (ref "SW73") (pin "3") (pintype "passive"))
      (node (ref "SW74") (pin "3") (pintype "passive"))
      (node (ref "SW75") (pin "3") (pintype "passive"))
      (node (ref "SW76") (pin "3") (pintype "passive"))
      (node (ref "SW77") (pin "3") (pintype "passive"))
      (node (ref "SW78") (pin "3") (pintype "passive"))
      (node (ref "SW79") (pin "3") (pintype "passive"))
      (node (ref "SW8") (pin "3") (pintype "passive"))
      (node (ref "SW80") (pin "3") (pintype "passive"))
      (node (ref "SW81") (pin "3") (pintype "passive"))
      (node (ref "SW82") (pin "3") (pintype "passive"))
      (node (ref "SW83") (pin "3") (pintype "passive"))
      (node (ref "SW84") (pin "3") (pintype "passive"))
      (node (ref "SW85") (pin "3") (pintype "passive"))
      (node (ref "SW86") (pin "3") (pintype "passive"))
      (node (ref "SW87") (pin "3") (pintype "passive"))
      (node (ref "SW88") (pin "3") (pintype "passive"))
      (node (ref "SW89") (pin "3") (pintype "passive"))
      (node (ref "SW90") (pin "3") (pintype "passive"))
      (node (ref "SW91") (pin "3") (pintype "passive"))
      (node (ref "SW92") (pin "3") (pintype "passive"))
      (node (ref "SW93") (pin "3") (pintype "passive"))
      (node (ref "SW94") (pin "3") (pintype "passive"))
      (node (ref "SW95") (pin "3") (pintype "passive"))
      (node (ref "SW96") (pin "3") (pintype "passive"))
    )
    (net (code "217") (name "unconnected-(SW1-Pad5)") (class "Default")
      (node (ref "SW1") (pin "5") (pintype "passive"))
    )
    (net (code "218") (name "unconnected-(SW1-Pad6)") (class "Default")
      (node (ref "SW1") (pin "6") (pintype "passive"))
    )
    (net (code "219") (name "unconnected-(SW2-Pad5)") (class "Default")
      (node (ref "SW2") (pin "5") (pintype "passive"))
    )
    (net (code "220") (name "unconnected-(SW2-Pad6)") (class "Default")
      (node (ref "SW2") (pin "6") (pintype "passive"))
    )
    (net (code "221") (name "unconnected-(SW3-Pad5)") (class "Default")
      (node (ref "SW3") (pin "5") (pintype "passive"))
    )
    (net (code "222") (name "unconnected-(SW3-Pad6)") (class "Default")
      (node (ref "SW3") (pin "6") (pintype "passive"))
    )
    (net (code "223") (name "unconnected-(SW4-Pad5)") (class "Default")
      (node (ref "SW4") (pin "5") (pintype "passive"))
    )
    (net (code "224") (name "unconnected-(SW4-Pad6)") (class "Default")
      (node (ref "SW4") (pin "6") (pintype "passive"))
    )
    (net (code "225") (name "unconnected-(SW5-Pad5)") (class "Default")
      (node (ref "SW5") (pin "5") (pintype "passive"))
    )
    (net (code "226") (name "unconnected-(SW5-Pad6)") (class "Default")
      (node (ref "SW5") (pin "6") (pintype "passive"))
    )
    (net (code "227") (name "unconnected-(SW6-Pad5)") (class "Default")
      (node (ref "SW6") (pin "5") (pintype "passive"))
    )
    (net (code "228") (name "unconnected-(SW6-Pad6)") (class "Default")
      (node (ref "SW6") (pin "6") (pintype "passive"))
    )
    (net (code "229") (name "unconnected-(SW7-Pad5)") (class "Default")
      (node (ref "SW7") (pin "5") (pintype "passive"))
    )
    (net (code "230") (name "unconnected-(SW7-Pad6)") (class "Default")
      (node (ref "SW7") (pin "6") (pintype "passive"))
    )
    (net (code "231") (name "unconnected-(SW8-Pad5)") (class "Default")
      (node (ref "SW8") (pin "5") (pintype "passive"))
    )
    (net (code "232") (name "unconnected-(SW8-Pad6)") (class "Default")
      (node (ref "SW8") (pin "6") (pintype "passive"))
    )
    (net (code "233") (name "unconnected-(SW9-Pad5)") (class "Default")
      (node (ref "SW9") (pin "5") (pintype "passive"))
    )
    (net (code "234") (name "unconnected-(SW9-Pad6)") (class "Default")
      (node (ref "SW9") (pin "6") (pintype "passive"))
    )
    (net (code "235") (name "unconnected-(SW10-Pad5)") (class "Default")
      (node (ref "SW10") (pin "5") (pintype "passive"))
    )
    (net (code "236") (name "unconnected-(SW10-Pad6)") (class "Default")
      (node (ref "SW10") (pin "6") (pintype "passive"))
    )
    (net (code "237") (name "unconnected-(SW11-Pad5)") (class "Default")
      (node (ref "SW11") (pin "5") (pintype "passive"))
    )
    (net (code "238") (name "unconnected-(SW11-Pad6)") (class "Default")
      (node (ref "SW11") (pin "6") (pintype "passive"))
    )
    (net (code "239") (name "unconnected-(SW12-Pad5)") (class "Default")
      (node (ref "SW12") (pin "5") (pintype "passive"))
    )
    (net (code "240") (name "unconnected-(SW12-Pad6)") (class "Default")
      (node (ref "SW12") (pin "6") (pintype "passive"))
    )
    (net (code "241") (name "unconnected-(SW13-Pad5)") (class "Default")
      (node (ref "SW13") (pin "5") (pintype "passive"))
    )
    (net (code "242") (name "unconnected-(SW13-Pad6)") (class "Default")
      (node (ref "SW13") (pin "6") (pintype "passive"))
    )
    (net (code "243") (name "unconnected-(SW14-Pad5)") (class "Default")
      (node (ref "SW14") (pin "5") (pintype "passive"))
    )
    (net (code "244") (name "unconnected-(SW14-Pad6)") (class "Default")
      (node (ref "SW14") (pin "6") (pintype "passive"))
    )
    (net (code "245") (name "unconnected-(SW15-Pad5)") (class "Default")
      (node (ref "SW15") (pin "5") (pintype "passive"))
    )
    (net (code "246") (name "unconnected-(SW15-Pad6)") (class "Default")
      (node (ref "SW15") (pin "6") (pintype "passive"))
    )
    (net (code "247") (name "unconnected-(SW16-Pad5)") (class "Default")
      (node (ref "SW16") (pin "5") (pintype "passive"))
    )
    (net (code "248") (name "unconnected-(SW16-Pad6)") (class "Default")
      (node (ref "SW16") (pin "6") (pintype "passive"))
    )
    (net (code "249") (name "unconnected-(SW17-Pad5)") (class "Default")
      (node (ref "SW17") (pin "5") (pintype "passive"))
    )
    (net (code "250") (name "unconnected-(SW17-Pad6)") (class "Default")
      (node (ref "SW17") (pin "6") (pintype "passive"))
    )
    (net (code "251") (name "unconnected-(SW18-Pad5)") (class "Default")
      (node (ref "SW18") (pin "5") (pintype "passive"))
    )
    (net (code "252") (name "unconnected-(SW18-Pad6)") (class "Default")
      (node (ref "SW18") (pin "6") (pintype "passive"))
    )
    (net (code "253") (name "unconnected-(SW19-Pad5)") (class "Default")
      (node (ref "SW19") (pin "5") (pintype "passive"))
    )
    (net (code "254") (name "unconnected-(SW19-Pad6)") (class "Default")
      (node (ref "SW19") (pin "6") (pintype "passive"))
    )
    (net (code "255") (name "unconnected-(SW20-Pad5)") (class "Default")
      (node (ref "SW20") (pin "5") (pintype "passive"))
    )
    (net (code "256") (name "unconnected-(SW20-Pad6)") (class "Default")
      (node (ref "SW20") (pin "6") (pintype "passive"))
    )
    (net (code "257") (name "unconnected-(SW21-Pad5)") (class "Default")
      (node (ref "SW21") (pin "5") (pintype "passive"))
    )
    (net (code "258") (name "unconnected-(SW21-Pad6)") (class "Default")
      (node (ref "SW21") (pin "6") (pintype "passive"))
    )
    (net (code "259") (name "unconnected-(SW22-Pad5)") (class "Default")
      (node (ref "SW22") (pin "5") (pintype "passive"))
    )
    (net (code "260") (name "unconnected-(SW22-Pad6)") (class "Default")
      (node (ref "SW22") (pin "6") (pintype "passive"))
    )
    (net (code "261") (name "unconnected-(SW23-Pad5)") (class "Default")
      (node (ref "SW23") (pin "5") (pintype "passive"))
    )
    (net (code "262") (name "unconnected-(SW23-Pad6)") (class "Default")
      (node (ref "SW23") (pin "6") (pintype "passive"))
    )
    (net (code "263") (name "unconnected-(SW24-Pad5)") (class "Default")
      (node (ref "SW24") (pin "5") (pintype "passive"))
    )
    (net (code "264") (name "unconnected-(SW24-Pad6)") (class "Default")
      (node (ref "SW24") (pin "6") (pintype "passive"))
    )
    (net (code "265") (name "unconnected-(SW25-Pad5)") (class "Default")
      (node (ref "SW25") (pin "5") (pintype "passive"))
    )
    (net (code "266") (name "unconnected-(SW25-Pad6)") (class "Default")
      (node (ref "SW25") (pin "6") (pintype "passive"))
    )
    (net (code "267") (name "unconnected-(SW26-Pad5)") (class "Default")
      (node (ref "SW26") (pin "5") (pintype "passive"))
    )
    (net (code "268") (name "unconnected-(SW26-Pad6)") (class "Default")
      (node (ref "SW26") (pin "6") (pintype "passive"))
    )
    (net (code "269") (name "unconnected-(SW27-Pad5)") (class "Default")
      (node (ref "SW27") (pin "5") (pintype "passive"))
    )
    (net (code "270") (name "unconnected-(SW27-Pad6)") (class "Default")
      (node (ref "SW27") (pin "6") (pintype "passive"))
    )
    (net (code "271") (name "unconnected-(SW28-Pad5)") (class "Default")
      (node (ref "SW28") (pin "5") (pintype "passive"))
    )
    (net (code "272") (name "unconnected-(SW28-Pad6)") (class "Default")
      (node (ref "SW28") (pin "6") (pintype "passive"))
    )
    (net (code "273") (name "unconnected-(SW29-Pad5)") (class "Default")
      (node (ref "SW29") (pin "5") (pintype "passive"))
    )
    (net (code "274") (name "unconnected-(SW29-Pad6)") (class "Default")
      (node (ref "SW29") (pin "6") (pintype "passive"))
    )
    (net (code "275") (name "unconnected-(SW30-Pad5)") (class "Default")
      (node (ref "SW30") (pin "5") (pintype "passive"))
    )
    (net (code "276") (name "unconnected-(SW30-Pad6)") (class "Default")
      (node (ref "SW30") (pin "6") (pintype "passive"))
    )
    (net (code "277") (name "unconnected-(SW31-Pad5)") (class "Default")
      (node (ref "SW31") (pin "5") (pintype "passive"))
    )
    (net (code "278") (name "unconnected-(SW31-Pad6)") (class "Default")
      (node (ref "SW31") (pin "6") (pintype "passive"))
    )
    (net (code "279") (name "unconnected-(SW32-Pad5)") (class "Default")
      (node (ref "SW32") (pin "5") (pintype "passive"))
    )
    (net (code "280") (name "unconnected-(SW32-Pad6)") (class "Default")
      (node (ref "SW32") (pin "6") (pintype "passive"))
    )
    (net (code "281") (name "unconnected-(SW33-Pad5)") (class "Default")
      (node (ref "SW33") (pin "5") (pintype "passive"))
    )
    (net (code "282") (name "unconnected-(SW33-Pad6)") (class "Default")
      (node (ref "SW33") (pin "6") (pintype "passive"))
    )
    (net (code "283") (name "unconnected-(SW34-Pad5)") (class "Default")
      (node (ref "SW34") (pin "5") (pintype "passive"))
    )
    (net (code "284") (name "unconnected-(SW34-Pad6)") (class "Default")
      (node (ref "SW34") (pin "6") (pintype "passive"))
    )
    (net (code "285") (name "unconnected-(SW35-Pad5)") (class "Default")
      (node (ref "SW35") (pin "5") (pintype "passive"))
    )
    (net (code "286") (name "unconnected-(SW35-Pad6)") (class "Default")
      (node (ref "SW35") (pin "6") (pintype "passive"))
    )
    (net (code "287") (name "unconnected-(SW36-Pad5)") (class "Default")
      (node (ref "SW36") (pin "5") (pintype "passive"))
    )
    (net (code "288") (name "unconnected-(SW36-Pad6)") (class "Default")
      (node (ref "SW36") (pin "6") (pintype "passive"))
    )
    (net (code "289") (name "unconnected-(SW37-Pad5)") (class "Default")
      (node (ref "SW37") (pin "5") (pintype "passive"))
    )
    (net (code "290") (name "unconnected-(SW37-Pad6)") (class "Default")
      (node (ref "SW37") (pin "6") (pintype "passive"))
    )
    (net (code "291") (name "unconnected-(SW38-Pad5)") (class "Default")
      (node (ref "SW38") (pin "5") (pintype "passive"))
    )
    (net (code "292") (name "unconnected-(SW38-Pad6)") (class "Default")
      (node (ref "SW38") (pin "6") (pintype "passive"))
    )
    (net (code "293") (name "unconnected-(SW39-Pad5)") (class "Default")
      (node (ref "SW39") (pin "5") (pintype "passive"))
    )
    (net (code "294") (name "unconnected-(SW39-Pad6)") (class "Default")
      (node (ref "SW39") (pin "6") (pintype "passive"))
    )
    (net (code "295") (name "unconnected-(SW40-Pad5)") (class "Default")
      (node (ref "SW40") (pin "5") (pintype "passive"))
    )
    (net (code "296") (name "unconnected-(SW40-Pad6)") (class "Default")
      (node (ref "SW40") (pin "6") (pintype "passive"))
    )
    (net (code "297") (name "unconnected-(SW41-Pad5)") (class "Default")
      (node (ref "SW41") (pin "5") (pintype "passive"))
    )
    (net (code "298") (name "unconnected-(SW41-Pad6)") (class "Default")
      (node (ref "SW41") (pin "6") (pintype "passive"))
    )
    (net (code "299") (name "unconnected-(SW42-Pad5)") (class "Default")
      (node (ref "SW42") (pin "5") (pintype "passive"))
    )
    (net (code "300") (name "unconnected-(SW42-Pad6)") (class "Default")
      (node (ref "SW42") (pin "6") (pintype "passive"))
    )
    (net (code "301") (name "unconnected-(SW43-Pad5)") (class "Default")
      (node (ref "SW43") (pin "5") (pintype "passive"))
    )
    (net (code "302") (name "unconnected-(SW43-Pad6)") (class "Default")
      (node (ref "SW43") (pin "6") (pintype "passive"))
    )
    (net (code "303") (name "unconnected-(SW44-Pad5)") (class "Default")
      (node (ref "SW44") (pin "5") (pintype "passive"))
    )
    (net (code "304") (name "unconnected-(SW44-Pad6)") (class "Default")
      (node (ref "SW44") (pin "6") (pintype "passive"))
    )
    (net (code "305") (name "unconnected-(SW45-Pad5)") (class "Default")
      (node (ref "SW45") (pin "5") (pintype "passive"))
    )
    (net (code "306") (name "unconnected-(SW45-Pad6)") (class "Default")
      (node (ref "SW45") (pin "6") (pintype "passive"))
    )
    (net (code "307") (name "unconnected-(SW46-Pad5)") (class "Default")
      (node (ref "SW46") (pin "5") (pintype "passive"))
    )
    (net (code "308") (name "unconnected-(SW46-Pad6)") (class "Default")
      (node (ref "SW46") (pin "6") (pintype "passive"))
    )
    (net (code "309") (name "unconnected-(SW47-Pad5)") (class "Default")
      (node (ref "SW47") (pin "5") (pintype "passive"))
    )
    (net (code "310") (name "unconnected-(SW47-Pad6)") (class "Default")
      (node (ref "SW47") (pin "6") (pintype "passive"))
    )
    (net (code "311") (name "unconnected-(SW48-Pad5)") (class "Default")
      (node (ref "SW48") (pin "5") (pintype "passive"))
    )
    (net (code "312") (name "unconnected-(SW48-Pad6)") (class "Default")
      (node (ref "SW48") (pin "6") (pintype "passive"))
    )
    (net (code "313") (name "unconnected-(SW49-Pad5)") (class "Default")
      (node (ref "SW49") (pin "5") (pintype "passive"))
    )
    (net (code "314") (name "unconnected-(SW49-Pad6)") (class "Default")
      (node (ref "SW49") (pin "6") (pintype "passive"))
    )
    (net (code "315") (name "unconnected-(SW50-Pad5)") (class "Default")
      (node (ref "SW50") (pin "5") (pintype "passive"))
    )
    (net (code "316") (name "unconnected-(SW50-Pad6)") (class "Default")
      (node (ref "SW50") (pin "6") (pintype "passive"))
    )
    (net (code "317") (name "unconnected-(SW51-Pad5)") (class "Default")
      (node (ref "SW51") (pin "5") (pintype "passive"))
    )
    (net (code "318") (name "unconnected-(SW51-Pad6)") (class "Default")
      (node (ref "SW51") (pin "6") (pintype "passive"))
    )
    (net (code "319") (name "unconnected-(SW52-Pad5)") (class "Default")
      (node (ref "SW52") (pin "5") (pintype "passive"))
    )
    (net (code "320") (name "unconnected-(SW52-Pad6)") (class "Default")
      (node (ref "SW52") (pin "6") (pintype "passive"))
    )
    (net (code "321") (name "unconnected-(SW53-Pad5)") (class "Default")
      (node (ref "SW53") (pin "5") (pintype "passive"))
    )
    (net (code "322") (name "unconnected-(SW53-Pad6)") (class "Default")
      (node (ref "SW53") (pin "6") (pintype "passive"))
    )
    (net (code "323") (name "unconnected-(SW54-Pad5)") (class "Default")
      (node (ref "SW54") (pin "5") (pintype "passive"))
    )
    (net (code "324") (name "unconnected-(SW54-Pad6)") (class "Default")
      (node (ref "SW54") (pin "6") (pintype "passive"))
    )
    (net (code "325") (name "unconnected-(SW55-Pad5)") (class "Default")
      (node (ref "SW55") (pin "5") (pintype "passive"))
    )
    (net (code "326") (name "unconnected-(SW55-Pad6)") (class "Default")
      (node (ref "SW55") (pin "6") (pintype "passive"))
    )
    (net (code "327") (name "unconnected-(SW56-Pad5)") (class "Default")
      (node (ref "SW56") (pin "5") (pintype "passive"))
    )
    (net (code "328") (name "unconnected-(SW56-Pad6)") (class "Default")
      (node (ref "SW56") (pin "6") (pintype "passive"))
    )
    (net (code "329") (name "unconnected-(SW57-Pad5)") (class "Default")
      (node (ref "SW57") (pin "5") (pintype "passive"))
    )
    (net (code "330") (name "unconnected-(SW57-Pad6)") (class "Default")
      (node (ref "SW57") (pin "6") (pintype "passive"))
    )
    (net (code "331") (name "unconnected-(SW58-Pad5)") (class "Default")
      (node (ref "SW58") (pin "5") (pintype "passive"))
    )
    (net (code "332") (name "unconnected-(SW58-Pad6)") (class "Default")
      (node (ref "SW58") (pin "6") (pintype "passive"))
    )
    (net (code "333") (name "unconnected-(SW59-Pad5)") (class "Default")
      (node (ref "SW59") (pin "5") (pintype "passive"))
    )
    (net (code "334") (name "unconnected-(SW59-Pad6)") (class "Default")
      (node (ref "SW59") (pin "6") (pintype "passive"))
    )
    (net (code "335") (name "unconnected-(SW60-Pad5)") (class "Default")
      (node (ref "SW60") (pin "5") (pintype "passive"))
    )
    (net (code "336") (name "unconnected-(SW60-Pad6)") (class "Default")
      (node (ref "SW60") (pin "6") (pintype "passive"))
    )
    (net (code "337") (name "unconnected-(SW61-Pad5)") (class "Default")
      (node (ref "SW61") (pin "5") (pintype "passive"))
    )
    (net (code "338") (name "unconnected-(SW61-Pad6)") (class "Default")
      (node (ref "SW61") (pin "6") (pintype "passive"))
    )
    (net (code "339") (name "unconnected-(SW62-Pad5)") (class "Default")
      (node (ref "SW62") (pin "5") (pintype "passive"))
    )
    (net (code "340") (name "unconnected-(SW62-Pad6)") (class "Default")
      (node (ref "SW62") (pin "6") (pintype "passive"))
    )
    (net (code "341") (name "unconnected-(SW63-Pad5)") (class "Default")
      (node (ref "SW63") (pin "5") (pintype "passive"))
    )
    (net (code "342") (name "unconnected-(SW63-Pad6)") (class "Default")
      (node (ref "SW63") (pin "6") (pintype "passive"))
    )
    (net (code "343") (name "unconnected-(SW64-Pad5)") (class "Default")
      (node (ref "SW64") (pin "5") (pintype "passive"))
    )
    (net (code "344") (name "unconnected-(SW64-Pad6)") (class "Default")
      (node (ref "SW64") (pin "6") (pintype "passive"))
    )
    (net (code "345") (name "unconnected-(SW65-Pad5)") (class "Default")
      (node (ref "SW65") (pin "5") (pintype "passive"))
    )
    (net (code "346") (name "unconnected-(SW65-Pad6)") (class "Default")
      (node (ref "SW65") (pin "6") (pintype "passive"))
    )
    (net (code "347") (name "unconnected-(SW66-Pad5)") (class "Default")
      (node (ref "SW66") (pin "5") (pintype "passive"))
    )
    (net (code "348") (name "unconnected-(SW66-Pad6)") (class "Default")
      (node (ref "SW66") (pin "6") (pintype "passive"))
    )
    (net (code "349") (name "unconnected-(SW67-Pad5)") (class "Default")
      (node (ref "SW67") (pin "5") (pintype "passive"))
    )
    (net (code "350") (name "unconnected-(SW67-Pad6)") (class "Default")
      (node (ref "SW67") (pin "6") (pintype "passive"))
    )
    (net (code "351") (name "unconnected-(SW68-Pad5)") (class "Default")
      (node (ref "SW68") (pin "5") (pintype "passive"))
    )
    (net (code "352") (name "unconnected-(SW68-Pad6)") (class "Default")
      (node (ref "SW68") (pin "6") (pintype "passive"))
    )
    (net (code "353") (name "unconnected-(SW69-Pad5)") (class "Default")
      (node (ref "SW69") (pin "5") (pintype "passive"))
    )
    (net (code "354") (name "unconnected-(SW69-Pad6)") (class "Default")
      (node (ref "SW69") (pin "6") (pintype "passive"))
    )
    (net (code "355") (name "unconnected-(SW70-Pad5)") (class "Default")
      (node (ref "SW70") (pin "5") (pintype "passive"))
    )
    (net (code "356") (name "unconnected-(SW70-Pad6)") (class "Default")
      (node (ref "SW70") (pin "6") (pintype "passive"))
    )
    (net (code "357") (name "unconnected-(SW71-Pad5)") (class "Default")
      (node (ref "SW71") (pin "5") (pintype "passive"))
    )
    (net (code "358") (name "unconnected-(SW71-Pad6)") (class "Default")
      (node (ref "SW71") (pin "6") (pintype "passive"))
    )
    (net (code "359") (name "unconnected-(SW72-Pad5)") (class "Default")
      (node (ref "SW72") (pin "5") (pintype "passive"))
    )
    (net (code "360") (name "unconnected-(SW72-Pad6)") (class "Default")
      (node (ref "SW72") (pin "6") (pintype "passive"))
    )
    (net (code "361") (name "unconnected-(SW73-Pad5)") (class "Default")
      (node (ref "SW73") (pin "5") (pintype "passive"))
    )
    (net (code "362") (name "unconnected-(SW73-Pad6)") (class "Default")
      (node (ref "SW73") (pin "6") (pintype "passive"))
    )
    (net (code "363") (name "unconnected-(SW74-Pad5)") (class "Default")
      (node (ref "SW74") (pin "5") (pintype "passive"))
    )
    (net (code "364") (name "unconnected-(SW74-Pad6)") (class "Default")
      (node (ref "SW74") (pin "6") (pintype "passive"))
    )
    (net (code "365") (name "unconnected-(SW75-Pad5)") (class "Default")
      (node (ref "SW75") (pin "5") (pintype "passive"))
    )
    (net (code "366") (name "unconnected-(SW75-Pad6)") (class "Default")
      (node (ref "SW75") (pin "6") (pintype "passive"))
    )
    (net (code "367") (name "unconnected-(SW76-Pad5)") (class "Default")
      (node (ref "SW76") (pin "5") (pintype "passive"))
    )
    (net (code "368") (name "unconnected-(SW76-Pad6)") (class "Default")
      (node (ref "SW76") (pin "6") (pintype "passive"))
    )
    (net (code "369") (name "unconnected-(SW77-Pad5)") (class "Default")
      (node (ref "SW77") (pin "5") (pintype "passive"))
    )
    (net (code "370") (name "unconnected-(SW77-Pad6)") (class "Default")
      (node (ref "SW77") (pin "6") (pintype "passive"))
    )
    (net (code "371") (name "unconnected-(SW78-Pad5)") (class "Default")
      (node (ref "SW78") (pin "5") (pintype "passive"))
    )
    (net (code "372") (name "unconnected-(SW78-Pad6)") (class "Default")
      (node (ref "SW78") (pin "6") (pintype "passive"))
    )
    (net (code "373") (name "unconnected-(SW79-Pad5)") (class "Default")
      (node (ref "SW79") (pin "5") (pintype "passive"))
    )
    (net (code "374") (name "unconnected-(SW79-Pad6)") (class "Default")
      (node (ref "SW79") (pin "6") (pintype "passive"))
    )
    (net (code "375") (name "unconnected-(SW80-Pad5)") (class "Default")
      (node (ref "SW80") (pin "5") (pintype "passive"))
    )
    (net (code "376") (name "unconnected-(SW80-Pad6)") (class "Default")
      (node (ref "SW80") (pin "6") (pintype "passive"))
    )
    (net (code "377") (name "unconnected-(SW81-Pad5)") (class "Default")
      (node (ref "SW81") (pin "5") (pintype "passive"))
    )
    (net (code "378") (name "unconnected-(SW81-Pad6)") (class "Default")
      (node (ref "SW81") (pin "6") (pintype "passive"))
    )
    (net (code "379") (name "unconnected-(SW82-Pad5)") (class "Default")
      (node (ref "SW82") (pin "5") (pintype "passive"))
    )
    (net (code "380") (name "unconnected-(SW82-Pad6)") (class "Default")
      (node (ref "SW82") (pin "6") (pintype "passive"))
    )
    (net (code "381") (name "unconnected-(SW83-Pad5)") (class "Default")
      (node (ref "SW83") (pin "5") (pintype "passive"))
    )
    (net (code "382") (name "unconnected-(SW83-Pad6)") (class "Default")
      (node (ref "SW83") (pin "6") (pintype "passive"))
    )
    (net (code "383") (name "unconnected-(SW84-Pad5)") (class "Default")
      (node (ref "SW84") (pin "5") (pintype "passive"))
    )
    (net (code "384") (name "unconnected-(SW84-Pad6)") (class "Default")
      (node (ref "SW84") (pin "6") (pintype "passive"))
    )
    (net (code "385") (name "unconnected-(SW85-Pad5)") (class "Default")
      (node (ref "SW85") (pin "5") (pintype "passive"))
    )
    (net (code "386") (name "unconnected-(SW85-Pad6)") (class "Default")
      (node (ref "SW85") (pin "6") (pintype "passive"))
    )
    (net (code "387") (name "unconnected-(SW86-Pad5)") (class "Default")
      (node (ref "SW86") (pin "5") (pintype "passive"))
    )
    (net (code "388") (name "unconnected-(SW86-Pad6)") (class "Default")
      (node (ref "SW86") (pin "6") (pintype "passive"))
    )
    (net (code "389") (name "unconnected-(SW87-Pad5)") (class "Default")
      (node (ref "SW87") (pin "5") (pintype "passive"))
    )
    (net (code "390") (name "unconnected-(SW87-Pad6)") (class "Default")
      (node (ref "SW87") (pin "6") (pintype "passive"))
    )
    (net (code "391") (name "unconnected-(SW88-Pad5)") (class "Default")
      (node (ref "SW88") (pin "5") (pintype "passive"))
    )
    (net (code "392") (name "unconnected-(SW88-Pad6)") (class "Default")
      (node (ref "SW88") (pin "6") (pintype "passive"))
    )
    (net (code "393") (name "unconnected-(SW89-Pad5)") (class "Default")
      (node (ref "SW89") (pin "5") (pintype "passive"))
    )
    (net (code "394") (name "unconnected-(SW89-Pad6)") (class "Default")
      (node (ref "SW89") (pin "6") (pintype "passive"))
    )
    (net (code "395") (name "unconnected-(SW90-Pad5)") (class "Default")
      (node (ref "SW90") (pin "5") (pintype "passive"))
    )
    (net (code "396") (name "unconnected-(SW90-Pad6)") (class "Default")
      (node (ref "SW90") (pin "6") (pintype "passive"))
    )
    (net (code "397") (name "unconnected-(SW91-Pad5)") (class "Default")
      (node (ref "SW91") (pin "5") (pintype "passive"))
    )
    (net (code "398") (name "unconnected-(SW91-Pad6)") (class "Default")
      (node (ref "SW91") (pin "6") (pintype "passive"))
    )
    (net (code "399") (name "unconnected-(SW92-Pad5)") (class "Default")
      (node (ref "SW92") (pin "5") (pintype "passive"))
    )
    (net (code "400") (name "unconnected-(SW92-Pad6)") (class "Default")
      (node (ref "SW92") (pin "6") (pintype "passive"))
    )
    (net (code "401") (name "unconnected-(SW93-Pad5)") (class "Default")
      (node (ref "SW93") (pin "5") (pintype "passive"))
    )
    (net (code "402") (name "unconnected-(SW93-Pad6)") (class "Default")
      (node (ref "SW93") (pin "6") (pintype "passive"))
    )
    (net (code "403") (name "unconnected-(SW94-Pad5)") (class "Default")
      (node (ref "SW94") (pin "5") (pintype "passive"))
    )
    (net (code "404") (name "unconnected-(SW94-Pad6)") (class "Default")
      (node (ref "SW94") (pin "6") (pintype "passive"))
    )
    (net (code "405") (name "unconnected-(SW95-Pad5)") (class "Default")
      (node (ref "SW95") (pin "5") (pintype "passive"))
    )
    (net (code "406") (name "unconnected-(SW95-Pad6)") (class "Default")
      (node (ref "SW95") (pin "6") (pintype "passive"))
    )
    (net (code "407") (name "unconnected-(SW96-Pad5)") (class "Default")
      (node (ref "SW96") (pin "5") (pintype "passive"))
    )
    (net (code "408") (name "unconnected-(SW96-Pad6)") (class "Default")
      (node (ref "SW96") (pin "6") (pintype "passive"))
    )
  )
)
